# Glasses.net
KiCad netlist of a schematic drawn in EAGLE
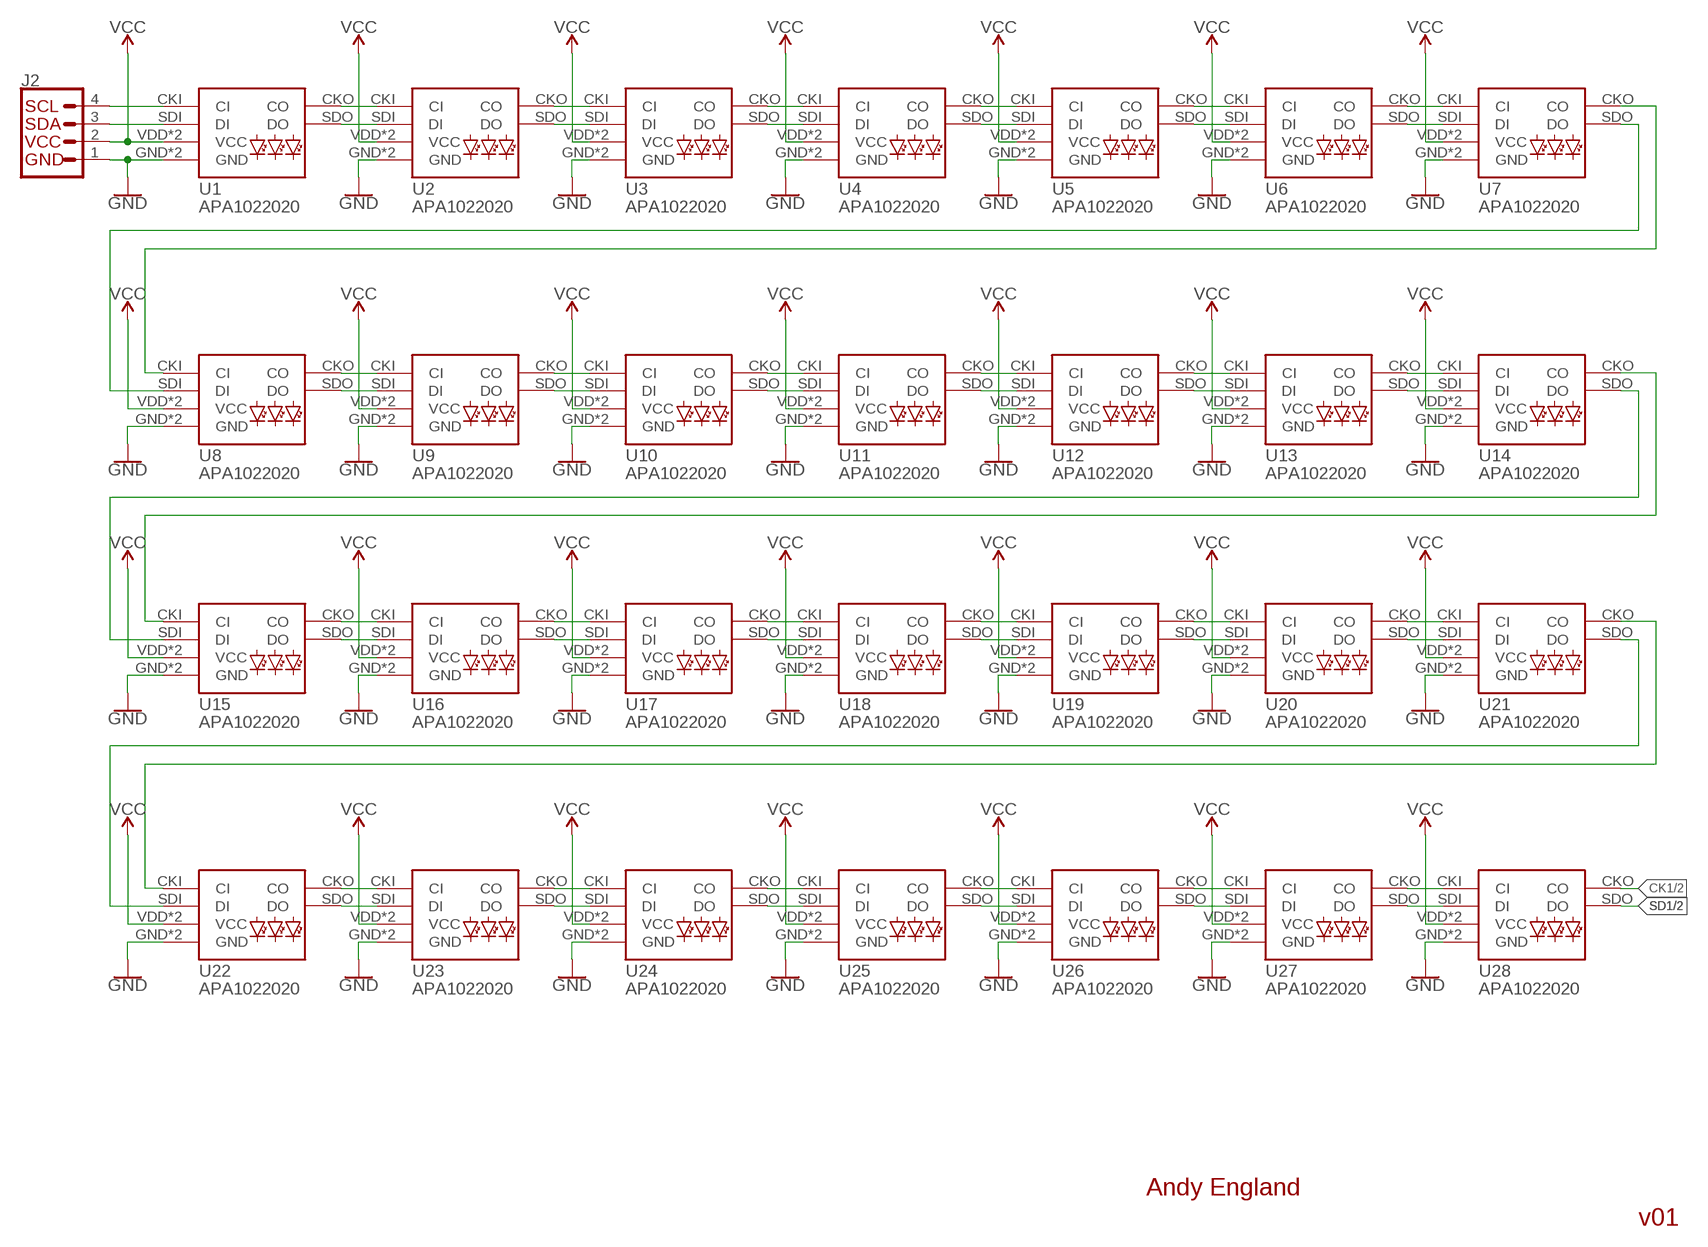
[diagram p0: schematic, sheet 1]
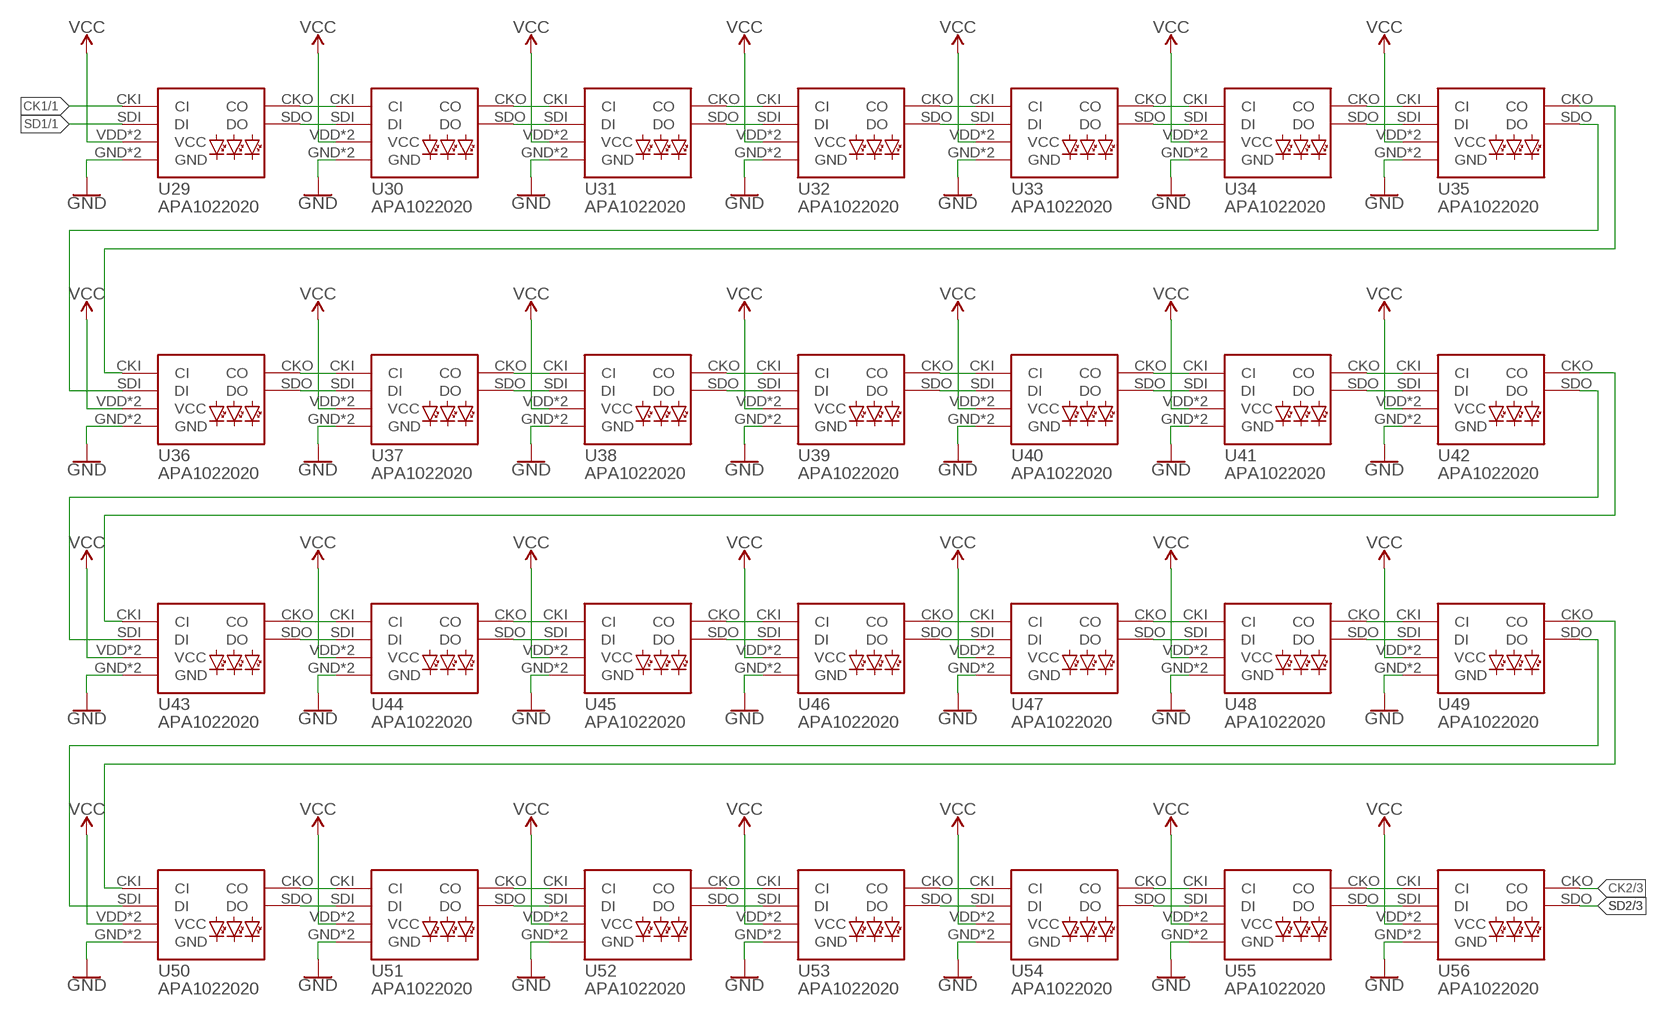
[diagram p1: schematic, sheet 2]
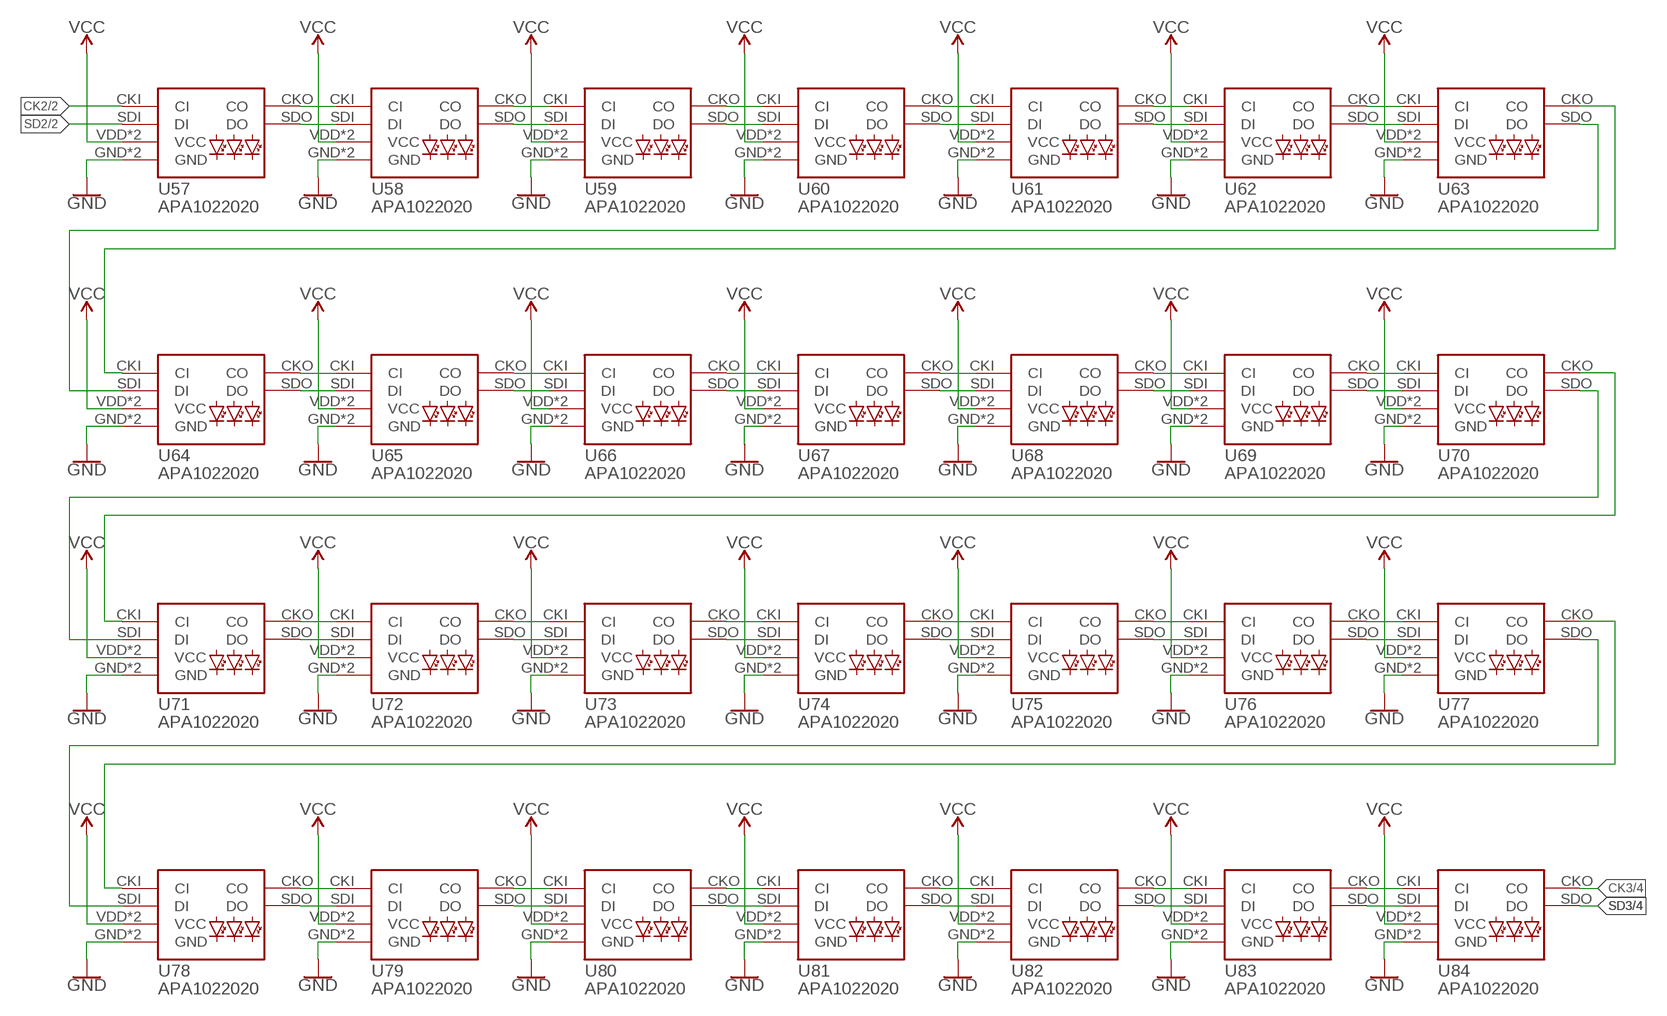
[diagram p2: schematic, sheet 3]
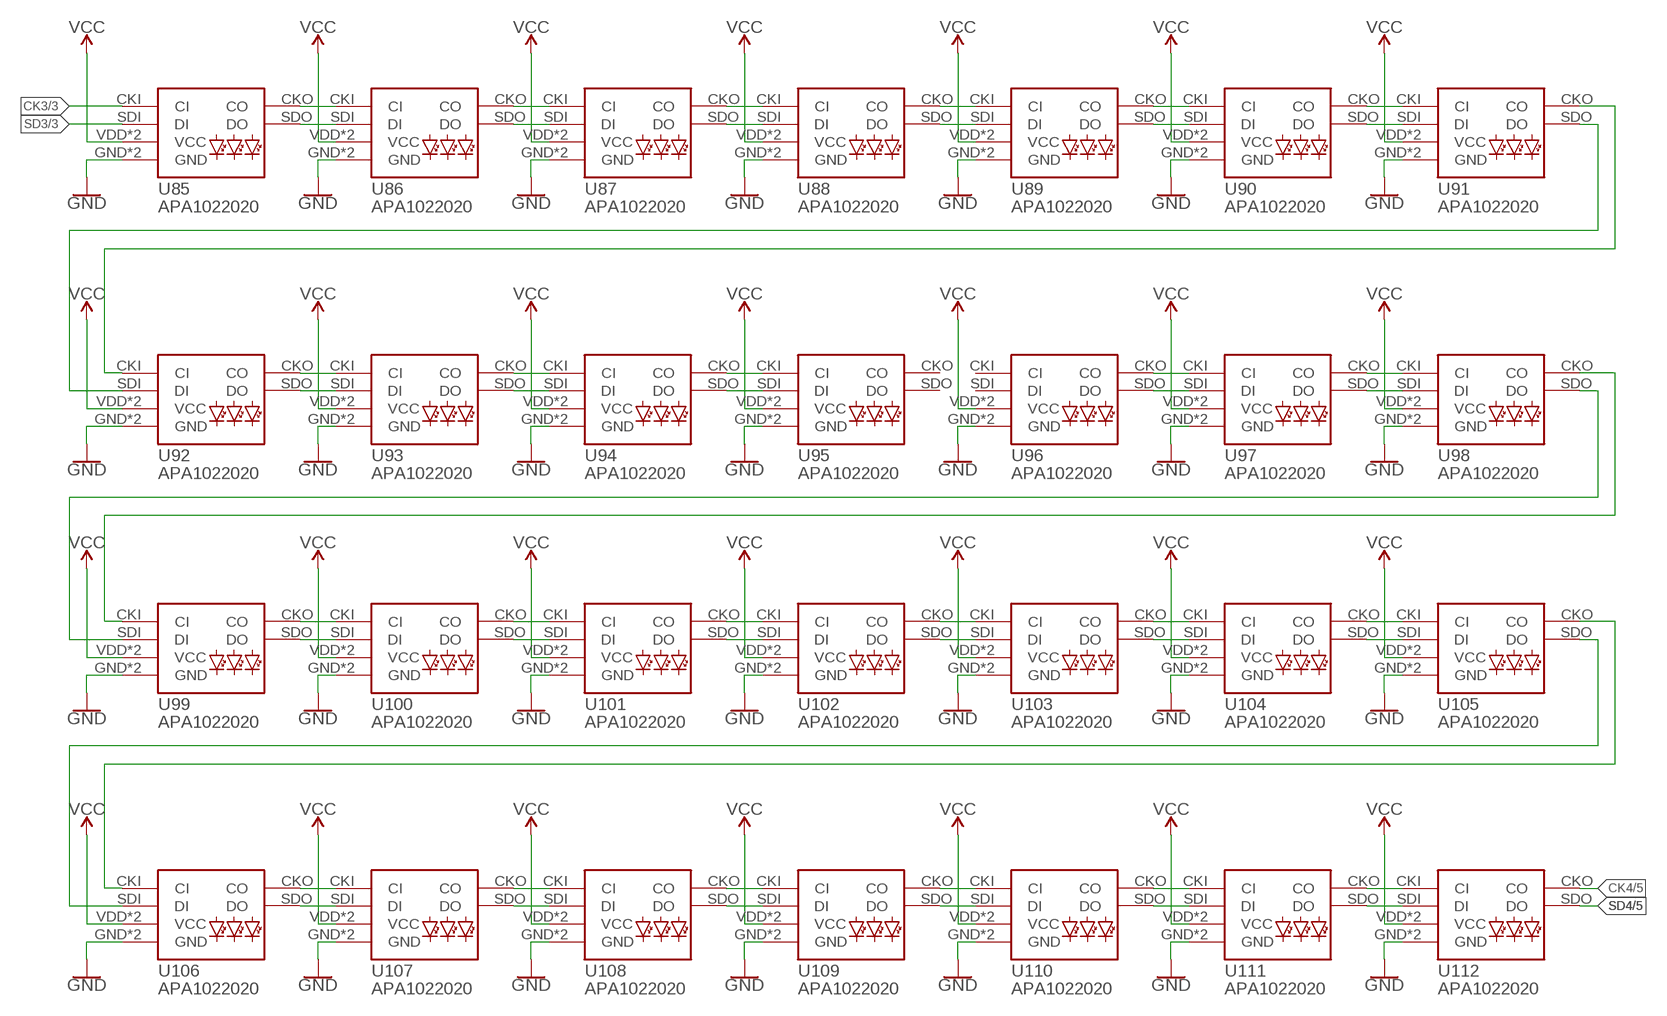
[diagram p3: schematic, sheet 4]
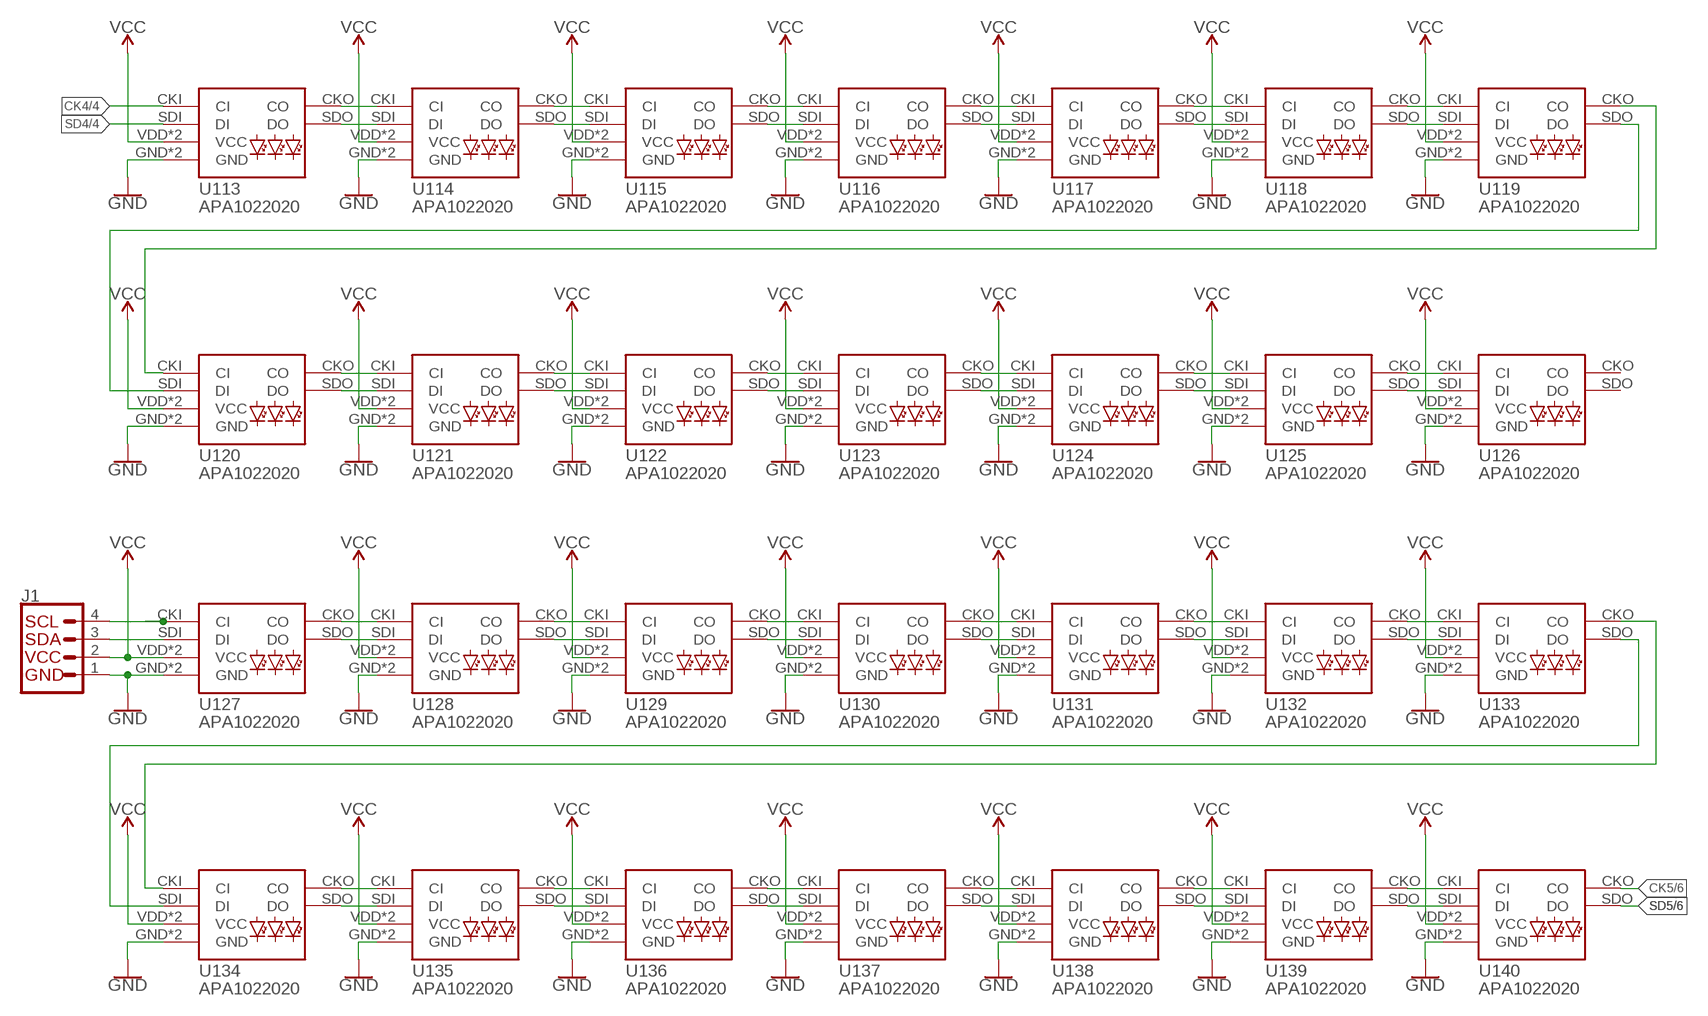
[diagram p4: schematic, sheet 5]
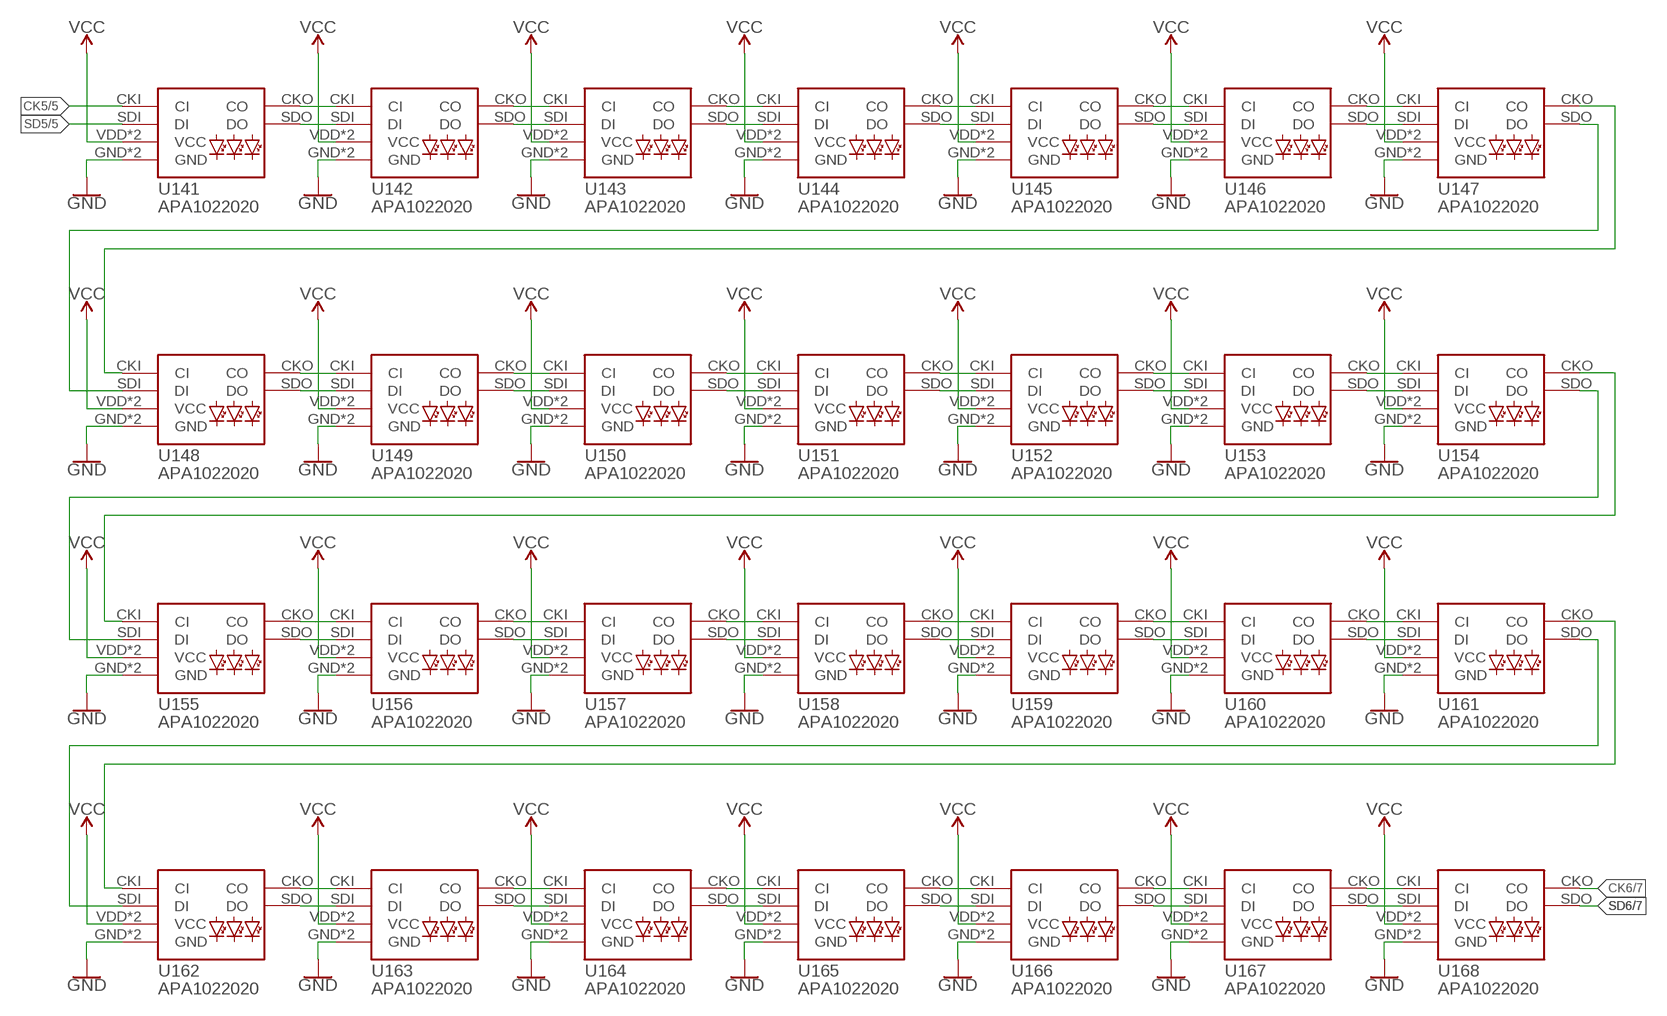
[diagram p5: schematic, sheet 6]
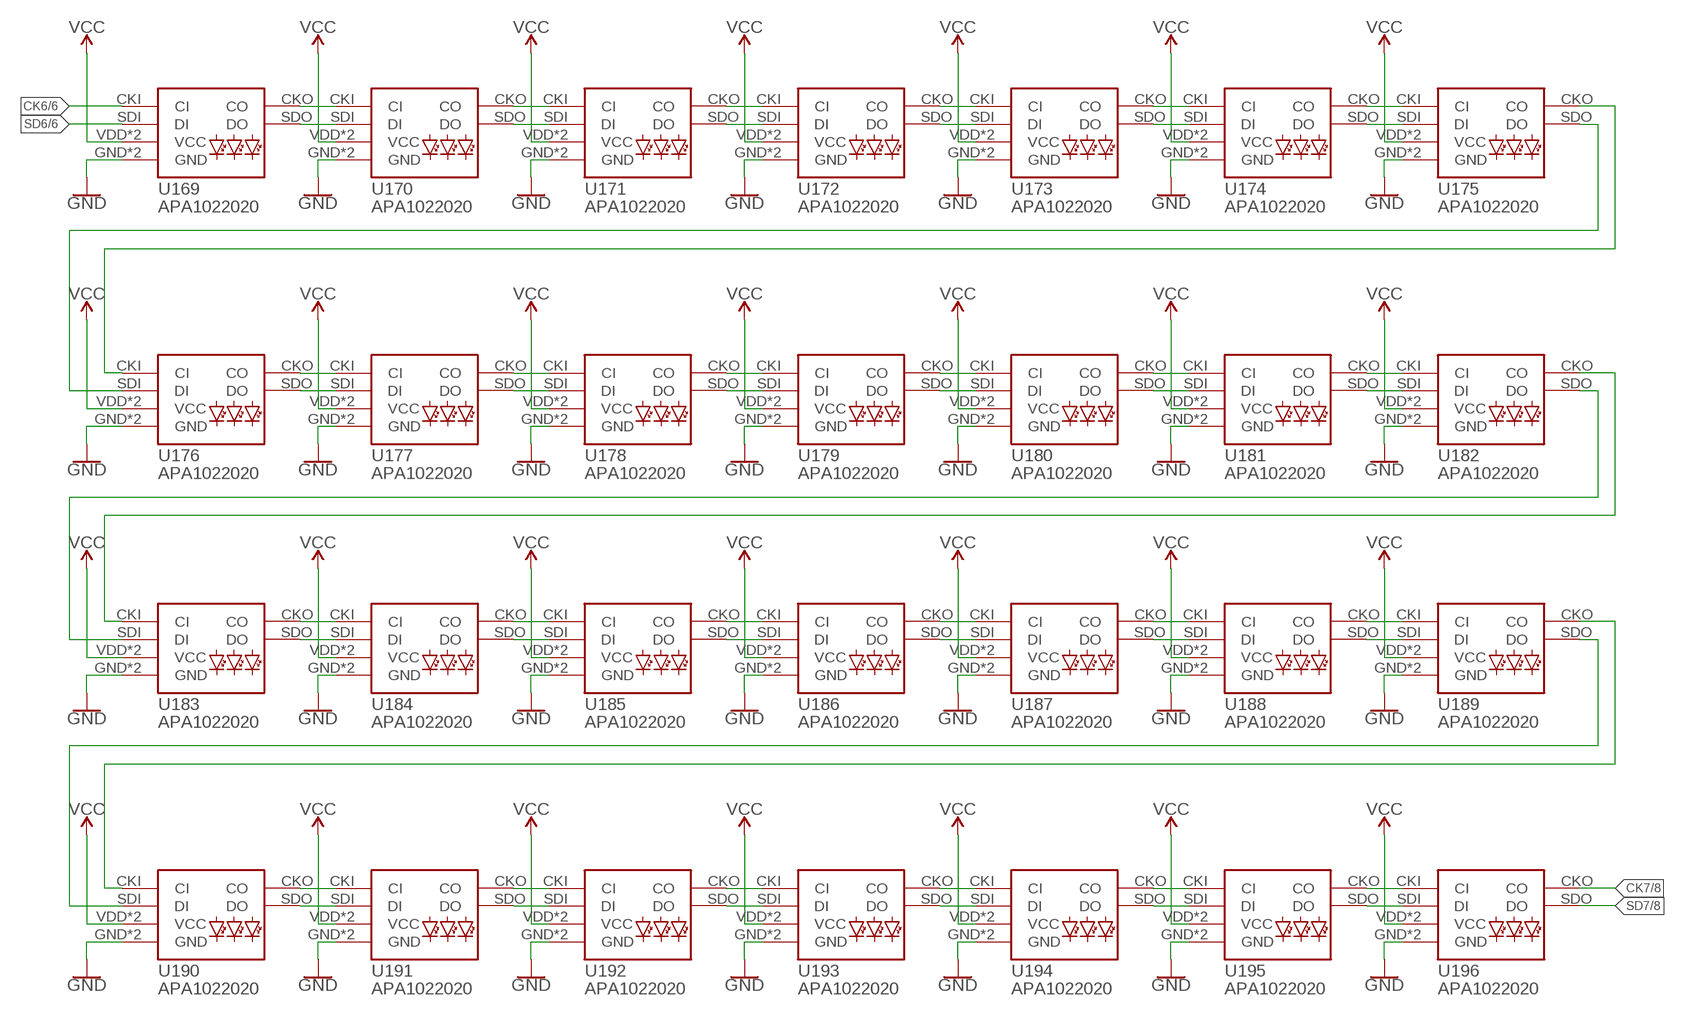
[diagram p6: schematic, sheet 7]
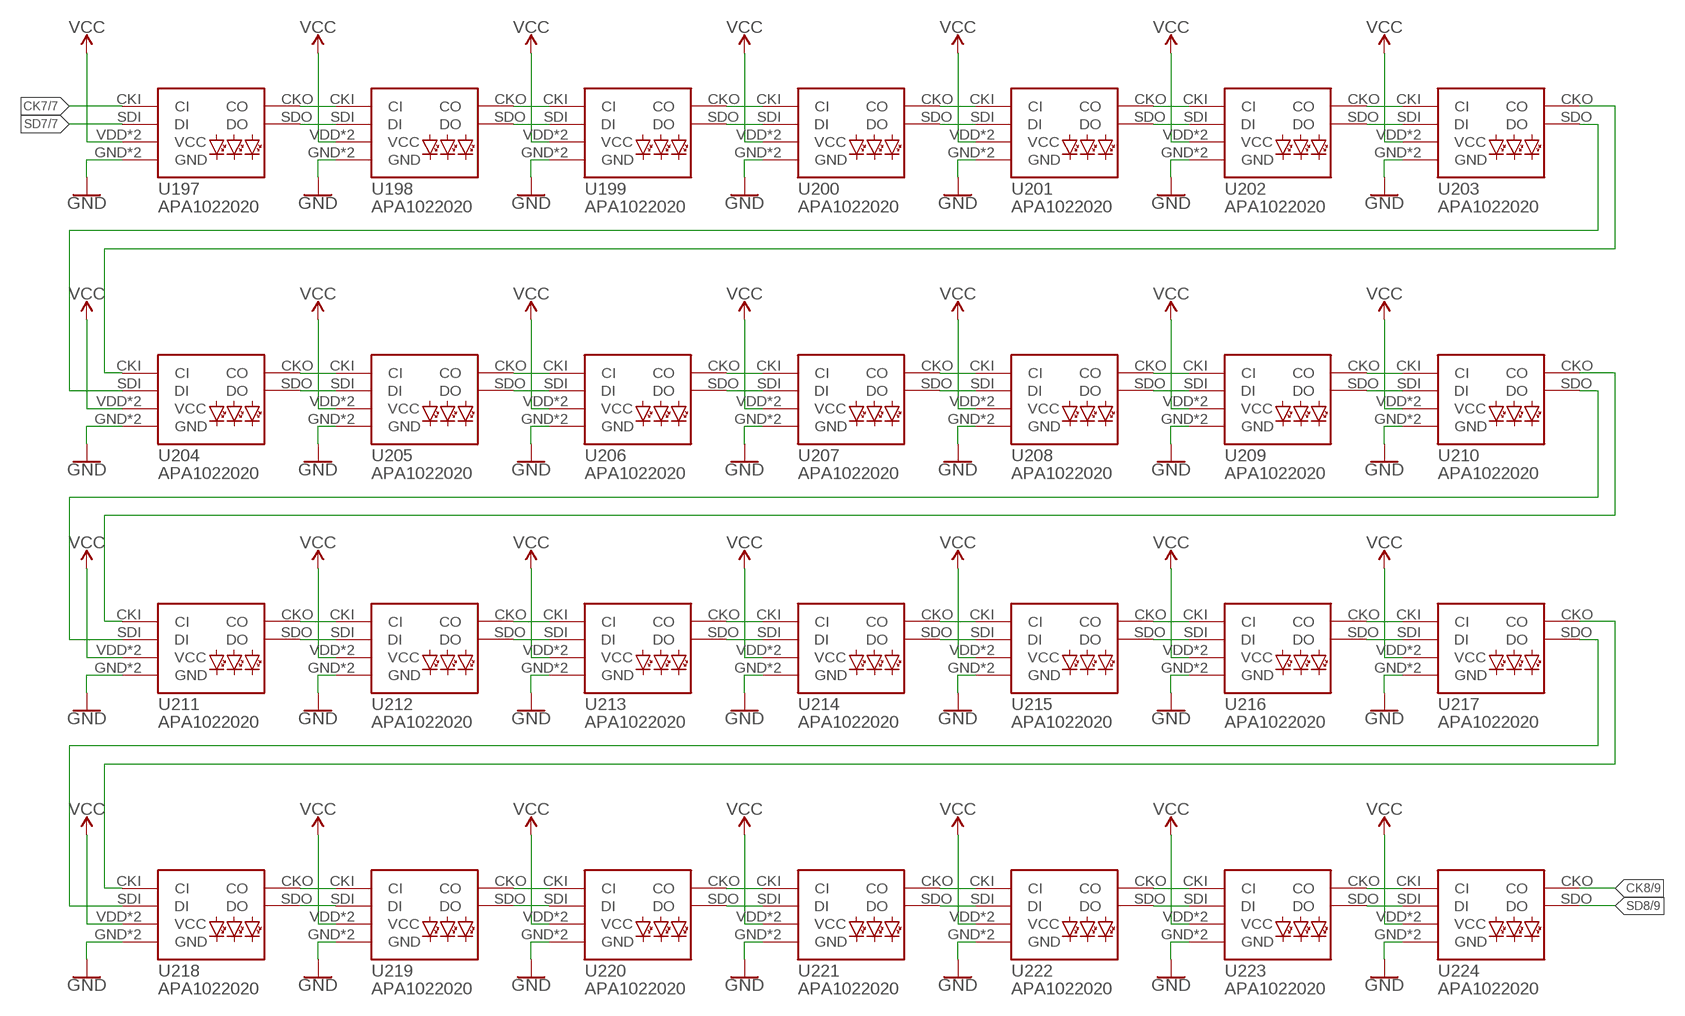
[diagram p7: schematic, sheet 8]
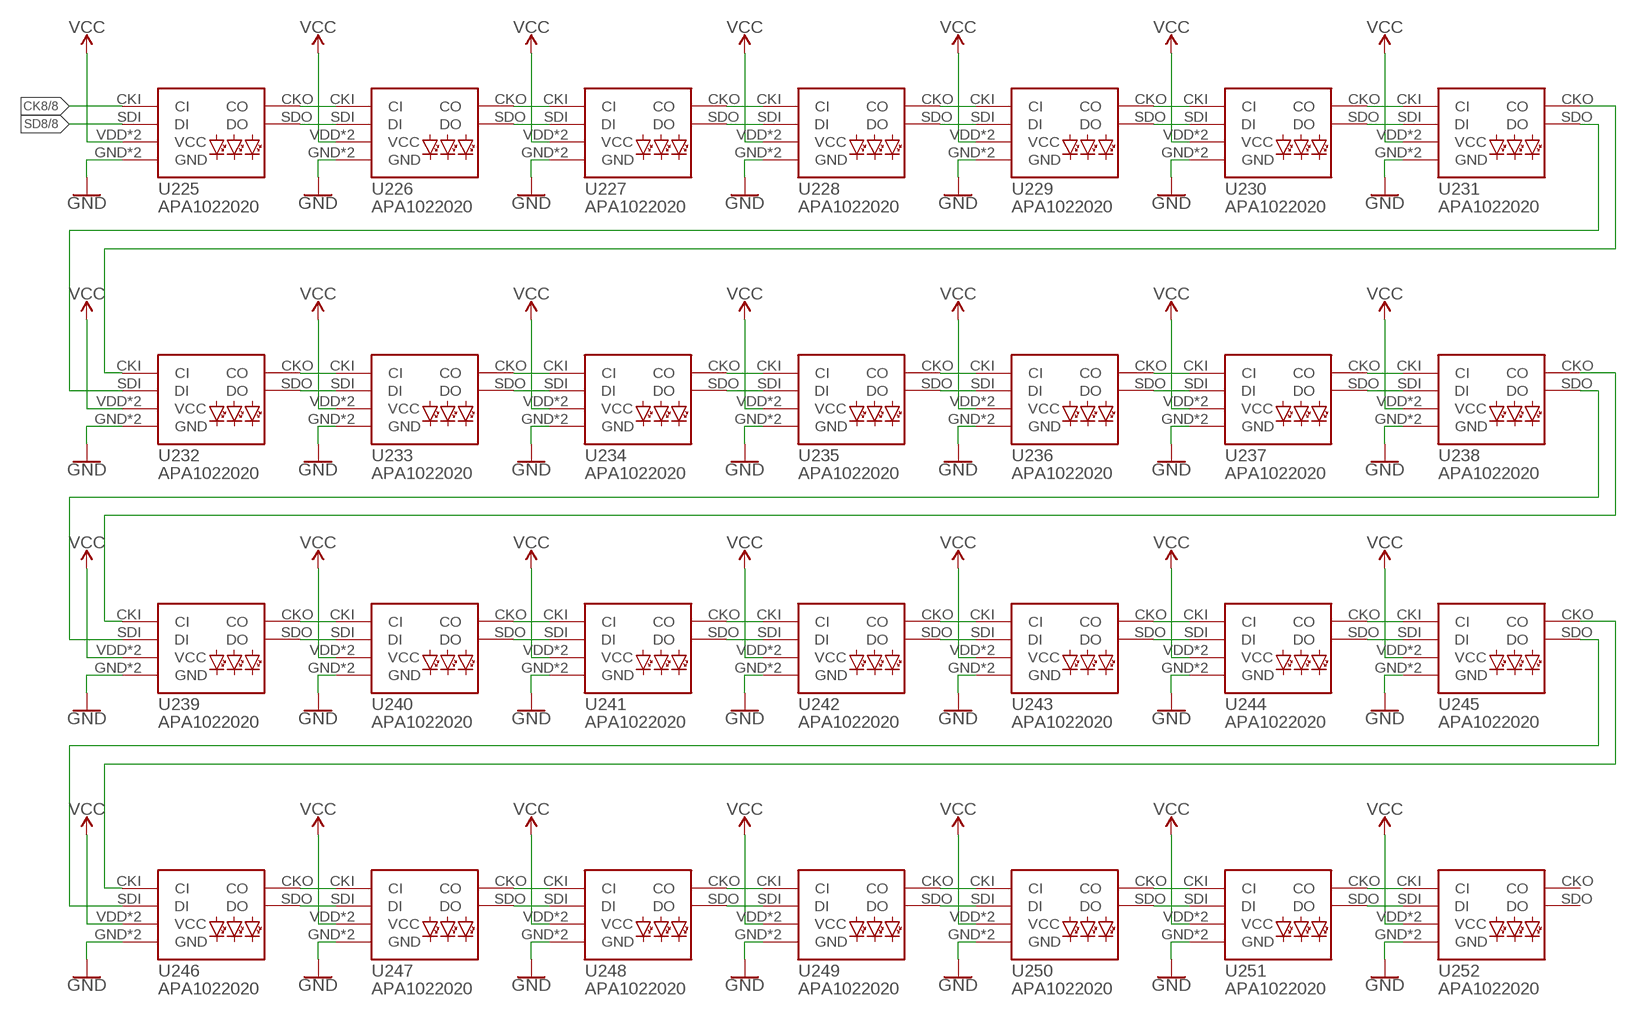
[diagram p8: schematic, sheet 9]

(export (version "E")
  (design (tool "Eeschema 10.0.6"))
  (components
    (comp (ref "U225")
      (value "APA1022020")
      (footprint "eagle-import:APA102-2020")
      (libsource (lib "eagle-import") (part "APA1022020"))
    )
    (comp (ref "U226")
      (value "APA1022020")
      (footprint "eagle-import:APA102-2020")
      (libsource (lib "eagle-import") (part "APA1022020"))
    )
    (comp (ref "U227")
      (value "APA1022020")
      (footprint "eagle-import:APA102-2020")
      (libsource (lib "eagle-import") (part "APA1022020"))
    )
    (comp (ref "U228")
      (value "APA1022020")
      (footprint "eagle-import:APA102-2020")
      (libsource (lib "eagle-import") (part "APA1022020"))
    )
    (comp (ref "U229")
      (value "APA1022020")
      (footprint "eagle-import:APA102-2020")
      (libsource (lib "eagle-import") (part "APA1022020"))
    )
    (comp (ref "U230")
      (value "APA1022020")
      (footprint "eagle-import:APA102-2020")
      (libsource (lib "eagle-import") (part "APA1022020"))
    )
    (comp (ref "U231")
      (value "APA1022020")
      (footprint "eagle-import:APA102-2020")
      (libsource (lib "eagle-import") (part "APA1022020"))
    )
    (comp (ref "U232")
      (value "APA1022020")
      (footprint "eagle-import:APA102-2020")
      (libsource (lib "eagle-import") (part "APA1022020"))
    )
    (comp (ref "U233")
      (value "APA1022020")
      (footprint "eagle-import:APA102-2020")
      (libsource (lib "eagle-import") (part "APA1022020"))
    )
    (comp (ref "U234")
      (value "APA1022020")
      (footprint "eagle-import:APA102-2020")
      (libsource (lib "eagle-import") (part "APA1022020"))
    )
    (comp (ref "U235")
      (value "APA1022020")
      (footprint "eagle-import:APA102-2020")
      (libsource (lib "eagle-import") (part "APA1022020"))
    )
    (comp (ref "U236")
      (value "APA1022020")
      (footprint "eagle-import:APA102-2020")
      (libsource (lib "eagle-import") (part "APA1022020"))
    )
    (comp (ref "U237")
      (value "APA1022020")
      (footprint "eagle-import:APA102-2020")
      (libsource (lib "eagle-import") (part "APA1022020"))
    )
    (comp (ref "U238")
      (value "APA1022020")
      (footprint "eagle-import:APA102-2020")
      (libsource (lib "eagle-import") (part "APA1022020"))
    )
    (comp (ref "U239")
      (value "APA1022020")
      (footprint "eagle-import:APA102-2020")
      (libsource (lib "eagle-import") (part "APA1022020"))
    )
    (comp (ref "U240")
      (value "APA1022020")
      (footprint "eagle-import:APA102-2020")
      (libsource (lib "eagle-import") (part "APA1022020"))
    )
    (comp (ref "U241")
      (value "APA1022020")
      (footprint "eagle-import:APA102-2020")
      (libsource (lib "eagle-import") (part "APA1022020"))
    )
    (comp (ref "U242")
      (value "APA1022020")
      (footprint "eagle-import:APA102-2020")
      (libsource (lib "eagle-import") (part "APA1022020"))
    )
    (comp (ref "U243")
      (value "APA1022020")
      (footprint "eagle-import:APA102-2020")
      (libsource (lib "eagle-import") (part "APA1022020"))
    )
    (comp (ref "U244")
      (value "APA1022020")
      (footprint "eagle-import:APA102-2020")
      (libsource (lib "eagle-import") (part "APA1022020"))
    )
    (comp (ref "U245")
      (value "APA1022020")
      (footprint "eagle-import:APA102-2020")
      (libsource (lib "eagle-import") (part "APA1022020"))
    )
    (comp (ref "U246")
      (value "APA1022020")
      (footprint "eagle-import:APA102-2020")
      (libsource (lib "eagle-import") (part "APA1022020"))
    )
    (comp (ref "U247")
      (value "APA1022020")
      (footprint "eagle-import:APA102-2020")
      (libsource (lib "eagle-import") (part "APA1022020"))
    )
    (comp (ref "U248")
      (value "APA1022020")
      (footprint "eagle-import:APA102-2020")
      (libsource (lib "eagle-import") (part "APA1022020"))
    )
    (comp (ref "U249")
      (value "APA1022020")
      (footprint "eagle-import:APA102-2020")
      (libsource (lib "eagle-import") (part "APA1022020"))
    )
    (comp (ref "U250")
      (value "APA1022020")
      (footprint "eagle-import:APA102-2020")
      (libsource (lib "eagle-import") (part "APA1022020"))
    )
    (comp (ref "U251")
      (value "APA1022020")
      (footprint "eagle-import:APA102-2020")
      (libsource (lib "eagle-import") (part "APA1022020"))
    )
    (comp (ref "U252")
      (value "APA1022020")
      (footprint "eagle-import:APA102-2020")
      (libsource (lib "eagle-import") (part "APA1022020"))
    )
    (comp (ref "U141")
      (value "APA1022020")
      (footprint "eagle-import:APA102-2020")
      (libsource (lib "eagle-import") (part "APA1022020"))
    )
    (comp (ref "U142")
      (value "APA1022020")
      (footprint "eagle-import:APA102-2020")
      (libsource (lib "eagle-import") (part "APA1022020"))
    )
    (comp (ref "U143")
      (value "APA1022020")
      (footprint "eagle-import:APA102-2020")
      (libsource (lib "eagle-import") (part "APA1022020"))
    )
    (comp (ref "U144")
      (value "APA1022020")
      (footprint "eagle-import:APA102-2020")
      (libsource (lib "eagle-import") (part "APA1022020"))
    )
    (comp (ref "U145")
      (value "APA1022020")
      (footprint "eagle-import:APA102-2020")
      (libsource (lib "eagle-import") (part "APA1022020"))
    )
    (comp (ref "U146")
      (value "APA1022020")
      (footprint "eagle-import:APA102-2020")
      (libsource (lib "eagle-import") (part "APA1022020"))
    )
    (comp (ref "U147")
      (value "APA1022020")
      (footprint "eagle-import:APA102-2020")
      (libsource (lib "eagle-import") (part "APA1022020"))
    )
    (comp (ref "U148")
      (value "APA1022020")
      (footprint "eagle-import:APA102-2020")
      (libsource (lib "eagle-import") (part "APA1022020"))
    )
    (comp (ref "U149")
      (value "APA1022020")
      (footprint "eagle-import:APA102-2020")
      (libsource (lib "eagle-import") (part "APA1022020"))
    )
    (comp (ref "U150")
      (value "APA1022020")
      (footprint "eagle-import:APA102-2020")
      (libsource (lib "eagle-import") (part "APA1022020"))
    )
    (comp (ref "U151")
      (value "APA1022020")
      (footprint "eagle-import:APA102-2020")
      (libsource (lib "eagle-import") (part "APA1022020"))
    )
    (comp (ref "U152")
      (value "APA1022020")
      (footprint "eagle-import:APA102-2020")
      (libsource (lib "eagle-import") (part "APA1022020"))
    )
    (comp (ref "U153")
      (value "APA1022020")
      (footprint "eagle-import:APA102-2020")
      (libsource (lib "eagle-import") (part "APA1022020"))
    )
    (comp (ref "U154")
      (value "APA1022020")
      (footprint "eagle-import:APA102-2020")
      (libsource (lib "eagle-import") (part "APA1022020"))
    )
    (comp (ref "U155")
      (value "APA1022020")
      (footprint "eagle-import:APA102-2020")
      (libsource (lib "eagle-import") (part "APA1022020"))
    )
    (comp (ref "U156")
      (value "APA1022020")
      (footprint "eagle-import:APA102-2020")
      (libsource (lib "eagle-import") (part "APA1022020"))
    )
    (comp (ref "U157")
      (value "APA1022020")
      (footprint "eagle-import:APA102-2020")
      (libsource (lib "eagle-import") (part "APA1022020"))
    )
    (comp (ref "U158")
      (value "APA1022020")
      (footprint "eagle-import:APA102-2020")
      (libsource (lib "eagle-import") (part "APA1022020"))
    )
    (comp (ref "U159")
      (value "APA1022020")
      (footprint "eagle-import:APA102-2020")
      (libsource (lib "eagle-import") (part "APA1022020"))
    )
    (comp (ref "U160")
      (value "APA1022020")
      (footprint "eagle-import:APA102-2020")
      (libsource (lib "eagle-import") (part "APA1022020"))
    )
    (comp (ref "U161")
      (value "APA1022020")
      (footprint "eagle-import:APA102-2020")
      (libsource (lib "eagle-import") (part "APA1022020"))
    )
    (comp (ref "U162")
      (value "APA1022020")
      (footprint "eagle-import:APA102-2020")
      (libsource (lib "eagle-import") (part "APA1022020"))
    )
    (comp (ref "U163")
      (value "APA1022020")
      (footprint "eagle-import:APA102-2020")
      (libsource (lib "eagle-import") (part "APA1022020"))
    )
    (comp (ref "U164")
      (value "APA1022020")
      (footprint "eagle-import:APA102-2020")
      (libsource (lib "eagle-import") (part "APA1022020"))
    )
    (comp (ref "U165")
      (value "APA1022020")
      (footprint "eagle-import:APA102-2020")
      (libsource (lib "eagle-import") (part "APA1022020"))
    )
    (comp (ref "U166")
      (value "APA1022020")
      (footprint "eagle-import:APA102-2020")
      (libsource (lib "eagle-import") (part "APA1022020"))
    )
    (comp (ref "U167")
      (value "APA1022020")
      (footprint "eagle-import:APA102-2020")
      (libsource (lib "eagle-import") (part "APA1022020"))
    )
    (comp (ref "U168")
      (value "APA1022020")
      (footprint "eagle-import:APA102-2020")
      (libsource (lib "eagle-import") (part "APA1022020"))
    )
    (comp (ref "U169")
      (value "APA1022020")
      (footprint "eagle-import:APA102-2020")
      (libsource (lib "eagle-import") (part "APA1022020"))
    )
    (comp (ref "U170")
      (value "APA1022020")
      (footprint "eagle-import:APA102-2020")
      (libsource (lib "eagle-import") (part "APA1022020"))
    )
    (comp (ref "U171")
      (value "APA1022020")
      (footprint "eagle-import:APA102-2020")
      (libsource (lib "eagle-import") (part "APA1022020"))
    )
    (comp (ref "U172")
      (value "APA1022020")
      (footprint "eagle-import:APA102-2020")
      (libsource (lib "eagle-import") (part "APA1022020"))
    )
    (comp (ref "U173")
      (value "APA1022020")
      (footprint "eagle-import:APA102-2020")
      (libsource (lib "eagle-import") (part "APA1022020"))
    )
    (comp (ref "U174")
      (value "APA1022020")
      (footprint "eagle-import:APA102-2020")
      (libsource (lib "eagle-import") (part "APA1022020"))
    )
    (comp (ref "U175")
      (value "APA1022020")
      (footprint "eagle-import:APA102-2020")
      (libsource (lib "eagle-import") (part "APA1022020"))
    )
    (comp (ref "U176")
      (value "APA1022020")
      (footprint "eagle-import:APA102-2020")
      (libsource (lib "eagle-import") (part "APA1022020"))
    )
    (comp (ref "U177")
      (value "APA1022020")
      (footprint "eagle-import:APA102-2020")
      (libsource (lib "eagle-import") (part "APA1022020"))
    )
    (comp (ref "U178")
      (value "APA1022020")
      (footprint "eagle-import:APA102-2020")
      (libsource (lib "eagle-import") (part "APA1022020"))
    )
    (comp (ref "U179")
      (value "APA1022020")
      (footprint "eagle-import:APA102-2020")
      (libsource (lib "eagle-import") (part "APA1022020"))
    )
    (comp (ref "U180")
      (value "APA1022020")
      (footprint "eagle-import:APA102-2020")
      (libsource (lib "eagle-import") (part "APA1022020"))
    )
    (comp (ref "U181")
      (value "APA1022020")
      (footprint "eagle-import:APA102-2020")
      (libsource (lib "eagle-import") (part "APA1022020"))
    )
    (comp (ref "U182")
      (value "APA1022020")
      (footprint "eagle-import:APA102-2020")
      (libsource (lib "eagle-import") (part "APA1022020"))
    )
    (comp (ref "U183")
      (value "APA1022020")
      (footprint "eagle-import:APA102-2020")
      (libsource (lib "eagle-import") (part "APA1022020"))
    )
    (comp (ref "U184")
      (value "APA1022020")
      (footprint "eagle-import:APA102-2020")
      (libsource (lib "eagle-import") (part "APA1022020"))
    )
    (comp (ref "U185")
      (value "APA1022020")
      (footprint "eagle-import:APA102-2020")
      (libsource (lib "eagle-import") (part "APA1022020"))
    )
    (comp (ref "U186")
      (value "APA1022020")
      (footprint "eagle-import:APA102-2020")
      (libsource (lib "eagle-import") (part "APA1022020"))
    )
    (comp (ref "U187")
      (value "APA1022020")
      (footprint "eagle-import:APA102-2020")
      (libsource (lib "eagle-import") (part "APA1022020"))
    )
    (comp (ref "U188")
      (value "APA1022020")
      (footprint "eagle-import:APA102-2020")
      (libsource (lib "eagle-import") (part "APA1022020"))
    )
    (comp (ref "U189")
      (value "APA1022020")
      (footprint "eagle-import:APA102-2020")
      (libsource (lib "eagle-import") (part "APA1022020"))
    )
    (comp (ref "U190")
      (value "APA1022020")
      (footprint "eagle-import:APA102-2020")
      (libsource (lib "eagle-import") (part "APA1022020"))
    )
    (comp (ref "U191")
      (value "APA1022020")
      (footprint "eagle-import:APA102-2020")
      (libsource (lib "eagle-import") (part "APA1022020"))
    )
    (comp (ref "U192")
      (value "APA1022020")
      (footprint "eagle-import:APA102-2020")
      (libsource (lib "eagle-import") (part "APA1022020"))
    )
    (comp (ref "U193")
      (value "APA1022020")
      (footprint "eagle-import:APA102-2020")
      (libsource (lib "eagle-import") (part "APA1022020"))
    )
    (comp (ref "U194")
      (value "APA1022020")
      (footprint "eagle-import:APA102-2020")
      (libsource (lib "eagle-import") (part "APA1022020"))
    )
    (comp (ref "U195")
      (value "APA1022020")
      (footprint "eagle-import:APA102-2020")
      (libsource (lib "eagle-import") (part "APA1022020"))
    )
    (comp (ref "U196")
      (value "APA1022020")
      (footprint "eagle-import:APA102-2020")
      (libsource (lib "eagle-import") (part "APA1022020"))
    )
    (comp (ref "U197")
      (value "APA1022020")
      (footprint "eagle-import:APA102-2020")
      (libsource (lib "eagle-import") (part "APA1022020"))
    )
    (comp (ref "U198")
      (value "APA1022020")
      (footprint "eagle-import:APA102-2020")
      (libsource (lib "eagle-import") (part "APA1022020"))
    )
    (comp (ref "U199")
      (value "APA1022020")
      (footprint "eagle-import:APA102-2020")
      (libsource (lib "eagle-import") (part "APA1022020"))
    )
    (comp (ref "U200")
      (value "APA1022020")
      (footprint "eagle-import:APA102-2020")
      (libsource (lib "eagle-import") (part "APA1022020"))
    )
    (comp (ref "U201")
      (value "APA1022020")
      (footprint "eagle-import:APA102-2020")
      (libsource (lib "eagle-import") (part "APA1022020"))
    )
    (comp (ref "U202")
      (value "APA1022020")
      (footprint "eagle-import:APA102-2020")
      (libsource (lib "eagle-import") (part "APA1022020"))
    )
    (comp (ref "U203")
      (value "APA1022020")
      (footprint "eagle-import:APA102-2020")
      (libsource (lib "eagle-import") (part "APA1022020"))
    )
    (comp (ref "U204")
      (value "APA1022020")
      (footprint "eagle-import:APA102-2020")
      (libsource (lib "eagle-import") (part "APA1022020"))
    )
    (comp (ref "U205")
      (value "APA1022020")
      (footprint "eagle-import:APA102-2020")
      (libsource (lib "eagle-import") (part "APA1022020"))
    )
    (comp (ref "U206")
      (value "APA1022020")
      (footprint "eagle-import:APA102-2020")
      (libsource (lib "eagle-import") (part "APA1022020"))
    )
    (comp (ref "U207")
      (value "APA1022020")
      (footprint "eagle-import:APA102-2020")
      (libsource (lib "eagle-import") (part "APA1022020"))
    )
    (comp (ref "U208")
      (value "APA1022020")
      (footprint "eagle-import:APA102-2020")
      (libsource (lib "eagle-import") (part "APA1022020"))
    )
    (comp (ref "U209")
      (value "APA1022020")
      (footprint "eagle-import:APA102-2020")
      (libsource (lib "eagle-import") (part "APA1022020"))
    )
    (comp (ref "U210")
      (value "APA1022020")
      (footprint "eagle-import:APA102-2020")
      (libsource (lib "eagle-import") (part "APA1022020"))
    )
    (comp (ref "U211")
      (value "APA1022020")
      (footprint "eagle-import:APA102-2020")
      (libsource (lib "eagle-import") (part "APA1022020"))
    )
    (comp (ref "U212")
      (value "APA1022020")
      (footprint "eagle-import:APA102-2020")
      (libsource (lib "eagle-import") (part "APA1022020"))
    )
    (comp (ref "U213")
      (value "APA1022020")
      (footprint "eagle-import:APA102-2020")
      (libsource (lib "eagle-import") (part "APA1022020"))
    )
    (comp (ref "U214")
      (value "APA1022020")
      (footprint "eagle-import:APA102-2020")
      (libsource (lib "eagle-import") (part "APA1022020"))
    )
    (comp (ref "U215")
      (value "APA1022020")
      (footprint "eagle-import:APA102-2020")
      (libsource (lib "eagle-import") (part "APA1022020"))
    )
    (comp (ref "U216")
      (value "APA1022020")
      (footprint "eagle-import:APA102-2020")
      (libsource (lib "eagle-import") (part "APA1022020"))
    )
    (comp (ref "U217")
      (value "APA1022020")
      (footprint "eagle-import:APA102-2020")
      (libsource (lib "eagle-import") (part "APA1022020"))
    )
    (comp (ref "U218")
      (value "APA1022020")
      (footprint "eagle-import:APA102-2020")
      (libsource (lib "eagle-import") (part "APA1022020"))
    )
    (comp (ref "U219")
      (value "APA1022020")
      (footprint "eagle-import:APA102-2020")
      (libsource (lib "eagle-import") (part "APA1022020"))
    )
    (comp (ref "U220")
      (value "APA1022020")
      (footprint "eagle-import:APA102-2020")
      (libsource (lib "eagle-import") (part "APA1022020"))
    )
    (comp (ref "U221")
      (value "APA1022020")
      (footprint "eagle-import:APA102-2020")
      (libsource (lib "eagle-import") (part "APA1022020"))
    )
    (comp (ref "U222")
      (value "APA1022020")
      (footprint "eagle-import:APA102-2020")
      (libsource (lib "eagle-import") (part "APA1022020"))
    )
    (comp (ref "U223")
      (value "APA1022020")
      (footprint "eagle-import:APA102-2020")
      (libsource (lib "eagle-import") (part "APA1022020"))
    )
    (comp (ref "U224")
      (value "APA1022020")
      (footprint "eagle-import:APA102-2020")
      (libsource (lib "eagle-import") (part "APA1022020"))
    )
    (comp (ref "J2")
      (value "QWIIC_CONNECTORJS-1MM")
      (footprint "eagle-import:1X04_1MM_RA")
      (libsource (lib "eagle-import") (part "QWIIC_CONNECTORJS-1MM"))
    )
    (comp (ref "U1")
      (value "APA1022020")
      (footprint "eagle-import:APA102-2020")
      (libsource (lib "eagle-import") (part "APA1022020"))
    )
    (comp (ref "U2")
      (value "APA1022020")
      (footprint "eagle-import:APA102-2020")
      (libsource (lib "eagle-import") (part "APA1022020"))
    )
    (comp (ref "U3")
      (value "APA1022020")
      (footprint "eagle-import:APA102-2020")
      (libsource (lib "eagle-import") (part "APA1022020"))
    )
    (comp (ref "U4")
      (value "APA1022020")
      (footprint "eagle-import:APA102-2020")
      (libsource (lib "eagle-import") (part "APA1022020"))
    )
    (comp (ref "U5")
      (value "APA1022020")
      (footprint "eagle-import:APA102-2020")
      (libsource (lib "eagle-import") (part "APA1022020"))
    )
    (comp (ref "U6")
      (value "APA1022020")
      (footprint "eagle-import:APA102-2020")
      (libsource (lib "eagle-import") (part "APA1022020"))
    )
    (comp (ref "U7")
      (value "APA1022020")
      (footprint "eagle-import:APA102-2020")
      (libsource (lib "eagle-import") (part "APA1022020"))
    )
    (comp (ref "U8")
      (value "APA1022020")
      (footprint "eagle-import:APA102-2020")
      (libsource (lib "eagle-import") (part "APA1022020"))
    )
    (comp (ref "U9")
      (value "APA1022020")
      (footprint "eagle-import:APA102-2020")
      (libsource (lib "eagle-import") (part "APA1022020"))
    )
    (comp (ref "U10")
      (value "APA1022020")
      (footprint "eagle-import:APA102-2020")
      (libsource (lib "eagle-import") (part "APA1022020"))
    )
    (comp (ref "U11")
      (value "APA1022020")
      (footprint "eagle-import:APA102-2020")
      (libsource (lib "eagle-import") (part "APA1022020"))
    )
    (comp (ref "U12")
      (value "APA1022020")
      (footprint "eagle-import:APA102-2020")
      (libsource (lib "eagle-import") (part "APA1022020"))
    )
    (comp (ref "U13")
      (value "APA1022020")
      (footprint "eagle-import:APA102-2020")
      (libsource (lib "eagle-import") (part "APA1022020"))
    )
    (comp (ref "U14")
      (value "APA1022020")
      (footprint "eagle-import:APA102-2020")
      (libsource (lib "eagle-import") (part "APA1022020"))
    )
    (comp (ref "U15")
      (value "APA1022020")
      (footprint "eagle-import:APA102-2020")
      (libsource (lib "eagle-import") (part "APA1022020"))
    )
    (comp (ref "U16")
      (value "APA1022020")
      (footprint "eagle-import:APA102-2020")
      (libsource (lib "eagle-import") (part "APA1022020"))
    )
    (comp (ref "U17")
      (value "APA1022020")
      (footprint "eagle-import:APA102-2020")
      (libsource (lib "eagle-import") (part "APA1022020"))
    )
    (comp (ref "U18")
      (value "APA1022020")
      (footprint "eagle-import:APA102-2020")
      (libsource (lib "eagle-import") (part "APA1022020"))
    )
    (comp (ref "U19")
      (value "APA1022020")
      (footprint "eagle-import:APA102-2020")
      (libsource (lib "eagle-import") (part "APA1022020"))
    )
    (comp (ref "U20")
      (value "APA1022020")
      (footprint "eagle-import:APA102-2020")
      (libsource (lib "eagle-import") (part "APA1022020"))
    )
    (comp (ref "U21")
      (value "APA1022020")
      (footprint "eagle-import:APA102-2020")
      (libsource (lib "eagle-import") (part "APA1022020"))
    )
    (comp (ref "U22")
      (value "APA1022020")
      (footprint "eagle-import:APA102-2020")
      (libsource (lib "eagle-import") (part "APA1022020"))
    )
    (comp (ref "U23")
      (value "APA1022020")
      (footprint "eagle-import:APA102-2020")
      (libsource (lib "eagle-import") (part "APA1022020"))
    )
    (comp (ref "U24")
      (value "APA1022020")
      (footprint "eagle-import:APA102-2020")
      (libsource (lib "eagle-import") (part "APA1022020"))
    )
    (comp (ref "U25")
      (value "APA1022020")
      (footprint "eagle-import:APA102-2020")
      (libsource (lib "eagle-import") (part "APA1022020"))
    )
    (comp (ref "U26")
      (value "APA1022020")
      (footprint "eagle-import:APA102-2020")
      (libsource (lib "eagle-import") (part "APA1022020"))
    )
    (comp (ref "U27")
      (value "APA1022020")
      (footprint "eagle-import:APA102-2020")
      (libsource (lib "eagle-import") (part "APA1022020"))
    )
    (comp (ref "U28")
      (value "APA1022020")
      (footprint "eagle-import:APA102-2020")
      (libsource (lib "eagle-import") (part "APA1022020"))
    )
    (comp (ref "J1")
      (value "QWIIC_CONNECTORJS-1MM")
      (footprint "eagle-import:1X04_1MM_RA")
      (libsource (lib "eagle-import") (part "QWIIC_CONNECTORJS-1MM"))
    )
    (comp (ref "U113")
      (value "APA1022020")
      (footprint "eagle-import:APA102-2020")
      (libsource (lib "eagle-import") (part "APA1022020"))
    )
    (comp (ref "U114")
      (value "APA1022020")
      (footprint "eagle-import:APA102-2020")
      (libsource (lib "eagle-import") (part "APA1022020"))
    )
    (comp (ref "U115")
      (value "APA1022020")
      (footprint "eagle-import:APA102-2020")
      (libsource (lib "eagle-import") (part "APA1022020"))
    )
    (comp (ref "U116")
      (value "APA1022020")
      (footprint "eagle-import:APA102-2020")
      (libsource (lib "eagle-import") (part "APA1022020"))
    )
    (comp (ref "U117")
      (value "APA1022020")
      (footprint "eagle-import:APA102-2020")
      (libsource (lib "eagle-import") (part "APA1022020"))
    )
    (comp (ref "U118")
      (value "APA1022020")
      (footprint "eagle-import:APA102-2020")
      (libsource (lib "eagle-import") (part "APA1022020"))
    )
    (comp (ref "U119")
      (value "APA1022020")
      (footprint "eagle-import:APA102-2020")
      (libsource (lib "eagle-import") (part "APA1022020"))
    )
    (comp (ref "U120")
      (value "APA1022020")
      (footprint "eagle-import:APA102-2020")
      (libsource (lib "eagle-import") (part "APA1022020"))
    )
    (comp (ref "U121")
      (value "APA1022020")
      (footprint "eagle-import:APA102-2020")
      (libsource (lib "eagle-import") (part "APA1022020"))
    )
    (comp (ref "U122")
      (value "APA1022020")
      (footprint "eagle-import:APA102-2020")
      (libsource (lib "eagle-import") (part "APA1022020"))
    )
    (comp (ref "U123")
      (value "APA1022020")
      (footprint "eagle-import:APA102-2020")
      (libsource (lib "eagle-import") (part "APA1022020"))
    )
    (comp (ref "U124")
      (value "APA1022020")
      (footprint "eagle-import:APA102-2020")
      (libsource (lib "eagle-import") (part "APA1022020"))
    )
    (comp (ref "U125")
      (value "APA1022020")
      (footprint "eagle-import:APA102-2020")
      (libsource (lib "eagle-import") (part "APA1022020"))
    )
    (comp (ref "U126")
      (value "APA1022020")
      (footprint "eagle-import:APA102-2020")
      (libsource (lib "eagle-import") (part "APA1022020"))
    )
    (comp (ref "U127")
      (value "APA1022020")
      (footprint "eagle-import:APA102-2020")
      (libsource (lib "eagle-import") (part "APA1022020"))
    )
    (comp (ref "U128")
      (value "APA1022020")
      (footprint "eagle-import:APA102-2020")
      (libsource (lib "eagle-import") (part "APA1022020"))
    )
    (comp (ref "U129")
      (value "APA1022020")
      (footprint "eagle-import:APA102-2020")
      (libsource (lib "eagle-import") (part "APA1022020"))
    )
    (comp (ref "U130")
      (value "APA1022020")
      (footprint "eagle-import:APA102-2020")
      (libsource (lib "eagle-import") (part "APA1022020"))
    )
    (comp (ref "U131")
      (value "APA1022020")
      (footprint "eagle-import:APA102-2020")
      (libsource (lib "eagle-import") (part "APA1022020"))
    )
    (comp (ref "U132")
      (value "APA1022020")
      (footprint "eagle-import:APA102-2020")
      (libsource (lib "eagle-import") (part "APA1022020"))
    )
    (comp (ref "U133")
      (value "APA1022020")
      (footprint "eagle-import:APA102-2020")
      (libsource (lib "eagle-import") (part "APA1022020"))
    )
    (comp (ref "U134")
      (value "APA1022020")
      (footprint "eagle-import:APA102-2020")
      (libsource (lib "eagle-import") (part "APA1022020"))
    )
    (comp (ref "U135")
      (value "APA1022020")
      (footprint "eagle-import:APA102-2020")
      (libsource (lib "eagle-import") (part "APA1022020"))
    )
    (comp (ref "U136")
      (value "APA1022020")
      (footprint "eagle-import:APA102-2020")
      (libsource (lib "eagle-import") (part "APA1022020"))
    )
    (comp (ref "U137")
      (value "APA1022020")
      (footprint "eagle-import:APA102-2020")
      (libsource (lib "eagle-import") (part "APA1022020"))
    )
    (comp (ref "U138")
      (value "APA1022020")
      (footprint "eagle-import:APA102-2020")
      (libsource (lib "eagle-import") (part "APA1022020"))
    )
    (comp (ref "U139")
      (value "APA1022020")
      (footprint "eagle-import:APA102-2020")
      (libsource (lib "eagle-import") (part "APA1022020"))
    )
    (comp (ref "U140")
      (value "APA1022020")
      (footprint "eagle-import:APA102-2020")
      (libsource (lib "eagle-import") (part "APA1022020"))
    )
    (comp (ref "U29")
      (value "APA1022020")
      (footprint "eagle-import:APA102-2020")
      (libsource (lib "eagle-import") (part "APA1022020"))
    )
    (comp (ref "U30")
      (value "APA1022020")
      (footprint "eagle-import:APA102-2020")
      (libsource (lib "eagle-import") (part "APA1022020"))
    )
    (comp (ref "U31")
      (value "APA1022020")
      (footprint "eagle-import:APA102-2020")
      (libsource (lib "eagle-import") (part "APA1022020"))
    )
    (comp (ref "U32")
      (value "APA1022020")
      (footprint "eagle-import:APA102-2020")
      (libsource (lib "eagle-import") (part "APA1022020"))
    )
    (comp (ref "U33")
      (value "APA1022020")
      (footprint "eagle-import:APA102-2020")
      (libsource (lib "eagle-import") (part "APA1022020"))
    )
    (comp (ref "U34")
      (value "APA1022020")
      (footprint "eagle-import:APA102-2020")
      (libsource (lib "eagle-import") (part "APA1022020"))
    )
    (comp (ref "U35")
      (value "APA1022020")
      (footprint "eagle-import:APA102-2020")
      (libsource (lib "eagle-import") (part "APA1022020"))
    )
    (comp (ref "U36")
      (value "APA1022020")
      (footprint "eagle-import:APA102-2020")
      (libsource (lib "eagle-import") (part "APA1022020"))
    )
    (comp (ref "U37")
      (value "APA1022020")
      (footprint "eagle-import:APA102-2020")
      (libsource (lib "eagle-import") (part "APA1022020"))
    )
    (comp (ref "U38")
      (value "APA1022020")
      (footprint "eagle-import:APA102-2020")
      (libsource (lib "eagle-import") (part "APA1022020"))
    )
    (comp (ref "U39")
      (value "APA1022020")
      (footprint "eagle-import:APA102-2020")
      (libsource (lib "eagle-import") (part "APA1022020"))
    )
    (comp (ref "U40")
      (value "APA1022020")
      (footprint "eagle-import:APA102-2020")
      (libsource (lib "eagle-import") (part "APA1022020"))
    )
    (comp (ref "U41")
      (value "APA1022020")
      (footprint "eagle-import:APA102-2020")
      (libsource (lib "eagle-import") (part "APA1022020"))
    )
    (comp (ref "U42")
      (value "APA1022020")
      (footprint "eagle-import:APA102-2020")
      (libsource (lib "eagle-import") (part "APA1022020"))
    )
    (comp (ref "U43")
      (value "APA1022020")
      (footprint "eagle-import:APA102-2020")
      (libsource (lib "eagle-import") (part "APA1022020"))
    )
    (comp (ref "U44")
      (value "APA1022020")
      (footprint "eagle-import:APA102-2020")
      (libsource (lib "eagle-import") (part "APA1022020"))
    )
    (comp (ref "U45")
      (value "APA1022020")
      (footprint "eagle-import:APA102-2020")
      (libsource (lib "eagle-import") (part "APA1022020"))
    )
    (comp (ref "U46")
      (value "APA1022020")
      (footprint "eagle-import:APA102-2020")
      (libsource (lib "eagle-import") (part "APA1022020"))
    )
    (comp (ref "U47")
      (value "APA1022020")
      (footprint "eagle-import:APA102-2020")
      (libsource (lib "eagle-import") (part "APA1022020"))
    )
    (comp (ref "U48")
      (value "APA1022020")
      (footprint "eagle-import:APA102-2020")
      (libsource (lib "eagle-import") (part "APA1022020"))
    )
    (comp (ref "U49")
      (value "APA1022020")
      (footprint "eagle-import:APA102-2020")
      (libsource (lib "eagle-import") (part "APA1022020"))
    )
    (comp (ref "U50")
      (value "APA1022020")
      (footprint "eagle-import:APA102-2020")
      (libsource (lib "eagle-import") (part "APA1022020"))
    )
    (comp (ref "U51")
      (value "APA1022020")
      (footprint "eagle-import:APA102-2020")
      (libsource (lib "eagle-import") (part "APA1022020"))
    )
    (comp (ref "U52")
      (value "APA1022020")
      (footprint "eagle-import:APA102-2020")
      (libsource (lib "eagle-import") (part "APA1022020"))
    )
    (comp (ref "U53")
      (value "APA1022020")
      (footprint "eagle-import:APA102-2020")
      (libsource (lib "eagle-import") (part "APA1022020"))
    )
    (comp (ref "U54")
      (value "APA1022020")
      (footprint "eagle-import:APA102-2020")
      (libsource (lib "eagle-import") (part "APA1022020"))
    )
    (comp (ref "U55")
      (value "APA1022020")
      (footprint "eagle-import:APA102-2020")
      (libsource (lib "eagle-import") (part "APA1022020"))
    )
    (comp (ref "U56")
      (value "APA1022020")
      (footprint "eagle-import:APA102-2020")
      (libsource (lib "eagle-import") (part "APA1022020"))
    )
    (comp (ref "U57")
      (value "APA1022020")
      (footprint "eagle-import:APA102-2020")
      (libsource (lib "eagle-import") (part "APA1022020"))
    )
    (comp (ref "U58")
      (value "APA1022020")
      (footprint "eagle-import:APA102-2020")
      (libsource (lib "eagle-import") (part "APA1022020"))
    )
    (comp (ref "U59")
      (value "APA1022020")
      (footprint "eagle-import:APA102-2020")
      (libsource (lib "eagle-import") (part "APA1022020"))
    )
    (comp (ref "U60")
      (value "APA1022020")
      (footprint "eagle-import:APA102-2020")
      (libsource (lib "eagle-import") (part "APA1022020"))
    )
    (comp (ref "U61")
      (value "APA1022020")
      (footprint "eagle-import:APA102-2020")
      (libsource (lib "eagle-import") (part "APA1022020"))
    )
    (comp (ref "U62")
      (value "APA1022020")
      (footprint "eagle-import:APA102-2020")
      (libsource (lib "eagle-import") (part "APA1022020"))
    )
    (comp (ref "U63")
      (value "APA1022020")
      (footprint "eagle-import:APA102-2020")
      (libsource (lib "eagle-import") (part "APA1022020"))
    )
    (comp (ref "U64")
      (value "APA1022020")
      (footprint "eagle-import:APA102-2020")
      (libsource (lib "eagle-import") (part "APA1022020"))
    )
    (comp (ref "U65")
      (value "APA1022020")
      (footprint "eagle-import:APA102-2020")
      (libsource (lib "eagle-import") (part "APA1022020"))
    )
    (comp (ref "U66")
      (value "APA1022020")
      (footprint "eagle-import:APA102-2020")
      (libsource (lib "eagle-import") (part "APA1022020"))
    )
    (comp (ref "U67")
      (value "APA1022020")
      (footprint "eagle-import:APA102-2020")
      (libsource (lib "eagle-import") (part "APA1022020"))
    )
    (comp (ref "U68")
      (value "APA1022020")
      (footprint "eagle-import:APA102-2020")
      (libsource (lib "eagle-import") (part "APA1022020"))
    )
    (comp (ref "U69")
      (value "APA1022020")
      (footprint "eagle-import:APA102-2020")
      (libsource (lib "eagle-import") (part "APA1022020"))
    )
    (comp (ref "U70")
      (value "APA1022020")
      (footprint "eagle-import:APA102-2020")
      (libsource (lib "eagle-import") (part "APA1022020"))
    )
    (comp (ref "U71")
      (value "APA1022020")
      (footprint "eagle-import:APA102-2020")
      (libsource (lib "eagle-import") (part "APA1022020"))
    )
    (comp (ref "U72")
      (value "APA1022020")
      (footprint "eagle-import:APA102-2020")
      (libsource (lib "eagle-import") (part "APA1022020"))
    )
    (comp (ref "U73")
      (value "APA1022020")
      (footprint "eagle-import:APA102-2020")
      (libsource (lib "eagle-import") (part "APA1022020"))
    )
    (comp (ref "U74")
      (value "APA1022020")
      (footprint "eagle-import:APA102-2020")
      (libsource (lib "eagle-import") (part "APA1022020"))
    )
    (comp (ref "U75")
      (value "APA1022020")
      (footprint "eagle-import:APA102-2020")
      (libsource (lib "eagle-import") (part "APA1022020"))
    )
    (comp (ref "U76")
      (value "APA1022020")
      (footprint "eagle-import:APA102-2020")
      (libsource (lib "eagle-import") (part "APA1022020"))
    )
    (comp (ref "U77")
      (value "APA1022020")
      (footprint "eagle-import:APA102-2020")
      (libsource (lib "eagle-import") (part "APA1022020"))
    )
    (comp (ref "U78")
      (value "APA1022020")
      (footprint "eagle-import:APA102-2020")
      (libsource (lib "eagle-import") (part "APA1022020"))
    )
    (comp (ref "U79")
      (value "APA1022020")
      (footprint "eagle-import:APA102-2020")
      (libsource (lib "eagle-import") (part "APA1022020"))
    )
    (comp (ref "U80")
      (value "APA1022020")
      (footprint "eagle-import:APA102-2020")
      (libsource (lib "eagle-import") (part "APA1022020"))
    )
    (comp (ref "U81")
      (value "APA1022020")
      (footprint "eagle-import:APA102-2020")
      (libsource (lib "eagle-import") (part "APA1022020"))
    )
    (comp (ref "U82")
      (value "APA1022020")
      (footprint "eagle-import:APA102-2020")
      (libsource (lib "eagle-import") (part "APA1022020"))
    )
    (comp (ref "U83")
      (value "APA1022020")
      (footprint "eagle-import:APA102-2020")
      (libsource (lib "eagle-import") (part "APA1022020"))
    )
    (comp (ref "U84")
      (value "APA1022020")
      (footprint "eagle-import:APA102-2020")
      (libsource (lib "eagle-import") (part "APA1022020"))
    )
    (comp (ref "U85")
      (value "APA1022020")
      (footprint "eagle-import:APA102-2020")
      (libsource (lib "eagle-import") (part "APA1022020"))
    )
    (comp (ref "U86")
      (value "APA1022020")
      (footprint "eagle-import:APA102-2020")
      (libsource (lib "eagle-import") (part "APA1022020"))
    )
    (comp (ref "U87")
      (value "APA1022020")
      (footprint "eagle-import:APA102-2020")
      (libsource (lib "eagle-import") (part "APA1022020"))
    )
    (comp (ref "U88")
      (value "APA1022020")
      (footprint "eagle-import:APA102-2020")
      (libsource (lib "eagle-import") (part "APA1022020"))
    )
    (comp (ref "U89")
      (value "APA1022020")
      (footprint "eagle-import:APA102-2020")
      (libsource (lib "eagle-import") (part "APA1022020"))
    )
    (comp (ref "U90")
      (value "APA1022020")
      (footprint "eagle-import:APA102-2020")
      (libsource (lib "eagle-import") (part "APA1022020"))
    )
    (comp (ref "U91")
      (value "APA1022020")
      (footprint "eagle-import:APA102-2020")
      (libsource (lib "eagle-import") (part "APA1022020"))
    )
    (comp (ref "U92")
      (value "APA1022020")
      (footprint "eagle-import:APA102-2020")
      (libsource (lib "eagle-import") (part "APA1022020"))
    )
    (comp (ref "U93")
      (value "APA1022020")
      (footprint "eagle-import:APA102-2020")
      (libsource (lib "eagle-import") (part "APA1022020"))
    )
    (comp (ref "U94")
      (value "APA1022020")
      (footprint "eagle-import:APA102-2020")
      (libsource (lib "eagle-import") (part "APA1022020"))
    )
    (comp (ref "U95")
      (value "APA1022020")
      (footprint "eagle-import:APA102-2020")
      (libsource (lib "eagle-import") (part "APA1022020"))
    )
    (comp (ref "U96")
      (value "APA1022020")
      (footprint "eagle-import:APA102-2020")
      (libsource (lib "eagle-import") (part "APA1022020"))
    )
    (comp (ref "U97")
      (value "APA1022020")
      (footprint "eagle-import:APA102-2020")
      (libsource (lib "eagle-import") (part "APA1022020"))
    )
    (comp (ref "U98")
      (value "APA1022020")
      (footprint "eagle-import:APA102-2020")
      (libsource (lib "eagle-import") (part "APA1022020"))
    )
    (comp (ref "U99")
      (value "APA1022020")
      (footprint "eagle-import:APA102-2020")
      (libsource (lib "eagle-import") (part "APA1022020"))
    )
    (comp (ref "U100")
      (value "APA1022020")
      (footprint "eagle-import:APA102-2020")
      (libsource (lib "eagle-import") (part "APA1022020"))
    )
    (comp (ref "U101")
      (value "APA1022020")
      (footprint "eagle-import:APA102-2020")
      (libsource (lib "eagle-import") (part "APA1022020"))
    )
    (comp (ref "U102")
      (value "APA1022020")
      (footprint "eagle-import:APA102-2020")
      (libsource (lib "eagle-import") (part "APA1022020"))
    )
    (comp (ref "U103")
      (value "APA1022020")
      (footprint "eagle-import:APA102-2020")
      (libsource (lib "eagle-import") (part "APA1022020"))
    )
    (comp (ref "U104")
      (value "APA1022020")
      (footprint "eagle-import:APA102-2020")
      (libsource (lib "eagle-import") (part "APA1022020"))
    )
    (comp (ref "U105")
      (value "APA1022020")
      (footprint "eagle-import:APA102-2020")
      (libsource (lib "eagle-import") (part "APA1022020"))
    )
    (comp (ref "U106")
      (value "APA1022020")
      (footprint "eagle-import:APA102-2020")
      (libsource (lib "eagle-import") (part "APA1022020"))
    )
    (comp (ref "U107")
      (value "APA1022020")
      (footprint "eagle-import:APA102-2020")
      (libsource (lib "eagle-import") (part "APA1022020"))
    )
    (comp (ref "U108")
      (value "APA1022020")
      (footprint "eagle-import:APA102-2020")
      (libsource (lib "eagle-import") (part "APA1022020"))
    )
    (comp (ref "U109")
      (value "APA1022020")
      (footprint "eagle-import:APA102-2020")
      (libsource (lib "eagle-import") (part "APA1022020"))
    )
    (comp (ref "U110")
      (value "APA1022020")
      (footprint "eagle-import:APA102-2020")
      (libsource (lib "eagle-import") (part "APA1022020"))
    )
    (comp (ref "U111")
      (value "APA1022020")
      (footprint "eagle-import:APA102-2020")
      (libsource (lib "eagle-import") (part "APA1022020"))
    )
    (comp (ref "U112")
      (value "APA1022020")
      (footprint "eagle-import:APA102-2020")
      (libsource (lib "eagle-import") (part "APA1022020"))
    )
  )
  (nets
    (net (code "1") (name "CK1") (class "Default")
      (node (ref "U28") (pin "CKO") (pinfunction "CO_CKO") (pintype "bidirectional"))
      (node (ref "U29") (pin "CKI") (pinfunction "CI_CKI") (pintype "bidirectional"))
    )
    (net (code "2") (name "CK2") (class "Default")
      (node (ref "U56") (pin "CKO") (pinfunction "CO_CKO") (pintype "bidirectional"))
      (node (ref "U57") (pin "CKI") (pinfunction "CI_CKI") (pintype "bidirectional"))
    )
    (net (code "3") (name "CK3") (class "Default")
      (node (ref "U84") (pin "CKO") (pinfunction "CO_CKO") (pintype "bidirectional"))
      (node (ref "U85") (pin "CKI") (pinfunction "CI_CKI") (pintype "bidirectional"))
    )
    (net (code "4") (name "CK4") (class "Default")
      (node (ref "U112") (pin "CKO") (pinfunction "CO_CKO") (pintype "bidirectional"))
      (node (ref "U113") (pin "CKI") (pinfunction "CI_CKI") (pintype "bidirectional"))
    )
    (net (code "5") (name "CK5") (class "Default")
      (node (ref "U140") (pin "CKO") (pinfunction "CO_CKO") (pintype "bidirectional"))
      (node (ref "U141") (pin "CKI") (pinfunction "CI_CKI") (pintype "bidirectional"))
    )
    (net (code "6") (name "CK6") (class "Default")
      (node (ref "U168") (pin "CKO") (pinfunction "CO_CKO") (pintype "bidirectional"))
      (node (ref "U169") (pin "CKI") (pinfunction "CI_CKI") (pintype "bidirectional"))
    )
    (net (code "7") (name "CK7") (class "Default")
      (node (ref "U196") (pin "CKO") (pinfunction "CO_CKO") (pintype "bidirectional"))
      (node (ref "U197") (pin "CKI") (pinfunction "CI_CKI") (pintype "bidirectional"))
    )
    (net (code "8") (name "CK8") (class "Default")
      (node (ref "U224") (pin "CKO") (pinfunction "CO_CKO") (pintype "bidirectional"))
      (node (ref "U225") (pin "CKI") (pinfunction "CI_CKI") (pintype "bidirectional"))
    )
    (net (code "9") (name "GND") (class "Default")
      (node (ref "J1") (pin "1") (pinfunction "1_1") (pintype "power_in"))
      (node (ref "J2") (pin "1") (pinfunction "1_1") (pintype "power_in"))
      (node (ref "U1") (pin "GND") (pinfunction "GND_GND") (pintype "bidirectional"))
      (node (ref "U1") (pin "GNDPAD") (pinfunction "GND_GNDPAD") (pintype "bidirectional"))
      (node (ref "U10") (pin "GND") (pinfunction "GND_GND") (pintype "bidirectional"))
      (node (ref "U10") (pin "GNDPAD") (pinfunction "GND_GNDPAD") (pintype "bidirectional"))
      (node (ref "U100") (pin "GND") (pinfunction "GND_GND") (pintype "bidirectional"))
      (node (ref "U100") (pin "GNDPAD") (pinfunction "GND_GNDPAD") (pintype "bidirectional"))
      (node (ref "U101") (pin "GND") (pinfunction "GND_GND") (pintype "bidirectional"))
      (node (ref "U101") (pin "GNDPAD") (pinfunction "GND_GNDPAD") (pintype "bidirectional"))
      (node (ref "U102") (pin "GND") (pinfunction "GND_GND") (pintype "bidirectional"))
      (node (ref "U102") (pin "GNDPAD") (pinfunction "GND_GNDPAD") (pintype "bidirectional"))
      (node (ref "U103") (pin "GND") (pinfunction "GND_GND") (pintype "bidirectional"))
      (node (ref "U103") (pin "GNDPAD") (pinfunction "GND_GNDPAD") (pintype "bidirectional"))
      (node (ref "U104") (pin "GND") (pinfunction "GND_GND") (pintype "bidirectional"))
      (node (ref "U104") (pin "GNDPAD") (pinfunction "GND_GNDPAD") (pintype "bidirectional"))
      (node (ref "U105") (pin "GND") (pinfunction "GND_GND") (pintype "bidirectional"))
      (node (ref "U105") (pin "GNDPAD") (pinfunction "GND_GNDPAD") (pintype "bidirectional"))
      (node (ref "U106") (pin "GND") (pinfunction "GND_GND") (pintype "bidirectional"))
      (node (ref "U106") (pin "GNDPAD") (pinfunction "GND_GNDPAD") (pintype "bidirectional"))
      (node (ref "U107") (pin "GND") (pinfunction "GND_GND") (pintype "bidirectional"))
      (node (ref "U107") (pin "GNDPAD") (pinfunction "GND_GNDPAD") (pintype "bidirectional"))
      (node (ref "U108") (pin "GND") (pinfunction "GND_GND") (pintype "bidirectional"))
      (node (ref "U108") (pin "GNDPAD") (pinfunction "GND_GNDPAD") (pintype "bidirectional"))
      (node (ref "U109") (pin "GND") (pinfunction "GND_GND") (pintype "bidirectional"))
      (node (ref "U109") (pin "GNDPAD") (pinfunction "GND_GNDPAD") (pintype "bidirectional"))
      (node (ref "U11") (pin "GND") (pinfunction "GND_GND") (pintype "bidirectional"))
      (node (ref "U11") (pin "GNDPAD") (pinfunction "GND_GNDPAD") (pintype "bidirectional"))
      (node (ref "U110") (pin "GND") (pinfunction "GND_GND") (pintype "bidirectional"))
      (node (ref "U110") (pin "GNDPAD") (pinfunction "GND_GNDPAD") (pintype "bidirectional"))
      (node (ref "U111") (pin "GND") (pinfunction "GND_GND") (pintype "bidirectional"))
      (node (ref "U111") (pin "GNDPAD") (pinfunction "GND_GNDPAD") (pintype "bidirectional"))
      (node (ref "U112") (pin "GND") (pinfunction "GND_GND") (pintype "bidirectional"))
      (node (ref "U112") (pin "GNDPAD") (pinfunction "GND_GNDPAD") (pintype "bidirectional"))
      (node (ref "U113") (pin "GND") (pinfunction "GND_GND") (pintype "bidirectional"))
      (node (ref "U113") (pin "GNDPAD") (pinfunction "GND_GNDPAD") (pintype "bidirectional"))
      (node (ref "U114") (pin "GND") (pinfunction "GND_GND") (pintype "bidirectional"))
      (node (ref "U114") (pin "GNDPAD") (pinfunction "GND_GNDPAD") (pintype "bidirectional"))
      (node (ref "U115") (pin "GND") (pinfunction "GND_GND") (pintype "bidirectional"))
      (node (ref "U115") (pin "GNDPAD") (pinfunction "GND_GNDPAD") (pintype "bidirectional"))
      (node (ref "U116") (pin "GND") (pinfunction "GND_GND") (pintype "bidirectional"))
      (node (ref "U116") (pin "GNDPAD") (pinfunction "GND_GNDPAD") (pintype "bidirectional"))
      (node (ref "U117") (pin "GND") (pinfunction "GND_GND") (pintype "bidirectional"))
      (node (ref "U117") (pin "GNDPAD") (pinfunction "GND_GNDPAD") (pintype "bidirectional"))
      (node (ref "U118") (pin "GND") (pinfunction "GND_GND") (pintype "bidirectional"))
      (node (ref "U118") (pin "GNDPAD") (pinfunction "GND_GNDPAD") (pintype "bidirectional"))
      (node (ref "U119") (pin "GND") (pinfunction "GND_GND") (pintype "bidirectional"))
      (node (ref "U119") (pin "GNDPAD") (pinfunction "GND_GNDPAD") (pintype "bidirectional"))
      (node (ref "U12") (pin "GND") (pinfunction "GND_GND") (pintype "bidirectional"))
      (node (ref "U12") (pin "GNDPAD") (pinfunction "GND_GNDPAD") (pintype "bidirectional"))
      (node (ref "U120") (pin "GND") (pinfunction "GND_GND") (pintype "bidirectional"))
      (node (ref "U120") (pin "GNDPAD") (pinfunction "GND_GNDPAD") (pintype "bidirectional"))
      (node (ref "U121") (pin "GND") (pinfunction "GND_GND") (pintype "bidirectional"))
      (node (ref "U121") (pin "GNDPAD") (pinfunction "GND_GNDPAD") (pintype "bidirectional"))
      (node (ref "U122") (pin "GND") (pinfunction "GND_GND") (pintype "bidirectional"))
      (node (ref "U122") (pin "GNDPAD") (pinfunction "GND_GNDPAD") (pintype "bidirectional"))
      (node (ref "U123") (pin "GND") (pinfunction "GND_GND") (pintype "bidirectional"))
      (node (ref "U123") (pin "GNDPAD") (pinfunction "GND_GNDPAD") (pintype "bidirectional"))
      (node (ref "U124") (pin "GND") (pinfunction "GND_GND") (pintype "bidirectional"))
      (node (ref "U124") (pin "GNDPAD") (pinfunction "GND_GNDPAD") (pintype "bidirectional"))
      (node (ref "U125") (pin "GND") (pinfunction "GND_GND") (pintype "bidirectional"))
      (node (ref "U125") (pin "GNDPAD") (pinfunction "GND_GNDPAD") (pintype "bidirectional"))
      (node (ref "U126") (pin "GND") (pinfunction "GND_GND") (pintype "bidirectional"))
      (node (ref "U126") (pin "GNDPAD") (pinfunction "GND_GNDPAD") (pintype "bidirectional"))
      (node (ref "U127") (pin "GND") (pinfunction "GND_GND") (pintype "bidirectional"))
      (node (ref "U127") (pin "GNDPAD") (pinfunction "GND_GNDPAD") (pintype "bidirectional"))
      (node (ref "U128") (pin "GND") (pinfunction "GND_GND") (pintype "bidirectional"))
      (node (ref "U128") (pin "GNDPAD") (pinfunction "GND_GNDPAD") (pintype "bidirectional"))
      (node (ref "U129") (pin "GND") (pinfunction "GND_GND") (pintype "bidirectional"))
      (node (ref "U129") (pin "GNDPAD") (pinfunction "GND_GNDPAD") (pintype "bidirectional"))
      (node (ref "U13") (pin "GND") (pinfunction "GND_GND") (pintype "bidirectional"))
      (node (ref "U13") (pin "GNDPAD") (pinfunction "GND_GNDPAD") (pintype "bidirectional"))
      (node (ref "U130") (pin "GND") (pinfunction "GND_GND") (pintype "bidirectional"))
      (node (ref "U130") (pin "GNDPAD") (pinfunction "GND_GNDPAD") (pintype "bidirectional"))
      (node (ref "U131") (pin "GND") (pinfunction "GND_GND") (pintype "bidirectional"))
      (node (ref "U131") (pin "GNDPAD") (pinfunction "GND_GNDPAD") (pintype "bidirectional"))
      (node (ref "U132") (pin "GND") (pinfunction "GND_GND") (pintype "bidirectional"))
      (node (ref "U132") (pin "GNDPAD") (pinfunction "GND_GNDPAD") (pintype "bidirectional"))
      (node (ref "U133") (pin "GND") (pinfunction "GND_GND") (pintype "bidirectional"))
      (node (ref "U133") (pin "GNDPAD") (pinfunction "GND_GNDPAD") (pintype "bidirectional"))
      (node (ref "U134") (pin "GND") (pinfunction "GND_GND") (pintype "bidirectional"))
      (node (ref "U134") (pin "GNDPAD") (pinfunction "GND_GNDPAD") (pintype "bidirectional"))
      (node (ref "U135") (pin "GND") (pinfunction "GND_GND") (pintype "bidirectional"))
      (node (ref "U135") (pin "GNDPAD") (pinfunction "GND_GNDPAD") (pintype "bidirectional"))
      (node (ref "U136") (pin "GND") (pinfunction "GND_GND") (pintype "bidirectional"))
      (node (ref "U136") (pin "GNDPAD") (pinfunction "GND_GNDPAD") (pintype "bidirectional"))
      (node (ref "U137") (pin "GND") (pinfunction "GND_GND") (pintype "bidirectional"))
      (node (ref "U137") (pin "GNDPAD") (pinfunction "GND_GNDPAD") (pintype "bidirectional"))
      (node (ref "U138") (pin "GND") (pinfunction "GND_GND") (pintype "bidirectional"))
      (node (ref "U138") (pin "GNDPAD") (pinfunction "GND_GNDPAD") (pintype "bidirectional"))
      (node (ref "U139") (pin "GND") (pinfunction "GND_GND") (pintype "bidirectional"))
      (node (ref "U139") (pin "GNDPAD") (pinfunction "GND_GNDPAD") (pintype "bidirectional"))
      (node (ref "U14") (pin "GND") (pinfunction "GND_GND") (pintype "bidirectional"))
      (node (ref "U14") (pin "GNDPAD") (pinfunction "GND_GNDPAD") (pintype "bidirectional"))
      (node (ref "U140") (pin "GND") (pinfunction "GND_GND") (pintype "bidirectional"))
      (node (ref "U140") (pin "GNDPAD") (pinfunction "GND_GNDPAD") (pintype "bidirectional"))
      (node (ref "U141") (pin "GND") (pinfunction "GND_GND") (pintype "bidirectional"))
      (node (ref "U141") (pin "GNDPAD") (pinfunction "GND_GNDPAD") (pintype "bidirectional"))
      (node (ref "U142") (pin "GND") (pinfunction "GND_GND") (pintype "bidirectional"))
      (node (ref "U142") (pin "GNDPAD") (pinfunction "GND_GNDPAD") (pintype "bidirectional"))
      (node (ref "U143") (pin "GND") (pinfunction "GND_GND") (pintype "bidirectional"))
      (node (ref "U143") (pin "GNDPAD") (pinfunction "GND_GNDPAD") (pintype "bidirectional"))
      (node (ref "U144") (pin "GND") (pinfunction "GND_GND") (pintype "bidirectional"))
      (node (ref "U144") (pin "GNDPAD") (pinfunction "GND_GNDPAD") (pintype "bidirectional"))
      (node (ref "U145") (pin "GND") (pinfunction "GND_GND") (pintype "bidirectional"))
      (node (ref "U145") (pin "GNDPAD") (pinfunction "GND_GNDPAD") (pintype "bidirectional"))
      (node (ref "U146") (pin "GND") (pinfunction "GND_GND") (pintype "bidirectional"))
      (node (ref "U146") (pin "GNDPAD") (pinfunction "GND_GNDPAD") (pintype "bidirectional"))
      (node (ref "U147") (pin "GND") (pinfunction "GND_GND") (pintype "bidirectional"))
      (node (ref "U147") (pin "GNDPAD") (pinfunction "GND_GNDPAD") (pintype "bidirectional"))
      (node (ref "U148") (pin "GND") (pinfunction "GND_GND") (pintype "bidirectional"))
      (node (ref "U148") (pin "GNDPAD") (pinfunction "GND_GNDPAD") (pintype "bidirectional"))
      (node (ref "U149") (pin "GND") (pinfunction "GND_GND") (pintype "bidirectional"))
      (node (ref "U149") (pin "GNDPAD") (pinfunction "GND_GNDPAD") (pintype "bidirectional"))
      (node (ref "U15") (pin "GND") (pinfunction "GND_GND") (pintype "bidirectional"))
      (node (ref "U15") (pin "GNDPAD") (pinfunction "GND_GNDPAD") (pintype "bidirectional"))
      (node (ref "U150") (pin "GND") (pinfunction "GND_GND") (pintype "bidirectional"))
      (node (ref "U150") (pin "GNDPAD") (pinfunction "GND_GNDPAD") (pintype "bidirectional"))
      (node (ref "U151") (pin "GND") (pinfunction "GND_GND") (pintype "bidirectional"))
      (node (ref "U151") (pin "GNDPAD") (pinfunction "GND_GNDPAD") (pintype "bidirectional"))
      (node (ref "U152") (pin "GND") (pinfunction "GND_GND") (pintype "bidirectional"))
      (node (ref "U152") (pin "GNDPAD") (pinfunction "GND_GNDPAD") (pintype "bidirectional"))
      (node (ref "U153") (pin "GND") (pinfunction "GND_GND") (pintype "bidirectional"))
      (node (ref "U153") (pin "GNDPAD") (pinfunction "GND_GNDPAD") (pintype "bidirectional"))
      (node (ref "U154") (pin "GND") (pinfunction "GND_GND") (pintype "bidirectional"))
      (node (ref "U154") (pin "GNDPAD") (pinfunction "GND_GNDPAD") (pintype "bidirectional"))
      (node (ref "U155") (pin "GND") (pinfunction "GND_GND") (pintype "bidirectional"))
      (node (ref "U155") (pin "GNDPAD") (pinfunction "GND_GNDPAD") (pintype "bidirectional"))
      (node (ref "U156") (pin "GND") (pinfunction "GND_GND") (pintype "bidirectional"))
      (node (ref "U156") (pin "GNDPAD") (pinfunction "GND_GNDPAD") (pintype "bidirectional"))
      (node (ref "U157") (pin "GND") (pinfunction "GND_GND") (pintype "bidirectional"))
      (node (ref "U157") (pin "GNDPAD") (pinfunction "GND_GNDPAD") (pintype "bidirectional"))
      (node (ref "U158") (pin "GND") (pinfunction "GND_GND") (pintype "bidirectional"))
      (node (ref "U158") (pin "GNDPAD") (pinfunction "GND_GNDPAD") (pintype "bidirectional"))
      (node (ref "U159") (pin "GND") (pinfunction "GND_GND") (pintype "bidirectional"))
      (node (ref "U159") (pin "GNDPAD") (pinfunction "GND_GNDPAD") (pintype "bidirectional"))
      (node (ref "U16") (pin "GND") (pinfunction "GND_GND") (pintype "bidirectional"))
      (node (ref "U16") (pin "GNDPAD") (pinfunction "GND_GNDPAD") (pintype "bidirectional"))
      (node (ref "U160") (pin "GND") (pinfunction "GND_GND") (pintype "bidirectional"))
      (node (ref "U160") (pin "GNDPAD") (pinfunction "GND_GNDPAD") (pintype "bidirectional"))
      (node (ref "U161") (pin "GND") (pinfunction "GND_GND") (pintype "bidirectional"))
      (node (ref "U161") (pin "GNDPAD") (pinfunction "GND_GNDPAD") (pintype "bidirectional"))
      (node (ref "U162") (pin "GND") (pinfunction "GND_GND") (pintype "bidirectional"))
      (node (ref "U162") (pin "GNDPAD") (pinfunction "GND_GNDPAD") (pintype "bidirectional"))
      (node (ref "U163") (pin "GND") (pinfunction "GND_GND") (pintype "bidirectional"))
      (node (ref "U163") (pin "GNDPAD") (pinfunction "GND_GNDPAD") (pintype "bidirectional"))
      (node (ref "U164") (pin "GND") (pinfunction "GND_GND") (pintype "bidirectional"))
      (node (ref "U164") (pin "GNDPAD") (pinfunction "GND_GNDPAD") (pintype "bidirectional"))
      (node (ref "U165") (pin "GND") (pinfunction "GND_GND") (pintype "bidirectional"))
      (node (ref "U165") (pin "GNDPAD") (pinfunction "GND_GNDPAD") (pintype "bidirectional"))
      (node (ref "U166") (pin "GND") (pinfunction "GND_GND") (pintype "bidirectional"))
      (node (ref "U166") (pin "GNDPAD") (pinfunction "GND_GNDPAD") (pintype "bidirectional"))
      (node (ref "U167") (pin "GND") (pinfunction "GND_GND") (pintype "bidirectional"))
      (node (ref "U167") (pin "GNDPAD") (pinfunction "GND_GNDPAD") (pintype "bidirectional"))
      (node (ref "U168") (pin "GND") (pinfunction "GND_GND") (pintype "bidirectional"))
      (node (ref "U168") (pin "GNDPAD") (pinfunction "GND_GNDPAD") (pintype "bidirectional"))
      (node (ref "U169") (pin "GND") (pinfunction "GND_GND") (pintype "bidirectional"))
      (node (ref "U169") (pin "GNDPAD") (pinfunction "GND_GNDPAD") (pintype "bidirectional"))
      (node (ref "U17") (pin "GND") (pinfunction "GND_GND") (pintype "bidirectional"))
      (node (ref "U17") (pin "GNDPAD") (pinfunction "GND_GNDPAD") (pintype "bidirectional"))
      (node (ref "U170") (pin "GND") (pinfunction "GND_GND") (pintype "bidirectional"))
      (node (ref "U170") (pin "GNDPAD") (pinfunction "GND_GNDPAD") (pintype "bidirectional"))
      (node (ref "U171") (pin "GND") (pinfunction "GND_GND") (pintype "bidirectional"))
      (node (ref "U171") (pin "GNDPAD") (pinfunction "GND_GNDPAD") (pintype "bidirectional"))
      (node (ref "U172") (pin "GND") (pinfunction "GND_GND") (pintype "bidirectional"))
      (node (ref "U172") (pin "GNDPAD") (pinfunction "GND_GNDPAD") (pintype "bidirectional"))
      (node (ref "U173") (pin "GND") (pinfunction "GND_GND") (pintype "bidirectional"))
      (node (ref "U173") (pin "GNDPAD") (pinfunction "GND_GNDPAD") (pintype "bidirectional"))
      (node (ref "U174") (pin "GND") (pinfunction "GND_GND") (pintype "bidirectional"))
      (node (ref "U174") (pin "GNDPAD") (pinfunction "GND_GNDPAD") (pintype "bidirectional"))
      (node (ref "U175") (pin "GND") (pinfunction "GND_GND") (pintype "bidirectional"))
      (node (ref "U175") (pin "GNDPAD") (pinfunction "GND_GNDPAD") (pintype "bidirectional"))
      (node (ref "U176") (pin "GND") (pinfunction "GND_GND") (pintype "bidirectional"))
      (node (ref "U176") (pin "GNDPAD") (pinfunction "GND_GNDPAD") (pintype "bidirectional"))
      (node (ref "U177") (pin "GND") (pinfunction "GND_GND") (pintype "bidirectional"))
      (node (ref "U177") (pin "GNDPAD") (pinfunction "GND_GNDPAD") (pintype "bidirectional"))
      (node (ref "U178") (pin "GND") (pinfunction "GND_GND") (pintype "bidirectional"))
      (node (ref "U178") (pin "GNDPAD") (pinfunction "GND_GNDPAD") (pintype "bidirectional"))
      (node (ref "U179") (pin "GND") (pinfunction "GND_GND") (pintype "bidirectional"))
      (node (ref "U179") (pin "GNDPAD") (pinfunction "GND_GNDPAD") (pintype "bidirectional"))
      (node (ref "U18") (pin "GND") (pinfunction "GND_GND") (pintype "bidirectional"))
      (node (ref "U18") (pin "GNDPAD") (pinfunction "GND_GNDPAD") (pintype "bidirectional"))
      (node (ref "U180") (pin "GND") (pinfunction "GND_GND") (pintype "bidirectional"))
      (node (ref "U180") (pin "GNDPAD") (pinfunction "GND_GNDPAD") (pintype "bidirectional"))
      (node (ref "U181") (pin "GND") (pinfunction "GND_GND") (pintype "bidirectional"))
      (node (ref "U181") (pin "GNDPAD") (pinfunction "GND_GNDPAD") (pintype "bidirectional"))
      (node (ref "U182") (pin "GND") (pinfunction "GND_GND") (pintype "bidirectional"))
      (node (ref "U182") (pin "GNDPAD") (pinfunction "GND_GNDPAD") (pintype "bidirectional"))
      (node (ref "U183") (pin "GND") (pinfunction "GND_GND") (pintype "bidirectional"))
      (node (ref "U183") (pin "GNDPAD") (pinfunction "GND_GNDPAD") (pintype "bidirectional"))
      (node (ref "U184") (pin "GND") (pinfunction "GND_GND") (pintype "bidirectional"))
      (node (ref "U184") (pin "GNDPAD") (pinfunction "GND_GNDPAD") (pintype "bidirectional"))
      (node (ref "U185") (pin "GND") (pinfunction "GND_GND") (pintype "bidirectional"))
      (node (ref "U185") (pin "GNDPAD") (pinfunction "GND_GNDPAD") (pintype "bidirectional"))
      (node (ref "U186") (pin "GND") (pinfunction "GND_GND") (pintype "bidirectional"))
      (node (ref "U186") (pin "GNDPAD") (pinfunction "GND_GNDPAD") (pintype "bidirectional"))
      (node (ref "U187") (pin "GND") (pinfunction "GND_GND") (pintype "bidirectional"))
      (node (ref "U187") (pin "GNDPAD") (pinfunction "GND_GNDPAD") (pintype "bidirectional"))
      (node (ref "U188") (pin "GND") (pinfunction "GND_GND") (pintype "bidirectional"))
      (node (ref "U188") (pin "GNDPAD") (pinfunction "GND_GNDPAD") (pintype "bidirectional"))
      (node (ref "U189") (pin "GND") (pinfunction "GND_GND") (pintype "bidirectional"))
      (node (ref "U189") (pin "GNDPAD") (pinfunction "GND_GNDPAD") (pintype "bidirectional"))
      (node (ref "U19") (pin "GND") (pinfunction "GND_GND") (pintype "bidirectional"))
      (node (ref "U19") (pin "GNDPAD") (pinfunction "GND_GNDPAD") (pintype "bidirectional"))
      (node (ref "U190") (pin "GND") (pinfunction "GND_GND") (pintype "bidirectional"))
      (node (ref "U190") (pin "GNDPAD") (pinfunction "GND_GNDPAD") (pintype "bidirectional"))
      (node (ref "U191") (pin "GND") (pinfunction "GND_GND") (pintype "bidirectional"))
      (node (ref "U191") (pin "GNDPAD") (pinfunction "GND_GNDPAD") (pintype "bidirectional"))
      (node (ref "U192") (pin "GND") (pinfunction "GND_GND") (pintype "bidirectional"))
      (node (ref "U192") (pin "GNDPAD") (pinfunction "GND_GNDPAD") (pintype "bidirectional"))
      (node (ref "U193") (pin "GND") (pinfunction "GND_GND") (pintype "bidirectional"))
      (node (ref "U193") (pin "GNDPAD") (pinfunction "GND_GNDPAD") (pintype "bidirectional"))
      (node (ref "U194") (pin "GND") (pinfunction "GND_GND") (pintype "bidirectional"))
      (node (ref "U194") (pin "GNDPAD") (pinfunction "GND_GNDPAD") (pintype "bidirectional"))
      (node (ref "U195") (pin "GND") (pinfunction "GND_GND") (pintype "bidirectional"))
      (node (ref "U195") (pin "GNDPAD") (pinfunction "GND_GNDPAD") (pintype "bidirectional"))
      (node (ref "U196") (pin "GND") (pinfunction "GND_GND") (pintype "bidirectional"))
      (node (ref "U196") (pin "GNDPAD") (pinfunction "GND_GNDPAD") (pintype "bidirectional"))
      (node (ref "U197") (pin "GND") (pinfunction "GND_GND") (pintype "bidirectional"))
      (node (ref "U197") (pin "GNDPAD") (pinfunction "GND_GNDPAD") (pintype "bidirectional"))
      (node (ref "U198") (pin "GND") (pinfunction "GND_GND") (pintype "bidirectional"))
      (node (ref "U198") (pin "GNDPAD") (pinfunction "GND_GNDPAD") (pintype "bidirectional"))
      (node (ref "U199") (pin "GND") (pinfunction "GND_GND") (pintype "bidirectional"))
      (node (ref "U199") (pin "GNDPAD") (pinfunction "GND_GNDPAD") (pintype "bidirectional"))
      (node (ref "U2") (pin "GND") (pinfunction "GND_GND") (pintype "bidirectional"))
      (node (ref "U2") (pin "GNDPAD") (pinfunction "GND_GNDPAD") (pintype "bidirectional"))
      (node (ref "U20") (pin "GND") (pinfunction "GND_GND") (pintype "bidirectional"))
      (node (ref "U20") (pin "GNDPAD") (pinfunction "GND_GNDPAD") (pintype "bidirectional"))
      (node (ref "U200") (pin "GND") (pinfunction "GND_GND") (pintype "bidirectional"))
      (node (ref "U200") (pin "GNDPAD") (pinfunction "GND_GNDPAD") (pintype "bidirectional"))
      (node (ref "U201") (pin "GND") (pinfunction "GND_GND") (pintype "bidirectional"))
      (node (ref "U201") (pin "GNDPAD") (pinfunction "GND_GNDPAD") (pintype "bidirectional"))
      (node (ref "U202") (pin "GND") (pinfunction "GND_GND") (pintype "bidirectional"))
      (node (ref "U202") (pin "GNDPAD") (pinfunction "GND_GNDPAD") (pintype "bidirectional"))
      (node (ref "U203") (pin "GND") (pinfunction "GND_GND") (pintype "bidirectional"))
      (node (ref "U203") (pin "GNDPAD") (pinfunction "GND_GNDPAD") (pintype "bidirectional"))
      (node (ref "U204") (pin "GND") (pinfunction "GND_GND") (pintype "bidirectional"))
      (node (ref "U204") (pin "GNDPAD") (pinfunction "GND_GNDPAD") (pintype "bidirectional"))
      (node (ref "U205") (pin "GND") (pinfunction "GND_GND") (pintype "bidirectional"))
      (node (ref "U205") (pin "GNDPAD") (pinfunction "GND_GNDPAD") (pintype "bidirectional"))
      (node (ref "U206") (pin "GND") (pinfunction "GND_GND") (pintype "bidirectional"))
      (node (ref "U206") (pin "GNDPAD") (pinfunction "GND_GNDPAD") (pintype "bidirectional"))
      (node (ref "U207") (pin "GND") (pinfunction "GND_GND") (pintype "bidirectional"))
      (node (ref "U207") (pin "GNDPAD") (pinfunction "GND_GNDPAD") (pintype "bidirectional"))
      (node (ref "U208") (pin "GND") (pinfunction "GND_GND") (pintype "bidirectional"))
      (node (ref "U208") (pin "GNDPAD") (pinfunction "GND_GNDPAD") (pintype "bidirectional"))
      (node (ref "U209") (pin "GND") (pinfunction "GND_GND") (pintype "bidirectional"))
      (node (ref "U209") (pin "GNDPAD") (pinfunction "GND_GNDPAD") (pintype "bidirectional"))
      (node (ref "U21") (pin "GND") (pinfunction "GND_GND") (pintype "bidirectional"))
      (node (ref "U21") (pin "GNDPAD") (pinfunction "GND_GNDPAD") (pintype "bidirectional"))
      (node (ref "U210") (pin "GND") (pinfunction "GND_GND") (pintype "bidirectional"))
      (node (ref "U210") (pin "GNDPAD") (pinfunction "GND_GNDPAD") (pintype "bidirectional"))
      (node (ref "U211") (pin "GND") (pinfunction "GND_GND") (pintype "bidirectional"))
      (node (ref "U211") (pin "GNDPAD") (pinfunction "GND_GNDPAD") (pintype "bidirectional"))
      (node (ref "U212") (pin "GND") (pinfunction "GND_GND") (pintype "bidirectional"))
      (node (ref "U212") (pin "GNDPAD") (pinfunction "GND_GNDPAD") (pintype "bidirectional"))
      (node (ref "U213") (pin "GND") (pinfunction "GND_GND") (pintype "bidirectional"))
      (node (ref "U213") (pin "GNDPAD") (pinfunction "GND_GNDPAD") (pintype "bidirectional"))
      (node (ref "U214") (pin "GND") (pinfunction "GND_GND") (pintype "bidirectional"))
      (node (ref "U214") (pin "GNDPAD") (pinfunction "GND_GNDPAD") (pintype "bidirectional"))
      (node (ref "U215") (pin "GND") (pinfunction "GND_GND") (pintype "bidirectional"))
      (node (ref "U215") (pin "GNDPAD") (pinfunction "GND_GNDPAD") (pintype "bidirectional"))
      (node (ref "U216") (pin "GND") (pinfunction "GND_GND") (pintype "bidirectional"))
      (node (ref "U216") (pin "GNDPAD") (pinfunction "GND_GNDPAD") (pintype "bidirectional"))
      (node (ref "U217") (pin "GND") (pinfunction "GND_GND") (pintype "bidirectional"))
      (node (ref "U217") (pin "GNDPAD") (pinfunction "GND_GNDPAD") (pintype "bidirectional"))
      (node (ref "U218") (pin "GND") (pinfunction "GND_GND") (pintype "bidirectional"))
      (node (ref "U218") (pin "GNDPAD") (pinfunction "GND_GNDPAD") (pintype "bidirectional"))
      (node (ref "U219") (pin "GND") (pinfunction "GND_GND") (pintype "bidirectional"))
      (node (ref "U219") (pin "GNDPAD") (pinfunction "GND_GNDPAD") (pintype "bidirectional"))
      (node (ref "U22") (pin "GND") (pinfunction "GND_GND") (pintype "bidirectional"))
      (node (ref "U22") (pin "GNDPAD") (pinfunction "GND_GNDPAD") (pintype "bidirectional"))
      (node (ref "U220") (pin "GND") (pinfunction "GND_GND") (pintype "bidirectional"))
      (node (ref "U220") (pin "GNDPAD") (pinfunction "GND_GNDPAD") (pintype "bidirectional"))
      (node (ref "U221") (pin "GND") (pinfunction "GND_GND") (pintype "bidirectional"))
      (node (ref "U221") (pin "GNDPAD") (pinfunction "GND_GNDPAD") (pintype "bidirectional"))
      (node (ref "U222") (pin "GND") (pinfunction "GND_GND") (pintype "bidirectional"))
      (node (ref "U222") (pin "GNDPAD") (pinfunction "GND_GNDPAD") (pintype "bidirectional"))
      (node (ref "U223") (pin "GND") (pinfunction "GND_GND") (pintype "bidirectional"))
      (node (ref "U223") (pin "GNDPAD") (pinfunction "GND_GNDPAD") (pintype "bidirectional"))
      (node (ref "U224") (pin "GND") (pinfunction "GND_GND") (pintype "bidirectional"))
      (node (ref "U224") (pin "GNDPAD") (pinfunction "GND_GNDPAD") (pintype "bidirectional"))
      (node (ref "U225") (pin "GND") (pinfunction "GND_GND") (pintype "bidirectional"))
      (node (ref "U225") (pin "GNDPAD") (pinfunction "GND_GNDPAD") (pintype "bidirectional"))
      (node (ref "U226") (pin "GND") (pinfunction "GND_GND") (pintype "bidirectional"))
      (node (ref "U226") (pin "GNDPAD") (pinfunction "GND_GNDPAD") (pintype "bidirectional"))
      (node (ref "U227") (pin "GND") (pinfunction "GND_GND") (pintype "bidirectional"))
      (node (ref "U227") (pin "GNDPAD") (pinfunction "GND_GNDPAD") (pintype "bidirectional"))
      (node (ref "U228") (pin "GND") (pinfunction "GND_GND") (pintype "bidirectional"))
      (node (ref "U228") (pin "GNDPAD") (pinfunction "GND_GNDPAD") (pintype "bidirectional"))
      (node (ref "U229") (pin "GND") (pinfunction "GND_GND") (pintype "bidirectional"))
      (node (ref "U229") (pin "GNDPAD") (pinfunction "GND_GNDPAD") (pintype "bidirectional"))
      (node (ref "U23") (pin "GND") (pinfunction "GND_GND") (pintype "bidirectional"))
      (node (ref "U23") (pin "GNDPAD") (pinfunction "GND_GNDPAD") (pintype "bidirectional"))
      (node (ref "U230") (pin "GND") (pinfunction "GND_GND") (pintype "bidirectional"))
      (node (ref "U230") (pin "GNDPAD") (pinfunction "GND_GNDPAD") (pintype "bidirectional"))
      (node (ref "U231") (pin "GND") (pinfunction "GND_GND") (pintype "bidirectional"))
      (node (ref "U231") (pin "GNDPAD") (pinfunction "GND_GNDPAD") (pintype "bidirectional"))
      (node (ref "U232") (pin "GND") (pinfunction "GND_GND") (pintype "bidirectional"))
      (node (ref "U232") (pin "GNDPAD") (pinfunction "GND_GNDPAD") (pintype "bidirectional"))
      (node (ref "U233") (pin "GND") (pinfunction "GND_GND") (pintype "bidirectional"))
      (node (ref "U233") (pin "GNDPAD") (pinfunction "GND_GNDPAD") (pintype "bidirectional"))
      (node (ref "U234") (pin "GND") (pinfunction "GND_GND") (pintype "bidirectional"))
      (node (ref "U234") (pin "GNDPAD") (pinfunction "GND_GNDPAD") (pintype "bidirectional"))
      (node (ref "U235") (pin "GND") (pinfunction "GND_GND") (pintype "bidirectional"))
      (node (ref "U235") (pin "GNDPAD") (pinfunction "GND_GNDPAD") (pintype "bidirectional"))
      (node (ref "U236") (pin "GND") (pinfunction "GND_GND") (pintype "bidirectional"))
      (node (ref "U236") (pin "GNDPAD") (pinfunction "GND_GNDPAD") (pintype "bidirectional"))
      (node (ref "U237") (pin "GND") (pinfunction "GND_GND") (pintype "bidirectional"))
      (node (ref "U237") (pin "GNDPAD") (pinfunction "GND_GNDPAD") (pintype "bidirectional"))
      (node (ref "U238") (pin "GND") (pinfunction "GND_GND") (pintype "bidirectional"))
      (node (ref "U238") (pin "GNDPAD") (pinfunction "GND_GNDPAD") (pintype "bidirectional"))
      (node (ref "U239") (pin "GND") (pinfunction "GND_GND") (pintype "bidirectional"))
      (node (ref "U239") (pin "GNDPAD") (pinfunction "GND_GNDPAD") (pintype "bidirectional"))
      (node (ref "U24") (pin "GND") (pinfunction "GND_GND") (pintype "bidirectional"))
      (node (ref "U24") (pin "GNDPAD") (pinfunction "GND_GNDPAD") (pintype "bidirectional"))
      (node (ref "U240") (pin "GND") (pinfunction "GND_GND") (pintype "bidirectional"))
      (node (ref "U240") (pin "GNDPAD") (pinfunction "GND_GNDPAD") (pintype "bidirectional"))
      (node (ref "U241") (pin "GND") (pinfunction "GND_GND") (pintype "bidirectional"))
      (node (ref "U241") (pin "GNDPAD") (pinfunction "GND_GNDPAD") (pintype "bidirectional"))
      (node (ref "U242") (pin "GND") (pinfunction "GND_GND") (pintype "bidirectional"))
      (node (ref "U242") (pin "GNDPAD") (pinfunction "GND_GNDPAD") (pintype "bidirectional"))
      (node (ref "U243") (pin "GND") (pinfunction "GND_GND") (pintype "bidirectional"))
      (node (ref "U243") (pin "GNDPAD") (pinfunction "GND_GNDPAD") (pintype "bidirectional"))
      (node (ref "U244") (pin "GND") (pinfunction "GND_GND") (pintype "bidirectional"))
      (node (ref "U244") (pin "GNDPAD") (pinfunction "GND_GNDPAD") (pintype "bidirectional"))
      (node (ref "U245") (pin "GND") (pinfunction "GND_GND") (pintype "bidirectional"))
      (node (ref "U245") (pin "GNDPAD") (pinfunction "GND_GNDPAD") (pintype "bidirectional"))
      (node (ref "U246") (pin "GND") (pinfunction "GND_GND") (pintype "bidirectional"))
      (node (ref "U246") (pin "GNDPAD") (pinfunction "GND_GNDPAD") (pintype "bidirectional"))
      (node (ref "U247") (pin "GND") (pinfunction "GND_GND") (pintype "bidirectional"))
      (node (ref "U247") (pin "GNDPAD") (pinfunction "GND_GNDPAD") (pintype "bidirectional"))
      (node (ref "U248") (pin "GND") (pinfunction "GND_GND") (pintype "bidirectional"))
      (node (ref "U248") (pin "GNDPAD") (pinfunction "GND_GNDPAD") (pintype "bidirectional"))
      (node (ref "U249") (pin "GND") (pinfunction "GND_GND") (pintype "bidirectional"))
      (node (ref "U249") (pin "GNDPAD") (pinfunction "GND_GNDPAD") (pintype "bidirectional"))
      (node (ref "U25") (pin "GND") (pinfunction "GND_GND") (pintype "bidirectional"))
      (node (ref "U25") (pin "GNDPAD") (pinfunction "GND_GNDPAD") (pintype "bidirectional"))
      (node (ref "U250") (pin "GND") (pinfunction "GND_GND") (pintype "bidirectional"))
      (node (ref "U250") (pin "GNDPAD") (pinfunction "GND_GNDPAD") (pintype "bidirectional"))
      (node (ref "U251") (pin "GND") (pinfunction "GND_GND") (pintype "bidirectional"))
      (node (ref "U251") (pin "GNDPAD") (pinfunction "GND_GNDPAD") (pintype "bidirectional"))
      (node (ref "U252") (pin "GND") (pinfunction "GND_GND") (pintype "bidirectional"))
      (node (ref "U252") (pin "GNDPAD") (pinfunction "GND_GNDPAD") (pintype "bidirectional"))
      (node (ref "U26") (pin "GND") (pinfunction "GND_GND") (pintype "bidirectional"))
      (node (ref "U26") (pin "GNDPAD") (pinfunction "GND_GNDPAD") (pintype "bidirectional"))
      (node (ref "U27") (pin "GND") (pinfunction "GND_GND") (pintype "bidirectional"))
      (node (ref "U27") (pin "GNDPAD") (pinfunction "GND_GNDPAD") (pintype "bidirectional"))
      (node (ref "U28") (pin "GND") (pinfunction "GND_GND") (pintype "bidirectional"))
      (node (ref "U28") (pin "GNDPAD") (pinfunction "GND_GNDPAD") (pintype "bidirectional"))
      (node (ref "U29") (pin "GND") (pinfunction "GND_GND") (pintype "bidirectional"))
      (node (ref "U29") (pin "GNDPAD") (pinfunction "GND_GNDPAD") (pintype "bidirectional"))
      (node (ref "U3") (pin "GND") (pinfunction "GND_GND") (pintype "bidirectional"))
      (node (ref "U3") (pin "GNDPAD") (pinfunction "GND_GNDPAD") (pintype "bidirectional"))
      (node (ref "U30") (pin "GND") (pinfunction "GND_GND") (pintype "bidirectional"))
      (node (ref "U30") (pin "GNDPAD") (pinfunction "GND_GNDPAD") (pintype "bidirectional"))
      (node (ref "U31") (pin "GND") (pinfunction "GND_GND") (pintype "bidirectional"))
      (node (ref "U31") (pin "GNDPAD") (pinfunction "GND_GNDPAD") (pintype "bidirectional"))
      (node (ref "U32") (pin "GND") (pinfunction "GND_GND") (pintype "bidirectional"))
      (node (ref "U32") (pin "GNDPAD") (pinfunction "GND_GNDPAD") (pintype "bidirectional"))
      (node (ref "U33") (pin "GND") (pinfunction "GND_GND") (pintype "bidirectional"))
      (node (ref "U33") (pin "GNDPAD") (pinfunction "GND_GNDPAD") (pintype "bidirectional"))
      (node (ref "U34") (pin "GND") (pinfunction "GND_GND") (pintype "bidirectional"))
      (node (ref "U34") (pin "GNDPAD") (pinfunction "GND_GNDPAD") (pintype "bidirectional"))
      (node (ref "U35") (pin "GND") (pinfunction "GND_GND") (pintype "bidirectional"))
      (node (ref "U35") (pin "GNDPAD") (pinfunction "GND_GNDPAD") (pintype "bidirectional"))
      (node (ref "U36") (pin "GND") (pinfunction "GND_GND") (pintype "bidirectional"))
      (node (ref "U36") (pin "GNDPAD") (pinfunction "GND_GNDPAD") (pintype "bidirectional"))
      (node (ref "U37") (pin "GND") (pinfunction "GND_GND") (pintype "bidirectional"))
      (node (ref "U37") (pin "GNDPAD") (pinfunction "GND_GNDPAD") (pintype "bidirectional"))
      (node (ref "U38") (pin "GND") (pinfunction "GND_GND") (pintype "bidirectional"))
      (node (ref "U38") (pin "GNDPAD") (pinfunction "GND_GNDPAD") (pintype "bidirectional"))
      (node (ref "U39") (pin "GND") (pinfunction "GND_GND") (pintype "bidirectional"))
      (node (ref "U39") (pin "GNDPAD") (pinfunction "GND_GNDPAD") (pintype "bidirectional"))
      (node (ref "U4") (pin "GND") (pinfunction "GND_GND") (pintype "bidirectional"))
      (node (ref "U4") (pin "GNDPAD") (pinfunction "GND_GNDPAD") (pintype "bidirectional"))
      (node (ref "U40") (pin "GND") (pinfunction "GND_GND") (pintype "bidirectional"))
      (node (ref "U40") (pin "GNDPAD") (pinfunction "GND_GNDPAD") (pintype "bidirectional"))
      (node (ref "U41") (pin "GND") (pinfunction "GND_GND") (pintype "bidirectional"))
      (node (ref "U41") (pin "GNDPAD") (pinfunction "GND_GNDPAD") (pintype "bidirectional"))
      (node (ref "U42") (pin "GND") (pinfunction "GND_GND") (pintype "bidirectional"))
      (node (ref "U42") (pin "GNDPAD") (pinfunction "GND_GNDPAD") (pintype "bidirectional"))
      (node (ref "U43") (pin "GND") (pinfunction "GND_GND") (pintype "bidirectional"))
      (node (ref "U43") (pin "GNDPAD") (pinfunction "GND_GNDPAD") (pintype "bidirectional"))
      (node (ref "U44") (pin "GND") (pinfunction "GND_GND") (pintype "bidirectional"))
      (node (ref "U44") (pin "GNDPAD") (pinfunction "GND_GNDPAD") (pintype "bidirectional"))
      (node (ref "U45") (pin "GND") (pinfunction "GND_GND") (pintype "bidirectional"))
      (node (ref "U45") (pin "GNDPAD") (pinfunction "GND_GNDPAD") (pintype "bidirectional"))
      (node (ref "U46") (pin "GND") (pinfunction "GND_GND") (pintype "bidirectional"))
      (node (ref "U46") (pin "GNDPAD") (pinfunction "GND_GNDPAD") (pintype "bidirectional"))
      (node (ref "U47") (pin "GND") (pinfunction "GND_GND") (pintype "bidirectional"))
      (node (ref "U47") (pin "GNDPAD") (pinfunction "GND_GNDPAD") (pintype "bidirectional"))
      (node (ref "U48") (pin "GND") (pinfunction "GND_GND") (pintype "bidirectional"))
      (node (ref "U48") (pin "GNDPAD") (pinfunction "GND_GNDPAD") (pintype "bidirectional"))
      (node (ref "U49") (pin "GND") (pinfunction "GND_GND") (pintype "bidirectional"))
      (node (ref "U49") (pin "GNDPAD") (pinfunction "GND_GNDPAD") (pintype "bidirectional"))
      (node (ref "U5") (pin "GND") (pinfunction "GND_GND") (pintype "bidirectional"))
      (node (ref "U5") (pin "GNDPAD") (pinfunction "GND_GNDPAD") (pintype "bidirectional"))
      (node (ref "U50") (pin "GND") (pinfunction "GND_GND") (pintype "bidirectional"))
      (node (ref "U50") (pin "GNDPAD") (pinfunction "GND_GNDPAD") (pintype "bidirectional"))
      (node (ref "U51") (pin "GND") (pinfunction "GND_GND") (pintype "bidirectional"))
      (node (ref "U51") (pin "GNDPAD") (pinfunction "GND_GNDPAD") (pintype "bidirectional"))
      (node (ref "U52") (pin "GND") (pinfunction "GND_GND") (pintype "bidirectional"))
      (node (ref "U52") (pin "GNDPAD") (pinfunction "GND_GNDPAD") (pintype "bidirectional"))
      (node (ref "U53") (pin "GND") (pinfunction "GND_GND") (pintype "bidirectional"))
      (node (ref "U53") (pin "GNDPAD") (pinfunction "GND_GNDPAD") (pintype "bidirectional"))
      (node (ref "U54") (pin "GND") (pinfunction "GND_GND") (pintype "bidirectional"))
      (node (ref "U54") (pin "GNDPAD") (pinfunction "GND_GNDPAD") (pintype "bidirectional"))
      (node (ref "U55") (pin "GND") (pinfunction "GND_GND") (pintype "bidirectional"))
      (node (ref "U55") (pin "GNDPAD") (pinfunction "GND_GNDPAD") (pintype "bidirectional"))
      (node (ref "U56") (pin "GND") (pinfunction "GND_GND") (pintype "bidirectional"))
      (node (ref "U56") (pin "GNDPAD") (pinfunction "GND_GNDPAD") (pintype "bidirectional"))
      (node (ref "U57") (pin "GND") (pinfunction "GND_GND") (pintype "bidirectional"))
      (node (ref "U57") (pin "GNDPAD") (pinfunction "GND_GNDPAD") (pintype "bidirectional"))
      (node (ref "U58") (pin "GND") (pinfunction "GND_GND") (pintype "bidirectional"))
      (node (ref "U58") (pin "GNDPAD") (pinfunction "GND_GNDPAD") (pintype "bidirectional"))
      (node (ref "U59") (pin "GND") (pinfunction "GND_GND") (pintype "bidirectional"))
      (node (ref "U59") (pin "GNDPAD") (pinfunction "GND_GNDPAD") (pintype "bidirectional"))
      (node (ref "U6") (pin "GND") (pinfunction "GND_GND") (pintype "bidirectional"))
      (node (ref "U6") (pin "GNDPAD") (pinfunction "GND_GNDPAD") (pintype "bidirectional"))
      (node (ref "U60") (pin "GND") (pinfunction "GND_GND") (pintype "bidirectional"))
      (node (ref "U60") (pin "GNDPAD") (pinfunction "GND_GNDPAD") (pintype "bidirectional"))
      (node (ref "U61") (pin "GND") (pinfunction "GND_GND") (pintype "bidirectional"))
      (node (ref "U61") (pin "GNDPAD") (pinfunction "GND_GNDPAD") (pintype "bidirectional"))
      (node (ref "U62") (pin "GND") (pinfunction "GND_GND") (pintype "bidirectional"))
      (node (ref "U62") (pin "GNDPAD") (pinfunction "GND_GNDPAD") (pintype "bidirectional"))
      (node (ref "U63") (pin "GND") (pinfunction "GND_GND") (pintype "bidirectional"))
      (node (ref "U63") (pin "GNDPAD") (pinfunction "GND_GNDPAD") (pintype "bidirectional"))
      (node (ref "U64") (pin "GND") (pinfunction "GND_GND") (pintype "bidirectional"))
      (node (ref "U64") (pin "GNDPAD") (pinfunction "GND_GNDPAD") (pintype "bidirectional"))
      (node (ref "U65") (pin "GND") (pinfunction "GND_GND") (pintype "bidirectional"))
      (node (ref "U65") (pin "GNDPAD") (pinfunction "GND_GNDPAD") (pintype "bidirectional"))
      (node (ref "U66") (pin "GND") (pinfunction "GND_GND") (pintype "bidirectional"))
      (node (ref "U66") (pin "GNDPAD") (pinfunction "GND_GNDPAD") (pintype "bidirectional"))
      (node (ref "U67") (pin "GND") (pinfunction "GND_GND") (pintype "bidirectional"))
      (node (ref "U67") (pin "GNDPAD") (pinfunction "GND_GNDPAD") (pintype "bidirectional"))
      (node (ref "U68") (pin "GND") (pinfunction "GND_GND") (pintype "bidirectional"))
      (node (ref "U68") (pin "GNDPAD") (pinfunction "GND_GNDPAD") (pintype "bidirectional"))
      (node (ref "U69") (pin "GND") (pinfunction "GND_GND") (pintype "bidirectional"))
      (node (ref "U69") (pin "GNDPAD") (pinfunction "GND_GNDPAD") (pintype "bidirectional"))
      (node (ref "U7") (pin "GND") (pinfunction "GND_GND") (pintype "bidirectional"))
      (node (ref "U7") (pin "GNDPAD") (pinfunction "GND_GNDPAD") (pintype "bidirectional"))
      (node (ref "U70") (pin "GND") (pinfunction "GND_GND") (pintype "bidirectional"))
      (node (ref "U70") (pin "GNDPAD") (pinfunction "GND_GNDPAD") (pintype "bidirectional"))
      (node (ref "U71") (pin "GND") (pinfunction "GND_GND") (pintype "bidirectional"))
      (node (ref "U71") (pin "GNDPAD") (pinfunction "GND_GNDPAD") (pintype "bidirectional"))
      (node (ref "U72") (pin "GND") (pinfunction "GND_GND") (pintype "bidirectional"))
      (node (ref "U72") (pin "GNDPAD") (pinfunction "GND_GNDPAD") (pintype "bidirectional"))
      (node (ref "U73") (pin "GND") (pinfunction "GND_GND") (pintype "bidirectional"))
      (node (ref "U73") (pin "GNDPAD") (pinfunction "GND_GNDPAD") (pintype "bidirectional"))
      (node (ref "U74") (pin "GND") (pinfunction "GND_GND") (pintype "bidirectional"))
      (node (ref "U74") (pin "GNDPAD") (pinfunction "GND_GNDPAD") (pintype "bidirectional"))
      (node (ref "U75") (pin "GND") (pinfunction "GND_GND") (pintype "bidirectional"))
      (node (ref "U75") (pin "GNDPAD") (pinfunction "GND_GNDPAD") (pintype "bidirectional"))
      (node (ref "U76") (pin "GND") (pinfunction "GND_GND") (pintype "bidirectional"))
      (node (ref "U76") (pin "GNDPAD") (pinfunction "GND_GNDPAD") (pintype "bidirectional"))
      (node (ref "U77") (pin "GND") (pinfunction "GND_GND") (pintype "bidirectional"))
      (node (ref "U77") (pin "GNDPAD") (pinfunction "GND_GNDPAD") (pintype "bidirectional"))
      (node (ref "U78") (pin "GND") (pinfunction "GND_GND") (pintype "bidirectional"))
      (node (ref "U78") (pin "GNDPAD") (pinfunction "GND_GNDPAD") (pintype "bidirectional"))
      (node (ref "U79") (pin "GND") (pinfunction "GND_GND") (pintype "bidirectional"))
      (node (ref "U79") (pin "GNDPAD") (pinfunction "GND_GNDPAD") (pintype "bidirectional"))
      (node (ref "U8") (pin "GND") (pinfunction "GND_GND") (pintype "bidirectional"))
      (node (ref "U8") (pin "GNDPAD") (pinfunction "GND_GNDPAD") (pintype "bidirectional"))
      (node (ref "U80") (pin "GND") (pinfunction "GND_GND") (pintype "bidirectional"))
      (node (ref "U80") (pin "GNDPAD") (pinfunction "GND_GNDPAD") (pintype "bidirectional"))
      (node (ref "U81") (pin "GND") (pinfunction "GND_GND") (pintype "bidirectional"))
      (node (ref "U81") (pin "GNDPAD") (pinfunction "GND_GNDPAD") (pintype "bidirectional"))
      (node (ref "U82") (pin "GND") (pinfunction "GND_GND") (pintype "bidirectional"))
      (node (ref "U82") (pin "GNDPAD") (pinfunction "GND_GNDPAD") (pintype "bidirectional"))
      (node (ref "U83") (pin "GND") (pinfunction "GND_GND") (pintype "bidirectional"))
      (node (ref "U83") (pin "GNDPAD") (pinfunction "GND_GNDPAD") (pintype "bidirectional"))
      (node (ref "U84") (pin "GND") (pinfunction "GND_GND") (pintype "bidirectional"))
      (node (ref "U84") (pin "GNDPAD") (pinfunction "GND_GNDPAD") (pintype "bidirectional"))
      (node (ref "U85") (pin "GND") (pinfunction "GND_GND") (pintype "bidirectional"))
      (node (ref "U85") (pin "GNDPAD") (pinfunction "GND_GNDPAD") (pintype "bidirectional"))
      (node (ref "U86") (pin "GND") (pinfunction "GND_GND") (pintype "bidirectional"))
      (node (ref "U86") (pin "GNDPAD") (pinfunction "GND_GNDPAD") (pintype "bidirectional"))
      (node (ref "U87") (pin "GND") (pinfunction "GND_GND") (pintype "bidirectional"))
      (node (ref "U87") (pin "GNDPAD") (pinfunction "GND_GNDPAD") (pintype "bidirectional"))
      (node (ref "U88") (pin "GND") (pinfunction "GND_GND") (pintype "bidirectional"))
      (node (ref "U88") (pin "GNDPAD") (pinfunction "GND_GNDPAD") (pintype "bidirectional"))
      (node (ref "U89") (pin "GND") (pinfunction "GND_GND") (pintype "bidirectional"))
      (node (ref "U89") (pin "GNDPAD") (pinfunction "GND_GNDPAD") (pintype "bidirectional"))
      (node (ref "U9") (pin "GND") (pinfunction "GND_GND") (pintype "bidirectional"))
      (node (ref "U9") (pin "GNDPAD") (pinfunction "GND_GNDPAD") (pintype "bidirectional"))
      (node (ref "U90") (pin "GND") (pinfunction "GND_GND") (pintype "bidirectional"))
      (node (ref "U90") (pin "GNDPAD") (pinfunction "GND_GNDPAD") (pintype "bidirectional"))
      (node (ref "U91") (pin "GND") (pinfunction "GND_GND") (pintype "bidirectional"))
      (node (ref "U91") (pin "GNDPAD") (pinfunction "GND_GNDPAD") (pintype "bidirectional"))
      (node (ref "U92") (pin "GND") (pinfunction "GND_GND") (pintype "bidirectional"))
      (node (ref "U92") (pin "GNDPAD") (pinfunction "GND_GNDPAD") (pintype "bidirectional"))
      (node (ref "U93") (pin "GND") (pinfunction "GND_GND") (pintype "bidirectional"))
      (node (ref "U93") (pin "GNDPAD") (pinfunction "GND_GNDPAD") (pintype "bidirectional"))
      (node (ref "U94") (pin "GND") (pinfunction "GND_GND") (pintype "bidirectional"))
      (node (ref "U94") (pin "GNDPAD") (pinfunction "GND_GNDPAD") (pintype "bidirectional"))
      (node (ref "U95") (pin "GND") (pinfunction "GND_GND") (pintype "bidirectional"))
      (node (ref "U95") (pin "GNDPAD") (pinfunction "GND_GNDPAD") (pintype "bidirectional"))
      (node (ref "U96") (pin "GND") (pinfunction "GND_GND") (pintype "bidirectional"))
      (node (ref "U96") (pin "GNDPAD") (pinfunction "GND_GNDPAD") (pintype "bidirectional"))
      (node (ref "U97") (pin "GND") (pinfunction "GND_GND") (pintype "bidirectional"))
      (node (ref "U97") (pin "GNDPAD") (pinfunction "GND_GNDPAD") (pintype "bidirectional"))
      (node (ref "U98") (pin "GND") (pinfunction "GND_GND") (pintype "bidirectional"))
      (node (ref "U98") (pin "GNDPAD") (pinfunction "GND_GNDPAD") (pintype "bidirectional"))
      (node (ref "U99") (pin "GND") (pinfunction "GND_GND") (pintype "bidirectional"))
      (node (ref "U99") (pin "GNDPAD") (pinfunction "GND_GNDPAD") (pintype "bidirectional"))
    )
    (net (code "10") (name "Net-(U1-CI)") (class "Default")
      (node (ref "J2") (pin "4") (pinfunction "4_4") (pintype "passive"))
      (node (ref "U1") (pin "CKI") (pinfunction "CI_CKI") (pintype "bidirectional"))
    )
    (net (code "11") (name "Net-(U1-CO)") (class "Default")
      (node (ref "U1") (pin "CKO") (pinfunction "CO_CKO") (pintype "bidirectional"))
      (node (ref "U2") (pin "CKI") (pinfunction "CI_CKI") (pintype "bidirectional"))
    )
    (net (code "12") (name "Net-(U1-DI)") (class "Default")
      (node (ref "J2") (pin "3") (pinfunction "3_3") (pintype "passive"))
      (node (ref "U1") (pin "SDI") (pinfunction "DI_SDI") (pintype "bidirectional"))
    )
    (net (code "13") (name "Net-(U1-DO)") (class "Default")
      (node (ref "U1") (pin "SDO") (pinfunction "DO_SDO") (pintype "bidirectional"))
      (node (ref "U2") (pin "SDI") (pinfunction "DI_SDI") (pintype "bidirectional"))
    )
    (net (code "14") (name "Net-(U2-CO)") (class "Default")
      (node (ref "U2") (pin "CKO") (pinfunction "CO_CKO") (pintype "bidirectional"))
      (node (ref "U3") (pin "CKI") (pinfunction "CI_CKI") (pintype "bidirectional"))
    )
    (net (code "15") (name "Net-(U2-DO)") (class "Default")
      (node (ref "U2") (pin "SDO") (pinfunction "DO_SDO") (pintype "bidirectional"))
      (node (ref "U3") (pin "SDI") (pinfunction "DI_SDI") (pintype "bidirectional"))
    )
    (net (code "16") (name "Net-(U3-CO)") (class "Default")
      (node (ref "U3") (pin "CKO") (pinfunction "CO_CKO") (pintype "bidirectional"))
      (node (ref "U4") (pin "CKI") (pinfunction "CI_CKI") (pintype "bidirectional"))
    )
    (net (code "17") (name "Net-(U3-DO)") (class "Default")
      (node (ref "U3") (pin "SDO") (pinfunction "DO_SDO") (pintype "bidirectional"))
      (node (ref "U4") (pin "SDI") (pinfunction "DI_SDI") (pintype "bidirectional"))
    )
    (net (code "18") (name "Net-(U4-CO)") (class "Default")
      (node (ref "U4") (pin "CKO") (pinfunction "CO_CKO") (pintype "bidirectional"))
      (node (ref "U5") (pin "CKI") (pinfunction "CI_CKI") (pintype "bidirectional"))
    )
    (net (code "19") (name "Net-(U4-DO)") (class "Default")
      (node (ref "U4") (pin "SDO") (pinfunction "DO_SDO") (pintype "bidirectional"))
      (node (ref "U5") (pin "SDI") (pinfunction "DI_SDI") (pintype "bidirectional"))
    )
    (net (code "20") (name "Net-(U5-CO)") (class "Default")
      (node (ref "U5") (pin "CKO") (pinfunction "CO_CKO") (pintype "bidirectional"))
      (node (ref "U6") (pin "CKI") (pinfunction "CI_CKI") (pintype "bidirectional"))
    )
    (net (code "21") (name "Net-(U5-DO)") (class "Default")
      (node (ref "U5") (pin "SDO") (pinfunction "DO_SDO") (pintype "bidirectional"))
      (node (ref "U6") (pin "SDI") (pinfunction "DI_SDI") (pintype "bidirectional"))
    )
    (net (code "22") (name "Net-(U6-CO)") (class "Default")
      (node (ref "U6") (pin "CKO") (pinfunction "CO_CKO") (pintype "bidirectional"))
      (node (ref "U7") (pin "CKI") (pinfunction "CI_CKI") (pintype "bidirectional"))
    )
    (net (code "23") (name "Net-(U6-DO)") (class "Default")
      (node (ref "U6") (pin "SDO") (pinfunction "DO_SDO") (pintype "bidirectional"))
      (node (ref "U7") (pin "SDI") (pinfunction "DI_SDI") (pintype "bidirectional"))
    )
    (net (code "24") (name "Net-(U7-CO)") (class "Default")
      (node (ref "U7") (pin "CKO") (pinfunction "CO_CKO") (pintype "bidirectional"))
      (node (ref "U8") (pin "CKI") (pinfunction "CI_CKI") (pintype "bidirectional"))
    )
    (net (code "25") (name "Net-(U7-DO)") (class "Default")
      (node (ref "U7") (pin "SDO") (pinfunction "DO_SDO") (pintype "bidirectional"))
      (node (ref "U8") (pin "SDI") (pinfunction "DI_SDI") (pintype "bidirectional"))
    )
    (net (code "26") (name "Net-(U8-CO)") (class "Default")
      (node (ref "U8") (pin "CKO") (pinfunction "CO_CKO") (pintype "bidirectional"))
      (node (ref "U9") (pin "CKI") (pinfunction "CI_CKI") (pintype "bidirectional"))
    )
    (net (code "27") (name "Net-(U8-DO)") (class "Default")
      (node (ref "U8") (pin "SDO") (pinfunction "DO_SDO") (pintype "bidirectional"))
      (node (ref "U9") (pin "SDI") (pinfunction "DI_SDI") (pintype "bidirectional"))
    )
    (net (code "28") (name "Net-(U10-CI)") (class "Default")
      (node (ref "U10") (pin "CKI") (pinfunction "CI_CKI") (pintype "bidirectional"))
      (node (ref "U9") (pin "CKO") (pinfunction "CO_CKO") (pintype "bidirectional"))
    )
    (net (code "29") (name "Net-(U10-CO)") (class "Default")
      (node (ref "U10") (pin "CKO") (pinfunction "CO_CKO") (pintype "bidirectional"))
      (node (ref "U11") (pin "CKI") (pinfunction "CI_CKI") (pintype "bidirectional"))
    )
    (net (code "30") (name "Net-(U10-DI)") (class "Default")
      (node (ref "U10") (pin "SDI") (pinfunction "DI_SDI") (pintype "bidirectional"))
      (node (ref "U9") (pin "SDO") (pinfunction "DO_SDO") (pintype "bidirectional"))
    )
    (net (code "31") (name "Net-(U10-DO)") (class "Default")
      (node (ref "U10") (pin "SDO") (pinfunction "DO_SDO") (pintype "bidirectional"))
      (node (ref "U11") (pin "SDI") (pinfunction "DI_SDI") (pintype "bidirectional"))
    )
    (net (code "32") (name "Net-(U11-CO)") (class "Default")
      (node (ref "U11") (pin "CKO") (pinfunction "CO_CKO") (pintype "bidirectional"))
      (node (ref "U12") (pin "CKI") (pinfunction "CI_CKI") (pintype "bidirectional"))
    )
    (net (code "33") (name "Net-(U11-DO)") (class "Default")
      (node (ref "U11") (pin "SDO") (pinfunction "DO_SDO") (pintype "bidirectional"))
      (node (ref "U12") (pin "SDI") (pinfunction "DI_SDI") (pintype "bidirectional"))
    )
    (net (code "34") (name "Net-(U12-CO)") (class "Default")
      (node (ref "U12") (pin "CKO") (pinfunction "CO_CKO") (pintype "bidirectional"))
      (node (ref "U13") (pin "CKI") (pinfunction "CI_CKI") (pintype "bidirectional"))
    )
    (net (code "35") (name "Net-(U12-DO)") (class "Default")
      (node (ref "U12") (pin "SDO") (pinfunction "DO_SDO") (pintype "bidirectional"))
      (node (ref "U13") (pin "SDI") (pinfunction "DI_SDI") (pintype "bidirectional"))
    )
    (net (code "36") (name "Net-(U13-CO)") (class "Default")
      (node (ref "U13") (pin "CKO") (pinfunction "CO_CKO") (pintype "bidirectional"))
      (node (ref "U14") (pin "CKI") (pinfunction "CI_CKI") (pintype "bidirectional"))
    )
    (net (code "37") (name "Net-(U13-DO)") (class "Default")
      (node (ref "U13") (pin "SDO") (pinfunction "DO_SDO") (pintype "bidirectional"))
      (node (ref "U14") (pin "SDI") (pinfunction "DI_SDI") (pintype "bidirectional"))
    )
    (net (code "38") (name "Net-(U14-CO)") (class "Default")
      (node (ref "U14") (pin "CKO") (pinfunction "CO_CKO") (pintype "bidirectional"))
      (node (ref "U15") (pin "CKI") (pinfunction "CI_CKI") (pintype "bidirectional"))
    )
    (net (code "39") (name "Net-(U14-DO)") (class "Default")
      (node (ref "U14") (pin "SDO") (pinfunction "DO_SDO") (pintype "bidirectional"))
      (node (ref "U15") (pin "SDI") (pinfunction "DI_SDI") (pintype "bidirectional"))
    )
    (net (code "40") (name "Net-(U15-CO)") (class "Default")
      (node (ref "U15") (pin "CKO") (pinfunction "CO_CKO") (pintype "bidirectional"))
      (node (ref "U16") (pin "CKI") (pinfunction "CI_CKI") (pintype "bidirectional"))
    )
    (net (code "41") (name "Net-(U15-DO)") (class "Default")
      (node (ref "U15") (pin "SDO") (pinfunction "DO_SDO") (pintype "bidirectional"))
      (node (ref "U16") (pin "SDI") (pinfunction "DI_SDI") (pintype "bidirectional"))
    )
    (net (code "42") (name "Net-(U16-CO)") (class "Default")
      (node (ref "U16") (pin "CKO") (pinfunction "CO_CKO") (pintype "bidirectional"))
      (node (ref "U17") (pin "CKI") (pinfunction "CI_CKI") (pintype "bidirectional"))
    )
    (net (code "43") (name "Net-(U16-DO)") (class "Default")
      (node (ref "U16") (pin "SDO") (pinfunction "DO_SDO") (pintype "bidirectional"))
      (node (ref "U17") (pin "SDI") (pinfunction "DI_SDI") (pintype "bidirectional"))
    )
    (net (code "44") (name "Net-(U17-CO)") (class "Default")
      (node (ref "U17") (pin "CKO") (pinfunction "CO_CKO") (pintype "bidirectional"))
      (node (ref "U18") (pin "CKI") (pinfunction "CI_CKI") (pintype "bidirectional"))
    )
    (net (code "45") (name "Net-(U17-DO)") (class "Default")
      (node (ref "U17") (pin "SDO") (pinfunction "DO_SDO") (pintype "bidirectional"))
      (node (ref "U18") (pin "SDI") (pinfunction "DI_SDI") (pintype "bidirectional"))
    )
    (net (code "46") (name "Net-(U18-CO)") (class "Default")
      (node (ref "U18") (pin "CKO") (pinfunction "CO_CKO") (pintype "bidirectional"))
      (node (ref "U19") (pin "CKI") (pinfunction "CI_CKI") (pintype "bidirectional"))
    )
    (net (code "47") (name "Net-(U18-DO)") (class "Default")
      (node (ref "U18") (pin "SDO") (pinfunction "DO_SDO") (pintype "bidirectional"))
      (node (ref "U19") (pin "SDI") (pinfunction "DI_SDI") (pintype "bidirectional"))
    )
    (net (code "48") (name "Net-(U19-CO)") (class "Default")
      (node (ref "U19") (pin "CKO") (pinfunction "CO_CKO") (pintype "bidirectional"))
      (node (ref "U20") (pin "CKI") (pinfunction "CI_CKI") (pintype "bidirectional"))
    )
    (net (code "49") (name "Net-(U19-DO)") (class "Default")
      (node (ref "U19") (pin "SDO") (pinfunction "DO_SDO") (pintype "bidirectional"))
      (node (ref "U20") (pin "SDI") (pinfunction "DI_SDI") (pintype "bidirectional"))
    )
    (net (code "50") (name "Net-(U20-CO)") (class "Default")
      (node (ref "U20") (pin "CKO") (pinfunction "CO_CKO") (pintype "bidirectional"))
      (node (ref "U21") (pin "CKI") (pinfunction "CI_CKI") (pintype "bidirectional"))
    )
    (net (code "51") (name "Net-(U20-DO)") (class "Default")
      (node (ref "U20") (pin "SDO") (pinfunction "DO_SDO") (pintype "bidirectional"))
      (node (ref "U21") (pin "SDI") (pinfunction "DI_SDI") (pintype "bidirectional"))
    )
    (net (code "52") (name "Net-(U21-CO)") (class "Default")
      (node (ref "U21") (pin "CKO") (pinfunction "CO_CKO") (pintype "bidirectional"))
      (node (ref "U22") (pin "CKI") (pinfunction "CI_CKI") (pintype "bidirectional"))
    )
    (net (code "53") (name "Net-(U21-DO)") (class "Default")
      (node (ref "U21") (pin "SDO") (pinfunction "DO_SDO") (pintype "bidirectional"))
      (node (ref "U22") (pin "SDI") (pinfunction "DI_SDI") (pintype "bidirectional"))
    )
    (net (code "54") (name "Net-(U22-CO)") (class "Default")
      (node (ref "U22") (pin "CKO") (pinfunction "CO_CKO") (pintype "bidirectional"))
      (node (ref "U23") (pin "CKI") (pinfunction "CI_CKI") (pintype "bidirectional"))
    )
    (net (code "55") (name "Net-(U22-DO)") (class "Default")
      (node (ref "U22") (pin "SDO") (pinfunction "DO_SDO") (pintype "bidirectional"))
      (node (ref "U23") (pin "SDI") (pinfunction "DI_SDI") (pintype "bidirectional"))
    )
    (net (code "56") (name "Net-(U23-CO)") (class "Default")
      (node (ref "U23") (pin "CKO") (pinfunction "CO_CKO") (pintype "bidirectional"))
      (node (ref "U24") (pin "CKI") (pinfunction "CI_CKI") (pintype "bidirectional"))
    )
    (net (code "57") (name "Net-(U23-DO)") (class "Default")
      (node (ref "U23") (pin "SDO") (pinfunction "DO_SDO") (pintype "bidirectional"))
      (node (ref "U24") (pin "SDI") (pinfunction "DI_SDI") (pintype "bidirectional"))
    )
    (net (code "58") (name "Net-(U24-CO)") (class "Default")
      (node (ref "U24") (pin "CKO") (pinfunction "CO_CKO") (pintype "bidirectional"))
      (node (ref "U25") (pin "CKI") (pinfunction "CI_CKI") (pintype "bidirectional"))
    )
    (net (code "59") (name "Net-(U24-DO)") (class "Default")
      (node (ref "U24") (pin "SDO") (pinfunction "DO_SDO") (pintype "bidirectional"))
      (node (ref "U25") (pin "SDI") (pinfunction "DI_SDI") (pintype "bidirectional"))
    )
    (net (code "60") (name "Net-(U25-CO)") (class "Default")
      (node (ref "U25") (pin "CKO") (pinfunction "CO_CKO") (pintype "bidirectional"))
      (node (ref "U26") (pin "CKI") (pinfunction "CI_CKI") (pintype "bidirectional"))
    )
    (net (code "61") (name "Net-(U25-DO)") (class "Default")
      (node (ref "U25") (pin "SDO") (pinfunction "DO_SDO") (pintype "bidirectional"))
      (node (ref "U26") (pin "SDI") (pinfunction "DI_SDI") (pintype "bidirectional"))
    )
    (net (code "62") (name "Net-(U26-CO)") (class "Default")
      (node (ref "U26") (pin "CKO") (pinfunction "CO_CKO") (pintype "bidirectional"))
      (node (ref "U27") (pin "CKI") (pinfunction "CI_CKI") (pintype "bidirectional"))
    )
    (net (code "63") (name "Net-(U26-DO)") (class "Default")
      (node (ref "U26") (pin "SDO") (pinfunction "DO_SDO") (pintype "bidirectional"))
      (node (ref "U27") (pin "SDI") (pinfunction "DI_SDI") (pintype "bidirectional"))
    )
    (net (code "64") (name "Net-(U27-CO)") (class "Default")
      (node (ref "U27") (pin "CKO") (pinfunction "CO_CKO") (pintype "bidirectional"))
      (node (ref "U28") (pin "CKI") (pinfunction "CI_CKI") (pintype "bidirectional"))
    )
    (net (code "65") (name "Net-(U27-DO)") (class "Default")
      (node (ref "U27") (pin "SDO") (pinfunction "DO_SDO") (pintype "bidirectional"))
      (node (ref "U28") (pin "SDI") (pinfunction "DI_SDI") (pintype "bidirectional"))
    )
    (net (code "66") (name "Net-(U29-CO)") (class "Default")
      (node (ref "U29") (pin "CKO") (pinfunction "CO_CKO") (pintype "bidirectional"))
      (node (ref "U30") (pin "CKI") (pinfunction "CI_CKI") (pintype "bidirectional"))
    )
    (net (code "67") (name "Net-(U29-DO)") (class "Default")
      (node (ref "U29") (pin "SDO") (pinfunction "DO_SDO") (pintype "bidirectional"))
      (node (ref "U30") (pin "SDI") (pinfunction "DI_SDI") (pintype "bidirectional"))
    )
    (net (code "68") (name "Net-(U30-CO)") (class "Default")
      (node (ref "U30") (pin "CKO") (pinfunction "CO_CKO") (pintype "bidirectional"))
      (node (ref "U31") (pin "CKI") (pinfunction "CI_CKI") (pintype "bidirectional"))
    )
    (net (code "69") (name "Net-(U30-DO)") (class "Default")
      (node (ref "U30") (pin "SDO") (pinfunction "DO_SDO") (pintype "bidirectional"))
      (node (ref "U31") (pin "SDI") (pinfunction "DI_SDI") (pintype "bidirectional"))
    )
    (net (code "70") (name "Net-(U31-CO)") (class "Default")
      (node (ref "U31") (pin "CKO") (pinfunction "CO_CKO") (pintype "bidirectional"))
      (node (ref "U32") (pin "CKI") (pinfunction "CI_CKI") (pintype "bidirectional"))
    )
    (net (code "71") (name "Net-(U31-DO)") (class "Default")
      (node (ref "U31") (pin "SDO") (pinfunction "DO_SDO") (pintype "bidirectional"))
      (node (ref "U32") (pin "SDI") (pinfunction "DI_SDI") (pintype "bidirectional"))
    )
    (net (code "72") (name "Net-(U32-CO)") (class "Default")
      (node (ref "U32") (pin "CKO") (pinfunction "CO_CKO") (pintype "bidirectional"))
      (node (ref "U33") (pin "CKI") (pinfunction "CI_CKI") (pintype "bidirectional"))
    )
    (net (code "73") (name "Net-(U32-DO)") (class "Default")
      (node (ref "U32") (pin "SDO") (pinfunction "DO_SDO") (pintype "bidirectional"))
      (node (ref "U33") (pin "SDI") (pinfunction "DI_SDI") (pintype "bidirectional"))
    )
    (net (code "74") (name "Net-(U33-CO)") (class "Default")
      (node (ref "U33") (pin "CKO") (pinfunction "CO_CKO") (pintype "bidirectional"))
      (node (ref "U34") (pin "CKI") (pinfunction "CI_CKI") (pintype "bidirectional"))
    )
    (net (code "75") (name "Net-(U33-DO)") (class "Default")
      (node (ref "U33") (pin "SDO") (pinfunction "DO_SDO") (pintype "bidirectional"))
      (node (ref "U34") (pin "SDI") (pinfunction "DI_SDI") (pintype "bidirectional"))
    )
    (net (code "76") (name "Net-(U34-CO)") (class "Default")
      (node (ref "U34") (pin "CKO") (pinfunction "CO_CKO") (pintype "bidirectional"))
      (node (ref "U35") (pin "CKI") (pinfunction "CI_CKI") (pintype "bidirectional"))
    )
    (net (code "77") (name "Net-(U34-DO)") (class "Default")
      (node (ref "U34") (pin "SDO") (pinfunction "DO_SDO") (pintype "bidirectional"))
      (node (ref "U35") (pin "SDI") (pinfunction "DI_SDI") (pintype "bidirectional"))
    )
    (net (code "78") (name "Net-(U35-CO)") (class "Default")
      (node (ref "U35") (pin "CKO") (pinfunction "CO_CKO") (pintype "bidirectional"))
      (node (ref "U36") (pin "CKI") (pinfunction "CI_CKI") (pintype "bidirectional"))
    )
    (net (code "79") (name "Net-(U35-DO)") (class "Default")
      (node (ref "U35") (pin "SDO") (pinfunction "DO_SDO") (pintype "bidirectional"))
      (node (ref "U36") (pin "SDI") (pinfunction "DI_SDI") (pintype "bidirectional"))
    )
    (net (code "80") (name "Net-(U36-CO)") (class "Default")
      (node (ref "U36") (pin "CKO") (pinfunction "CO_CKO") (pintype "bidirectional"))
      (node (ref "U37") (pin "CKI") (pinfunction "CI_CKI") (pintype "bidirectional"))
    )
    (net (code "81") (name "Net-(U36-DO)") (class "Default")
      (node (ref "U36") (pin "SDO") (pinfunction "DO_SDO") (pintype "bidirectional"))
      (node (ref "U37") (pin "SDI") (pinfunction "DI_SDI") (pintype "bidirectional"))
    )
    (net (code "82") (name "Net-(U37-CO)") (class "Default")
      (node (ref "U37") (pin "CKO") (pinfunction "CO_CKO") (pintype "bidirectional"))
      (node (ref "U38") (pin "CKI") (pinfunction "CI_CKI") (pintype "bidirectional"))
    )
    (net (code "83") (name "Net-(U37-DO)") (class "Default")
      (node (ref "U37") (pin "SDO") (pinfunction "DO_SDO") (pintype "bidirectional"))
      (node (ref "U38") (pin "SDI") (pinfunction "DI_SDI") (pintype "bidirectional"))
    )
    (net (code "84") (name "Net-(U38-CO)") (class "Default")
      (node (ref "U38") (pin "CKO") (pinfunction "CO_CKO") (pintype "bidirectional"))
      (node (ref "U39") (pin "CKI") (pinfunction "CI_CKI") (pintype "bidirectional"))
    )
    (net (code "85") (name "Net-(U38-DO)") (class "Default")
      (node (ref "U38") (pin "SDO") (pinfunction "DO_SDO") (pintype "bidirectional"))
      (node (ref "U39") (pin "SDI") (pinfunction "DI_SDI") (pintype "bidirectional"))
    )
    (net (code "86") (name "Net-(U39-CO)") (class "Default")
      (node (ref "U39") (pin "CKO") (pinfunction "CO_CKO") (pintype "bidirectional"))
      (node (ref "U40") (pin "CKI") (pinfunction "CI_CKI") (pintype "bidirectional"))
    )
    (net (code "87") (name "Net-(U39-DO)") (class "Default")
      (node (ref "U39") (pin "SDO") (pinfunction "DO_SDO") (pintype "bidirectional"))
      (node (ref "U40") (pin "SDI") (pinfunction "DI_SDI") (pintype "bidirectional"))
    )
    (net (code "88") (name "Net-(U40-CO)") (class "Default")
      (node (ref "U40") (pin "CKO") (pinfunction "CO_CKO") (pintype "bidirectional"))
      (node (ref "U41") (pin "CKI") (pinfunction "CI_CKI") (pintype "bidirectional"))
    )
    (net (code "89") (name "Net-(U40-DO)") (class "Default")
      (node (ref "U40") (pin "SDO") (pinfunction "DO_SDO") (pintype "bidirectional"))
      (node (ref "U41") (pin "SDI") (pinfunction "DI_SDI") (pintype "bidirectional"))
    )
    (net (code "90") (name "Net-(U41-CO)") (class "Default")
      (node (ref "U41") (pin "CKO") (pinfunction "CO_CKO") (pintype "bidirectional"))
      (node (ref "U42") (pin "CKI") (pinfunction "CI_CKI") (pintype "bidirectional"))
    )
    (net (code "91") (name "Net-(U41-DO)") (class "Default")
      (node (ref "U41") (pin "SDO") (pinfunction "DO_SDO") (pintype "bidirectional"))
      (node (ref "U42") (pin "SDI") (pinfunction "DI_SDI") (pintype "bidirectional"))
    )
    (net (code "92") (name "Net-(U42-CO)") (class "Default")
      (node (ref "U42") (pin "CKO") (pinfunction "CO_CKO") (pintype "bidirectional"))
      (node (ref "U43") (pin "CKI") (pinfunction "CI_CKI") (pintype "bidirectional"))
    )
    (net (code "93") (name "Net-(U42-DO)") (class "Default")
      (node (ref "U42") (pin "SDO") (pinfunction "DO_SDO") (pintype "bidirectional"))
      (node (ref "U43") (pin "SDI") (pinfunction "DI_SDI") (pintype "bidirectional"))
    )
    (net (code "94") (name "Net-(U43-CO)") (class "Default")
      (node (ref "U43") (pin "CKO") (pinfunction "CO_CKO") (pintype "bidirectional"))
      (node (ref "U44") (pin "CKI") (pinfunction "CI_CKI") (pintype "bidirectional"))
    )
    (net (code "95") (name "Net-(U43-DO)") (class "Default")
      (node (ref "U43") (pin "SDO") (pinfunction "DO_SDO") (pintype "bidirectional"))
      (node (ref "U44") (pin "SDI") (pinfunction "DI_SDI") (pintype "bidirectional"))
    )
    (net (code "96") (name "Net-(U44-CO)") (class "Default")
      (node (ref "U44") (pin "CKO") (pinfunction "CO_CKO") (pintype "bidirectional"))
      (node (ref "U45") (pin "CKI") (pinfunction "CI_CKI") (pintype "bidirectional"))
    )
    (net (code "97") (name "Net-(U44-DO)") (class "Default")
      (node (ref "U44") (pin "SDO") (pinfunction "DO_SDO") (pintype "bidirectional"))
      (node (ref "U45") (pin "SDI") (pinfunction "DI_SDI") (pintype "bidirectional"))
    )
    (net (code "98") (name "Net-(U45-CO)") (class "Default")
      (node (ref "U45") (pin "CKO") (pinfunction "CO_CKO") (pintype "bidirectional"))
      (node (ref "U46") (pin "CKI") (pinfunction "CI_CKI") (pintype "bidirectional"))
    )
    (net (code "99") (name "Net-(U45-DO)") (class "Default")
      (node (ref "U45") (pin "SDO") (pinfunction "DO_SDO") (pintype "bidirectional"))
      (node (ref "U46") (pin "SDI") (pinfunction "DI_SDI") (pintype "bidirectional"))
    )
    (net (code "100") (name "Net-(U46-CO)") (class "Default")
      (node (ref "U46") (pin "CKO") (pinfunction "CO_CKO") (pintype "bidirectional"))
      (node (ref "U47") (pin "CKI") (pinfunction "CI_CKI") (pintype "bidirectional"))
    )
    (net (code "101") (name "Net-(U46-DO)") (class "Default")
      (node (ref "U46") (pin "SDO") (pinfunction "DO_SDO") (pintype "bidirectional"))
      (node (ref "U47") (pin "SDI") (pinfunction "DI_SDI") (pintype "bidirectional"))
    )
    (net (code "102") (name "Net-(U47-CO)") (class "Default")
      (node (ref "U47") (pin "CKO") (pinfunction "CO_CKO") (pintype "bidirectional"))
      (node (ref "U48") (pin "CKI") (pinfunction "CI_CKI") (pintype "bidirectional"))
    )
    (net (code "103") (name "Net-(U47-DO)") (class "Default")
      (node (ref "U47") (pin "SDO") (pinfunction "DO_SDO") (pintype "bidirectional"))
      (node (ref "U48") (pin "SDI") (pinfunction "DI_SDI") (pintype "bidirectional"))
    )
    (net (code "104") (name "Net-(U48-CO)") (class "Default")
      (node (ref "U48") (pin "CKO") (pinfunction "CO_CKO") (pintype "bidirectional"))
      (node (ref "U49") (pin "CKI") (pinfunction "CI_CKI") (pintype "bidirectional"))
    )
    (net (code "105") (name "Net-(U48-DO)") (class "Default")
      (node (ref "U48") (pin "SDO") (pinfunction "DO_SDO") (pintype "bidirectional"))
      (node (ref "U49") (pin "SDI") (pinfunction "DI_SDI") (pintype "bidirectional"))
    )
    (net (code "106") (name "Net-(U49-CO)") (class "Default")
      (node (ref "U49") (pin "CKO") (pinfunction "CO_CKO") (pintype "bidirectional"))
      (node (ref "U50") (pin "CKI") (pinfunction "CI_CKI") (pintype "bidirectional"))
    )
    (net (code "107") (name "Net-(U49-DO)") (class "Default")
      (node (ref "U49") (pin "SDO") (pinfunction "DO_SDO") (pintype "bidirectional"))
      (node (ref "U50") (pin "SDI") (pinfunction "DI_SDI") (pintype "bidirectional"))
    )
    (net (code "108") (name "Net-(U50-CO)") (class "Default")
      (node (ref "U50") (pin "CKO") (pinfunction "CO_CKO") (pintype "bidirectional"))
      (node (ref "U51") (pin "CKI") (pinfunction "CI_CKI") (pintype "bidirectional"))
    )
    (net (code "109") (name "Net-(U50-DO)") (class "Default")
      (node (ref "U50") (pin "SDO") (pinfunction "DO_SDO") (pintype "bidirectional"))
      (node (ref "U51") (pin "SDI") (pinfunction "DI_SDI") (pintype "bidirectional"))
    )
    (net (code "110") (name "Net-(U51-CO)") (class "Default")
      (node (ref "U51") (pin "CKO") (pinfunction "CO_CKO") (pintype "bidirectional"))
      (node (ref "U52") (pin "CKI") (pinfunction "CI_CKI") (pintype "bidirectional"))
    )
    (net (code "111") (name "Net-(U51-DO)") (class "Default")
      (node (ref "U51") (pin "SDO") (pinfunction "DO_SDO") (pintype "bidirectional"))
      (node (ref "U52") (pin "SDI") (pinfunction "DI_SDI") (pintype "bidirectional"))
    )
    (net (code "112") (name "Net-(U52-CO)") (class "Default")
      (node (ref "U52") (pin "CKO") (pinfunction "CO_CKO") (pintype "bidirectional"))
      (node (ref "U53") (pin "CKI") (pinfunction "CI_CKI") (pintype "bidirectional"))
    )
    (net (code "113") (name "Net-(U52-DO)") (class "Default")
      (node (ref "U52") (pin "SDO") (pinfunction "DO_SDO") (pintype "bidirectional"))
      (node (ref "U53") (pin "SDI") (pinfunction "DI_SDI") (pintype "bidirectional"))
    )
    (net (code "114") (name "Net-(U53-CO)") (class "Default")
      (node (ref "U53") (pin "CKO") (pinfunction "CO_CKO") (pintype "bidirectional"))
      (node (ref "U54") (pin "CKI") (pinfunction "CI_CKI") (pintype "bidirectional"))
    )
    (net (code "115") (name "Net-(U53-DO)") (class "Default")
      (node (ref "U53") (pin "SDO") (pinfunction "DO_SDO") (pintype "bidirectional"))
      (node (ref "U54") (pin "SDI") (pinfunction "DI_SDI") (pintype "bidirectional"))
    )
    (net (code "116") (name "Net-(U54-CO)") (class "Default")
      (node (ref "U54") (pin "CKO") (pinfunction "CO_CKO") (pintype "bidirectional"))
      (node (ref "U55") (pin "CKI") (pinfunction "CI_CKI") (pintype "bidirectional"))
    )
    (net (code "117") (name "Net-(U54-DO)") (class "Default")
      (node (ref "U54") (pin "SDO") (pinfunction "DO_SDO") (pintype "bidirectional"))
      (node (ref "U55") (pin "SDI") (pinfunction "DI_SDI") (pintype "bidirectional"))
    )
    (net (code "118") (name "Net-(U55-CO)") (class "Default")
      (node (ref "U55") (pin "CKO") (pinfunction "CO_CKO") (pintype "bidirectional"))
      (node (ref "U56") (pin "CKI") (pinfunction "CI_CKI") (pintype "bidirectional"))
    )
    (net (code "119") (name "Net-(U55-DO)") (class "Default")
      (node (ref "U55") (pin "SDO") (pinfunction "DO_SDO") (pintype "bidirectional"))
      (node (ref "U56") (pin "SDI") (pinfunction "DI_SDI") (pintype "bidirectional"))
    )
    (net (code "120") (name "Net-(U57-CO)") (class "Default")
      (node (ref "U57") (pin "CKO") (pinfunction "CO_CKO") (pintype "bidirectional"))
      (node (ref "U58") (pin "CKI") (pinfunction "CI_CKI") (pintype "bidirectional"))
    )
    (net (code "121") (name "Net-(U57-DO)") (class "Default")
      (node (ref "U57") (pin "SDO") (pinfunction "DO_SDO") (pintype "bidirectional"))
      (node (ref "U58") (pin "SDI") (pinfunction "DI_SDI") (pintype "bidirectional"))
    )
    (net (code "122") (name "Net-(U58-CO)") (class "Default")
      (node (ref "U58") (pin "CKO") (pinfunction "CO_CKO") (pintype "bidirectional"))
      (node (ref "U59") (pin "CKI") (pinfunction "CI_CKI") (pintype "bidirectional"))
    )
    (net (code "123") (name "Net-(U58-DO)") (class "Default")
      (node (ref "U58") (pin "SDO") (pinfunction "DO_SDO") (pintype "bidirectional"))
      (node (ref "U59") (pin "SDI") (pinfunction "DI_SDI") (pintype "bidirectional"))
    )
    (net (code "124") (name "Net-(U59-CO)") (class "Default")
      (node (ref "U59") (pin "CKO") (pinfunction "CO_CKO") (pintype "bidirectional"))
      (node (ref "U60") (pin "CKI") (pinfunction "CI_CKI") (pintype "bidirectional"))
    )
    (net (code "125") (name "Net-(U59-DO)") (class "Default")
      (node (ref "U59") (pin "SDO") (pinfunction "DO_SDO") (pintype "bidirectional"))
      (node (ref "U60") (pin "SDI") (pinfunction "DI_SDI") (pintype "bidirectional"))
    )
    (net (code "126") (name "Net-(U60-CO)") (class "Default")
      (node (ref "U60") (pin "CKO") (pinfunction "CO_CKO") (pintype "bidirectional"))
      (node (ref "U61") (pin "CKI") (pinfunction "CI_CKI") (pintype "bidirectional"))
    )
    (net (code "127") (name "Net-(U60-DO)") (class "Default")
      (node (ref "U60") (pin "SDO") (pinfunction "DO_SDO") (pintype "bidirectional"))
      (node (ref "U61") (pin "SDI") (pinfunction "DI_SDI") (pintype "bidirectional"))
    )
    (net (code "128") (name "Net-(U61-CO)") (class "Default")
      (node (ref "U61") (pin "CKO") (pinfunction "CO_CKO") (pintype "bidirectional"))
      (node (ref "U62") (pin "CKI") (pinfunction "CI_CKI") (pintype "bidirectional"))
    )
    (net (code "129") (name "Net-(U61-DO)") (class "Default")
      (node (ref "U61") (pin "SDO") (pinfunction "DO_SDO") (pintype "bidirectional"))
      (node (ref "U62") (pin "SDI") (pinfunction "DI_SDI") (pintype "bidirectional"))
    )
    (net (code "130") (name "Net-(U62-CO)") (class "Default")
      (node (ref "U62") (pin "CKO") (pinfunction "CO_CKO") (pintype "bidirectional"))
      (node (ref "U63") (pin "CKI") (pinfunction "CI_CKI") (pintype "bidirectional"))
    )
    (net (code "131") (name "Net-(U62-DO)") (class "Default")
      (node (ref "U62") (pin "SDO") (pinfunction "DO_SDO") (pintype "bidirectional"))
      (node (ref "U63") (pin "SDI") (pinfunction "DI_SDI") (pintype "bidirectional"))
    )
    (net (code "132") (name "Net-(U63-CO)") (class "Default")
      (node (ref "U63") (pin "CKO") (pinfunction "CO_CKO") (pintype "bidirectional"))
      (node (ref "U64") (pin "CKI") (pinfunction "CI_CKI") (pintype "bidirectional"))
    )
    (net (code "133") (name "Net-(U63-DO)") (class "Default")
      (node (ref "U63") (pin "SDO") (pinfunction "DO_SDO") (pintype "bidirectional"))
      (node (ref "U64") (pin "SDI") (pinfunction "DI_SDI") (pintype "bidirectional"))
    )
    (net (code "134") (name "Net-(U64-CO)") (class "Default")
      (node (ref "U64") (pin "CKO") (pinfunction "CO_CKO") (pintype "bidirectional"))
      (node (ref "U65") (pin "CKI") (pinfunction "CI_CKI") (pintype "bidirectional"))
    )
    (net (code "135") (name "Net-(U64-DO)") (class "Default")
      (node (ref "U64") (pin "SDO") (pinfunction "DO_SDO") (pintype "bidirectional"))
      (node (ref "U65") (pin "SDI") (pinfunction "DI_SDI") (pintype "bidirectional"))
    )
    (net (code "136") (name "Net-(U65-CO)") (class "Default")
      (node (ref "U65") (pin "CKO") (pinfunction "CO_CKO") (pintype "bidirectional"))
      (node (ref "U66") (pin "CKI") (pinfunction "CI_CKI") (pintype "bidirectional"))
    )
    (net (code "137") (name "Net-(U65-DO)") (class "Default")
      (node (ref "U65") (pin "SDO") (pinfunction "DO_SDO") (pintype "bidirectional"))
      (node (ref "U66") (pin "SDI") (pinfunction "DI_SDI") (pintype "bidirectional"))
    )
    (net (code "138") (name "Net-(U66-CO)") (class "Default")
      (node (ref "U66") (pin "CKO") (pinfunction "CO_CKO") (pintype "bidirectional"))
      (node (ref "U67") (pin "CKI") (pinfunction "CI_CKI") (pintype "bidirectional"))
    )
    (net (code "139") (name "Net-(U66-DO)") (class "Default")
      (node (ref "U66") (pin "SDO") (pinfunction "DO_SDO") (pintype "bidirectional"))
      (node (ref "U67") (pin "SDI") (pinfunction "DI_SDI") (pintype "bidirectional"))
    )
    (net (code "140") (name "Net-(U67-CO)") (class "Default")
      (node (ref "U67") (pin "CKO") (pinfunction "CO_CKO") (pintype "bidirectional"))
      (node (ref "U68") (pin "CKI") (pinfunction "CI_CKI") (pintype "bidirectional"))
    )
    (net (code "141") (name "Net-(U67-DO)") (class "Default")
      (node (ref "U67") (pin "SDO") (pinfunction "DO_SDO") (pintype "bidirectional"))
      (node (ref "U68") (pin "SDI") (pinfunction "DI_SDI") (pintype "bidirectional"))
    )
    (net (code "142") (name "Net-(U68-CO)") (class "Default")
      (node (ref "U68") (pin "CKO") (pinfunction "CO_CKO") (pintype "bidirectional"))
      (node (ref "U69") (pin "CKI") (pinfunction "CI_CKI") (pintype "bidirectional"))
    )
    (net (code "143") (name "Net-(U68-DO)") (class "Default")
      (node (ref "U68") (pin "SDO") (pinfunction "DO_SDO") (pintype "bidirectional"))
      (node (ref "U69") (pin "SDI") (pinfunction "DI_SDI") (pintype "bidirectional"))
    )
    (net (code "144") (name "Net-(U69-CO)") (class "Default")
      (node (ref "U69") (pin "CKO") (pinfunction "CO_CKO") (pintype "bidirectional"))
      (node (ref "U70") (pin "CKI") (pinfunction "CI_CKI") (pintype "bidirectional"))
    )
    (net (code "145") (name "Net-(U69-DO)") (class "Default")
      (node (ref "U69") (pin "SDO") (pinfunction "DO_SDO") (pintype "bidirectional"))
      (node (ref "U70") (pin "SDI") (pinfunction "DI_SDI") (pintype "bidirectional"))
    )
    (net (code "146") (name "Net-(U70-CO)") (class "Default")
      (node (ref "U70") (pin "CKO") (pinfunction "CO_CKO") (pintype "bidirectional"))
      (node (ref "U71") (pin "CKI") (pinfunction "CI_CKI") (pintype "bidirectional"))
    )
    (net (code "147") (name "Net-(U70-DO)") (class "Default")
      (node (ref "U70") (pin "SDO") (pinfunction "DO_SDO") (pintype "bidirectional"))
      (node (ref "U71") (pin "SDI") (pinfunction "DI_SDI") (pintype "bidirectional"))
    )
    (net (code "148") (name "Net-(U71-CO)") (class "Default")
      (node (ref "U71") (pin "CKO") (pinfunction "CO_CKO") (pintype "bidirectional"))
      (node (ref "U72") (pin "CKI") (pinfunction "CI_CKI") (pintype "bidirectional"))
    )
    (net (code "149") (name "Net-(U71-DO)") (class "Default")
      (node (ref "U71") (pin "SDO") (pinfunction "DO_SDO") (pintype "bidirectional"))
      (node (ref "U72") (pin "SDI") (pinfunction "DI_SDI") (pintype "bidirectional"))
    )
    (net (code "150") (name "Net-(U72-CO)") (class "Default")
      (node (ref "U72") (pin "CKO") (pinfunction "CO_CKO") (pintype "bidirectional"))
      (node (ref "U73") (pin "CKI") (pinfunction "CI_CKI") (pintype "bidirectional"))
    )
    (net (code "151") (name "Net-(U72-DO)") (class "Default")
      (node (ref "U72") (pin "SDO") (pinfunction "DO_SDO") (pintype "bidirectional"))
      (node (ref "U73") (pin "SDI") (pinfunction "DI_SDI") (pintype "bidirectional"))
    )
    (net (code "152") (name "Net-(U73-CO)") (class "Default")
      (node (ref "U73") (pin "CKO") (pinfunction "CO_CKO") (pintype "bidirectional"))
      (node (ref "U74") (pin "CKI") (pinfunction "CI_CKI") (pintype "bidirectional"))
    )
    (net (code "153") (name "Net-(U73-DO)") (class "Default")
      (node (ref "U73") (pin "SDO") (pinfunction "DO_SDO") (pintype "bidirectional"))
      (node (ref "U74") (pin "SDI") (pinfunction "DI_SDI") (pintype "bidirectional"))
    )
    (net (code "154") (name "Net-(U74-CO)") (class "Default")
      (node (ref "U74") (pin "CKO") (pinfunction "CO_CKO") (pintype "bidirectional"))
      (node (ref "U75") (pin "CKI") (pinfunction "CI_CKI") (pintype "bidirectional"))
    )
    (net (code "155") (name "Net-(U74-DO)") (class "Default")
      (node (ref "U74") (pin "SDO") (pinfunction "DO_SDO") (pintype "bidirectional"))
      (node (ref "U75") (pin "SDI") (pinfunction "DI_SDI") (pintype "bidirectional"))
    )
    (net (code "156") (name "Net-(U75-CO)") (class "Default")
      (node (ref "U75") (pin "CKO") (pinfunction "CO_CKO") (pintype "bidirectional"))
      (node (ref "U76") (pin "CKI") (pinfunction "CI_CKI") (pintype "bidirectional"))
    )
    (net (code "157") (name "Net-(U75-DO)") (class "Default")
      (node (ref "U75") (pin "SDO") (pinfunction "DO_SDO") (pintype "bidirectional"))
      (node (ref "U76") (pin "SDI") (pinfunction "DI_SDI") (pintype "bidirectional"))
    )
    (net (code "158") (name "Net-(U76-CO)") (class "Default")
      (node (ref "U76") (pin "CKO") (pinfunction "CO_CKO") (pintype "bidirectional"))
      (node (ref "U77") (pin "CKI") (pinfunction "CI_CKI") (pintype "bidirectional"))
    )
    (net (code "159") (name "Net-(U76-DO)") (class "Default")
      (node (ref "U76") (pin "SDO") (pinfunction "DO_SDO") (pintype "bidirectional"))
      (node (ref "U77") (pin "SDI") (pinfunction "DI_SDI") (pintype "bidirectional"))
    )
    (net (code "160") (name "Net-(U77-CO)") (class "Default")
      (node (ref "U77") (pin "CKO") (pinfunction "CO_CKO") (pintype "bidirectional"))
      (node (ref "U78") (pin "CKI") (pinfunction "CI_CKI") (pintype "bidirectional"))
    )
    (net (code "161") (name "Net-(U77-DO)") (class "Default")
      (node (ref "U77") (pin "SDO") (pinfunction "DO_SDO") (pintype "bidirectional"))
      (node (ref "U78") (pin "SDI") (pinfunction "DI_SDI") (pintype "bidirectional"))
    )
    (net (code "162") (name "Net-(U78-CO)") (class "Default")
      (node (ref "U78") (pin "CKO") (pinfunction "CO_CKO") (pintype "bidirectional"))
      (node (ref "U79") (pin "CKI") (pinfunction "CI_CKI") (pintype "bidirectional"))
    )
    (net (code "163") (name "Net-(U78-DO)") (class "Default")
      (node (ref "U78") (pin "SDO") (pinfunction "DO_SDO") (pintype "bidirectional"))
      (node (ref "U79") (pin "SDI") (pinfunction "DI_SDI") (pintype "bidirectional"))
    )
    (net (code "164") (name "Net-(U79-CO)") (class "Default")
      (node (ref "U79") (pin "CKO") (pinfunction "CO_CKO") (pintype "bidirectional"))
      (node (ref "U80") (pin "CKI") (pinfunction "CI_CKI") (pintype "bidirectional"))
    )
    (net (code "165") (name "Net-(U79-DO)") (class "Default")
      (node (ref "U79") (pin "SDO") (pinfunction "DO_SDO") (pintype "bidirectional"))
      (node (ref "U80") (pin "SDI") (pinfunction "DI_SDI") (pintype "bidirectional"))
    )
    (net (code "166") (name "Net-(U80-CO)") (class "Default")
      (node (ref "U80") (pin "CKO") (pinfunction "CO_CKO") (pintype "bidirectional"))
      (node (ref "U81") (pin "CKI") (pinfunction "CI_CKI") (pintype "bidirectional"))
    )
    (net (code "167") (name "Net-(U80-DO)") (class "Default")
      (node (ref "U80") (pin "SDO") (pinfunction "DO_SDO") (pintype "bidirectional"))
      (node (ref "U81") (pin "SDI") (pinfunction "DI_SDI") (pintype "bidirectional"))
    )
    (net (code "168") (name "Net-(U81-CO)") (class "Default")
      (node (ref "U81") (pin "CKO") (pinfunction "CO_CKO") (pintype "bidirectional"))
      (node (ref "U82") (pin "CKI") (pinfunction "CI_CKI") (pintype "bidirectional"))
    )
    (net (code "169") (name "Net-(U81-DO)") (class "Default")
      (node (ref "U81") (pin "SDO") (pinfunction "DO_SDO") (pintype "bidirectional"))
      (node (ref "U82") (pin "SDI") (pinfunction "DI_SDI") (pintype "bidirectional"))
    )
    (net (code "170") (name "Net-(U82-CO)") (class "Default")
      (node (ref "U82") (pin "CKO") (pinfunction "CO_CKO") (pintype "bidirectional"))
      (node (ref "U83") (pin "CKI") (pinfunction "CI_CKI") (pintype "bidirectional"))
    )
    (net (code "171") (name "Net-(U82-DO)") (class "Default")
      (node (ref "U82") (pin "SDO") (pinfunction "DO_SDO") (pintype "bidirectional"))
      (node (ref "U83") (pin "SDI") (pinfunction "DI_SDI") (pintype "bidirectional"))
    )
    (net (code "172") (name "Net-(U83-CO)") (class "Default")
      (node (ref "U83") (pin "CKO") (pinfunction "CO_CKO") (pintype "bidirectional"))
      (node (ref "U84") (pin "CKI") (pinfunction "CI_CKI") (pintype "bidirectional"))
    )
    (net (code "173") (name "Net-(U83-DO)") (class "Default")
      (node (ref "U83") (pin "SDO") (pinfunction "DO_SDO") (pintype "bidirectional"))
      (node (ref "U84") (pin "SDI") (pinfunction "DI_SDI") (pintype "bidirectional"))
    )
    (net (code "174") (name "Net-(U85-CO)") (class "Default")
      (node (ref "U85") (pin "CKO") (pinfunction "CO_CKO") (pintype "bidirectional"))
      (node (ref "U86") (pin "CKI") (pinfunction "CI_CKI") (pintype "bidirectional"))
    )
    (net (code "175") (name "Net-(U85-DO)") (class "Default")
      (node (ref "U85") (pin "SDO") (pinfunction "DO_SDO") (pintype "bidirectional"))
      (node (ref "U86") (pin "SDI") (pinfunction "DI_SDI") (pintype "bidirectional"))
    )
    (net (code "176") (name "Net-(U86-CO)") (class "Default")
      (node (ref "U86") (pin "CKO") (pinfunction "CO_CKO") (pintype "bidirectional"))
      (node (ref "U87") (pin "CKI") (pinfunction "CI_CKI") (pintype "bidirectional"))
    )
    (net (code "177") (name "Net-(U86-DO)") (class "Default")
      (node (ref "U86") (pin "SDO") (pinfunction "DO_SDO") (pintype "bidirectional"))
      (node (ref "U87") (pin "SDI") (pinfunction "DI_SDI") (pintype "bidirectional"))
    )
    (net (code "178") (name "Net-(U87-CO)") (class "Default")
      (node (ref "U87") (pin "CKO") (pinfunction "CO_CKO") (pintype "bidirectional"))
      (node (ref "U88") (pin "CKI") (pinfunction "CI_CKI") (pintype "bidirectional"))
    )
    (net (code "179") (name "Net-(U87-DO)") (class "Default")
      (node (ref "U87") (pin "SDO") (pinfunction "DO_SDO") (pintype "bidirectional"))
      (node (ref "U88") (pin "SDI") (pinfunction "DI_SDI") (pintype "bidirectional"))
    )
    (net (code "180") (name "Net-(U88-CO)") (class "Default")
      (node (ref "U88") (pin "CKO") (pinfunction "CO_CKO") (pintype "bidirectional"))
      (node (ref "U89") (pin "CKI") (pinfunction "CI_CKI") (pintype "bidirectional"))
    )
    (net (code "181") (name "Net-(U88-DO)") (class "Default")
      (node (ref "U88") (pin "SDO") (pinfunction "DO_SDO") (pintype "bidirectional"))
      (node (ref "U89") (pin "SDI") (pinfunction "DI_SDI") (pintype "bidirectional"))
    )
    (net (code "182") (name "Net-(U89-CO)") (class "Default")
      (node (ref "U89") (pin "CKO") (pinfunction "CO_CKO") (pintype "bidirectional"))
      (node (ref "U90") (pin "CKI") (pinfunction "CI_CKI") (pintype "bidirectional"))
    )
    (net (code "183") (name "Net-(U89-DO)") (class "Default")
      (node (ref "U89") (pin "SDO") (pinfunction "DO_SDO") (pintype "bidirectional"))
      (node (ref "U90") (pin "SDI") (pinfunction "DI_SDI") (pintype "bidirectional"))
    )
    (net (code "184") (name "Net-(U90-CO)") (class "Default")
      (node (ref "U90") (pin "CKO") (pinfunction "CO_CKO") (pintype "bidirectional"))
      (node (ref "U91") (pin "CKI") (pinfunction "CI_CKI") (pintype "bidirectional"))
    )
    (net (code "185") (name "Net-(U90-DO)") (class "Default")
      (node (ref "U90") (pin "SDO") (pinfunction "DO_SDO") (pintype "bidirectional"))
      (node (ref "U91") (pin "SDI") (pinfunction "DI_SDI") (pintype "bidirectional"))
    )
    (net (code "186") (name "Net-(U91-CO)") (class "Default")
      (node (ref "U91") (pin "CKO") (pinfunction "CO_CKO") (pintype "bidirectional"))
      (node (ref "U92") (pin "CKI") (pinfunction "CI_CKI") (pintype "bidirectional"))
    )
    (net (code "187") (name "Net-(U91-DO)") (class "Default")
      (node (ref "U91") (pin "SDO") (pinfunction "DO_SDO") (pintype "bidirectional"))
      (node (ref "U92") (pin "SDI") (pinfunction "DI_SDI") (pintype "bidirectional"))
    )
    (net (code "188") (name "Net-(U92-CO)") (class "Default")
      (node (ref "U92") (pin "CKO") (pinfunction "CO_CKO") (pintype "bidirectional"))
      (node (ref "U93") (pin "CKI") (pinfunction "CI_CKI") (pintype "bidirectional"))
    )
    (net (code "189") (name "Net-(U92-DO)") (class "Default")
      (node (ref "U92") (pin "SDO") (pinfunction "DO_SDO") (pintype "bidirectional"))
      (node (ref "U93") (pin "SDI") (pinfunction "DI_SDI") (pintype "bidirectional"))
    )
    (net (code "190") (name "Net-(U93-CO)") (class "Default")
      (node (ref "U93") (pin "CKO") (pinfunction "CO_CKO") (pintype "bidirectional"))
      (node (ref "U94") (pin "CKI") (pinfunction "CI_CKI") (pintype "bidirectional"))
    )
    (net (code "191") (name "Net-(U93-DO)") (class "Default")
      (node (ref "U93") (pin "SDO") (pinfunction "DO_SDO") (pintype "bidirectional"))
      (node (ref "U94") (pin "SDI") (pinfunction "DI_SDI") (pintype "bidirectional"))
    )
    (net (code "192") (name "Net-(U94-CO)") (class "Default")
      (node (ref "U94") (pin "CKO") (pinfunction "CO_CKO") (pintype "bidirectional"))
      (node (ref "U95") (pin "CKI") (pinfunction "CI_CKI") (pintype "bidirectional"))
    )
    (net (code "193") (name "Net-(U94-DO)") (class "Default")
      (node (ref "U94") (pin "SDO") (pinfunction "DO_SDO") (pintype "bidirectional"))
      (node (ref "U95") (pin "SDI") (pinfunction "DI_SDI") (pintype "bidirectional"))
    )
    (net (code "194") (name "Net-(U96-CO)") (class "Default")
      (node (ref "U96") (pin "CKO") (pinfunction "CO_CKO") (pintype "bidirectional"))
      (node (ref "U97") (pin "CKI") (pinfunction "CI_CKI") (pintype "bidirectional"))
    )
    (net (code "195") (name "Net-(U96-DO)") (class "Default")
      (node (ref "U96") (pin "SDO") (pinfunction "DO_SDO") (pintype "bidirectional"))
      (node (ref "U97") (pin "SDI") (pinfunction "DI_SDI") (pintype "bidirectional"))
    )
    (net (code "196") (name "Net-(U97-CO)") (class "Default")
      (node (ref "U97") (pin "CKO") (pinfunction "CO_CKO") (pintype "bidirectional"))
      (node (ref "U98") (pin "CKI") (pinfunction "CI_CKI") (pintype "bidirectional"))
    )
    (net (code "197") (name "Net-(U97-DO)") (class "Default")
      (node (ref "U97") (pin "SDO") (pinfunction "DO_SDO") (pintype "bidirectional"))
      (node (ref "U98") (pin "SDI") (pinfunction "DI_SDI") (pintype "bidirectional"))
    )
    (net (code "198") (name "Net-(U98-CO)") (class "Default")
      (node (ref "U98") (pin "CKO") (pinfunction "CO_CKO") (pintype "bidirectional"))
      (node (ref "U99") (pin "CKI") (pinfunction "CI_CKI") (pintype "bidirectional"))
    )
    (net (code "199") (name "Net-(U98-DO)") (class "Default")
      (node (ref "U98") (pin "SDO") (pinfunction "DO_SDO") (pintype "bidirectional"))
      (node (ref "U99") (pin "SDI") (pinfunction "DI_SDI") (pintype "bidirectional"))
    )
    (net (code "200") (name "Net-(U100-CI)") (class "Default")
      (node (ref "U100") (pin "CKI") (pinfunction "CI_CKI") (pintype "bidirectional"))
      (node (ref "U99") (pin "CKO") (pinfunction "CO_CKO") (pintype "bidirectional"))
    )
    (net (code "201") (name "Net-(U100-CO)") (class "Default")
      (node (ref "U100") (pin "CKO") (pinfunction "CO_CKO") (pintype "bidirectional"))
      (node (ref "U101") (pin "CKI") (pinfunction "CI_CKI") (pintype "bidirectional"))
    )
    (net (code "202") (name "Net-(U100-DI)") (class "Default")
      (node (ref "U100") (pin "SDI") (pinfunction "DI_SDI") (pintype "bidirectional"))
      (node (ref "U99") (pin "SDO") (pinfunction "DO_SDO") (pintype "bidirectional"))
    )
    (net (code "203") (name "Net-(U100-DO)") (class "Default")
      (node (ref "U100") (pin "SDO") (pinfunction "DO_SDO") (pintype "bidirectional"))
      (node (ref "U101") (pin "SDI") (pinfunction "DI_SDI") (pintype "bidirectional"))
    )
    (net (code "204") (name "Net-(U101-CO)") (class "Default")
      (node (ref "U101") (pin "CKO") (pinfunction "CO_CKO") (pintype "bidirectional"))
      (node (ref "U102") (pin "CKI") (pinfunction "CI_CKI") (pintype "bidirectional"))
    )
    (net (code "205") (name "Net-(U101-DO)") (class "Default")
      (node (ref "U101") (pin "SDO") (pinfunction "DO_SDO") (pintype "bidirectional"))
      (node (ref "U102") (pin "SDI") (pinfunction "DI_SDI") (pintype "bidirectional"))
    )
    (net (code "206") (name "Net-(U102-CO)") (class "Default")
      (node (ref "U102") (pin "CKO") (pinfunction "CO_CKO") (pintype "bidirectional"))
      (node (ref "U103") (pin "CKI") (pinfunction "CI_CKI") (pintype "bidirectional"))
    )
    (net (code "207") (name "Net-(U102-DO)") (class "Default")
      (node (ref "U102") (pin "SDO") (pinfunction "DO_SDO") (pintype "bidirectional"))
      (node (ref "U103") (pin "SDI") (pinfunction "DI_SDI") (pintype "bidirectional"))
    )
    (net (code "208") (name "Net-(U103-CO)") (class "Default")
      (node (ref "U103") (pin "CKO") (pinfunction "CO_CKO") (pintype "bidirectional"))
      (node (ref "U104") (pin "CKI") (pinfunction "CI_CKI") (pintype "bidirectional"))
    )
    (net (code "209") (name "Net-(U103-DO)") (class "Default")
      (node (ref "U103") (pin "SDO") (pinfunction "DO_SDO") (pintype "bidirectional"))
      (node (ref "U104") (pin "SDI") (pinfunction "DI_SDI") (pintype "bidirectional"))
    )
    (net (code "210") (name "Net-(U104-CO)") (class "Default")
      (node (ref "U104") (pin "CKO") (pinfunction "CO_CKO") (pintype "bidirectional"))
      (node (ref "U105") (pin "CKI") (pinfunction "CI_CKI") (pintype "bidirectional"))
    )
    (net (code "211") (name "Net-(U104-DO)") (class "Default")
      (node (ref "U104") (pin "SDO") (pinfunction "DO_SDO") (pintype "bidirectional"))
      (node (ref "U105") (pin "SDI") (pinfunction "DI_SDI") (pintype "bidirectional"))
    )
    (net (code "212") (name "Net-(U105-CO)") (class "Default")
      (node (ref "U105") (pin "CKO") (pinfunction "CO_CKO") (pintype "bidirectional"))
      (node (ref "U106") (pin "CKI") (pinfunction "CI_CKI") (pintype "bidirectional"))
    )
    (net (code "213") (name "Net-(U105-DO)") (class "Default")
      (node (ref "U105") (pin "SDO") (pinfunction "DO_SDO") (pintype "bidirectional"))
      (node (ref "U106") (pin "SDI") (pinfunction "DI_SDI") (pintype "bidirectional"))
    )
    (net (code "214") (name "Net-(U106-CO)") (class "Default")
      (node (ref "U106") (pin "CKO") (pinfunction "CO_CKO") (pintype "bidirectional"))
      (node (ref "U107") (pin "CKI") (pinfunction "CI_CKI") (pintype "bidirectional"))
    )
    (net (code "215") (name "Net-(U106-DO)") (class "Default")
      (node (ref "U106") (pin "SDO") (pinfunction "DO_SDO") (pintype "bidirectional"))
      (node (ref "U107") (pin "SDI") (pinfunction "DI_SDI") (pintype "bidirectional"))
    )
    (net (code "216") (name "Net-(U107-CO)") (class "Default")
      (node (ref "U107") (pin "CKO") (pinfunction "CO_CKO") (pintype "bidirectional"))
      (node (ref "U108") (pin "CKI") (pinfunction "CI_CKI") (pintype "bidirectional"))
    )
    (net (code "217") (name "Net-(U107-DO)") (class "Default")
      (node (ref "U107") (pin "SDO") (pinfunction "DO_SDO") (pintype "bidirectional"))
      (node (ref "U108") (pin "SDI") (pinfunction "DI_SDI") (pintype "bidirectional"))
    )
    (net (code "218") (name "Net-(U108-CO)") (class "Default")
      (node (ref "U108") (pin "CKO") (pinfunction "CO_CKO") (pintype "bidirectional"))
      (node (ref "U109") (pin "CKI") (pinfunction "CI_CKI") (pintype "bidirectional"))
    )
    (net (code "219") (name "Net-(U108-DO)") (class "Default")
      (node (ref "U108") (pin "SDO") (pinfunction "DO_SDO") (pintype "bidirectional"))
      (node (ref "U109") (pin "SDI") (pinfunction "DI_SDI") (pintype "bidirectional"))
    )
    (net (code "220") (name "Net-(U109-CO)") (class "Default")
      (node (ref "U109") (pin "CKO") (pinfunction "CO_CKO") (pintype "bidirectional"))
      (node (ref "U110") (pin "CKI") (pinfunction "CI_CKI") (pintype "bidirectional"))
    )
    (net (code "221") (name "Net-(U109-DO)") (class "Default")
      (node (ref "U109") (pin "SDO") (pinfunction "DO_SDO") (pintype "bidirectional"))
      (node (ref "U110") (pin "SDI") (pinfunction "DI_SDI") (pintype "bidirectional"))
    )
    (net (code "222") (name "Net-(U110-CO)") (class "Default")
      (node (ref "U110") (pin "CKO") (pinfunction "CO_CKO") (pintype "bidirectional"))
      (node (ref "U111") (pin "CKI") (pinfunction "CI_CKI") (pintype "bidirectional"))
    )
    (net (code "223") (name "Net-(U110-DO)") (class "Default")
      (node (ref "U110") (pin "SDO") (pinfunction "DO_SDO") (pintype "bidirectional"))
      (node (ref "U111") (pin "SDI") (pinfunction "DI_SDI") (pintype "bidirectional"))
    )
    (net (code "224") (name "Net-(U111-CO)") (class "Default")
      (node (ref "U111") (pin "CKO") (pinfunction "CO_CKO") (pintype "bidirectional"))
      (node (ref "U112") (pin "CKI") (pinfunction "CI_CKI") (pintype "bidirectional"))
    )
    (net (code "225") (name "Net-(U111-DO)") (class "Default")
      (node (ref "U111") (pin "SDO") (pinfunction "DO_SDO") (pintype "bidirectional"))
      (node (ref "U112") (pin "SDI") (pinfunction "DI_SDI") (pintype "bidirectional"))
    )
    (net (code "226") (name "Net-(U113-CO)") (class "Default")
      (node (ref "U113") (pin "CKO") (pinfunction "CO_CKO") (pintype "bidirectional"))
      (node (ref "U114") (pin "CKI") (pinfunction "CI_CKI") (pintype "bidirectional"))
    )
    (net (code "227") (name "Net-(U113-DO)") (class "Default")
      (node (ref "U113") (pin "SDO") (pinfunction "DO_SDO") (pintype "bidirectional"))
      (node (ref "U114") (pin "SDI") (pinfunction "DI_SDI") (pintype "bidirectional"))
    )
    (net (code "228") (name "Net-(U114-CO)") (class "Default")
      (node (ref "U114") (pin "CKO") (pinfunction "CO_CKO") (pintype "bidirectional"))
      (node (ref "U115") (pin "CKI") (pinfunction "CI_CKI") (pintype "bidirectional"))
    )
    (net (code "229") (name "Net-(U114-DO)") (class "Default")
      (node (ref "U114") (pin "SDO") (pinfunction "DO_SDO") (pintype "bidirectional"))
      (node (ref "U115") (pin "SDI") (pinfunction "DI_SDI") (pintype "bidirectional"))
    )
    (net (code "230") (name "Net-(U115-CO)") (class "Default")
      (node (ref "U115") (pin "CKO") (pinfunction "CO_CKO") (pintype "bidirectional"))
      (node (ref "U116") (pin "CKI") (pinfunction "CI_CKI") (pintype "bidirectional"))
    )
    (net (code "231") (name "Net-(U115-DO)") (class "Default")
      (node (ref "U115") (pin "SDO") (pinfunction "DO_SDO") (pintype "bidirectional"))
      (node (ref "U116") (pin "SDI") (pinfunction "DI_SDI") (pintype "bidirectional"))
    )
    (net (code "232") (name "Net-(U116-CO)") (class "Default")
      (node (ref "U116") (pin "CKO") (pinfunction "CO_CKO") (pintype "bidirectional"))
      (node (ref "U117") (pin "CKI") (pinfunction "CI_CKI") (pintype "bidirectional"))
    )
    (net (code "233") (name "Net-(U116-DO)") (class "Default")
      (node (ref "U116") (pin "SDO") (pinfunction "DO_SDO") (pintype "bidirectional"))
      (node (ref "U117") (pin "SDI") (pinfunction "DI_SDI") (pintype "bidirectional"))
    )
    (net (code "234") (name "Net-(U117-CO)") (class "Default")
      (node (ref "U117") (pin "CKO") (pinfunction "CO_CKO") (pintype "bidirectional"))
      (node (ref "U118") (pin "CKI") (pinfunction "CI_CKI") (pintype "bidirectional"))
    )
    (net (code "235") (name "Net-(U117-DO)") (class "Default")
      (node (ref "U117") (pin "SDO") (pinfunction "DO_SDO") (pintype "bidirectional"))
      (node (ref "U118") (pin "SDI") (pinfunction "DI_SDI") (pintype "bidirectional"))
    )
    (net (code "236") (name "Net-(U118-CO)") (class "Default")
      (node (ref "U118") (pin "CKO") (pinfunction "CO_CKO") (pintype "bidirectional"))
      (node (ref "U119") (pin "CKI") (pinfunction "CI_CKI") (pintype "bidirectional"))
    )
    (net (code "237") (name "Net-(U118-DO)") (class "Default")
      (node (ref "U118") (pin "SDO") (pinfunction "DO_SDO") (pintype "bidirectional"))
      (node (ref "U119") (pin "SDI") (pinfunction "DI_SDI") (pintype "bidirectional"))
    )
    (net (code "238") (name "Net-(U119-CO)") (class "Default")
      (node (ref "U119") (pin "CKO") (pinfunction "CO_CKO") (pintype "bidirectional"))
      (node (ref "U120") (pin "CKI") (pinfunction "CI_CKI") (pintype "bidirectional"))
    )
    (net (code "239") (name "Net-(U119-DO)") (class "Default")
      (node (ref "U119") (pin "SDO") (pinfunction "DO_SDO") (pintype "bidirectional"))
      (node (ref "U120") (pin "SDI") (pinfunction "DI_SDI") (pintype "bidirectional"))
    )
    (net (code "240") (name "Net-(U120-CO)") (class "Default")
      (node (ref "U120") (pin "CKO") (pinfunction "CO_CKO") (pintype "bidirectional"))
      (node (ref "U121") (pin "CKI") (pinfunction "CI_CKI") (pintype "bidirectional"))
    )
    (net (code "241") (name "Net-(U120-DO)") (class "Default")
      (node (ref "U120") (pin "SDO") (pinfunction "DO_SDO") (pintype "bidirectional"))
      (node (ref "U121") (pin "SDI") (pinfunction "DI_SDI") (pintype "bidirectional"))
    )
    (net (code "242") (name "Net-(U121-CO)") (class "Default")
      (node (ref "U121") (pin "CKO") (pinfunction "CO_CKO") (pintype "bidirectional"))
      (node (ref "U122") (pin "CKI") (pinfunction "CI_CKI") (pintype "bidirectional"))
    )
    (net (code "243") (name "Net-(U121-DO)") (class "Default")
      (node (ref "U121") (pin "SDO") (pinfunction "DO_SDO") (pintype "bidirectional"))
      (node (ref "U122") (pin "SDI") (pinfunction "DI_SDI") (pintype "bidirectional"))
    )
    (net (code "244") (name "Net-(U122-CO)") (class "Default")
      (node (ref "U122") (pin "CKO") (pinfunction "CO_CKO") (pintype "bidirectional"))
      (node (ref "U123") (pin "CKI") (pinfunction "CI_CKI") (pintype "bidirectional"))
    )
    (net (code "245") (name "Net-(U122-DO)") (class "Default")
      (node (ref "U122") (pin "SDO") (pinfunction "DO_SDO") (pintype "bidirectional"))
      (node (ref "U123") (pin "SDI") (pinfunction "DI_SDI") (pintype "bidirectional"))
    )
    (net (code "246") (name "Net-(U123-CO)") (class "Default")
      (node (ref "U123") (pin "CKO") (pinfunction "CO_CKO") (pintype "bidirectional"))
      (node (ref "U124") (pin "CKI") (pinfunction "CI_CKI") (pintype "bidirectional"))
    )
    (net (code "247") (name "Net-(U123-DO)") (class "Default")
      (node (ref "U123") (pin "SDO") (pinfunction "DO_SDO") (pintype "bidirectional"))
      (node (ref "U124") (pin "SDI") (pinfunction "DI_SDI") (pintype "bidirectional"))
    )
    (net (code "248") (name "Net-(U124-CO)") (class "Default")
      (node (ref "U124") (pin "CKO") (pinfunction "CO_CKO") (pintype "bidirectional"))
      (node (ref "U125") (pin "CKI") (pinfunction "CI_CKI") (pintype "bidirectional"))
    )
    (net (code "249") (name "Net-(U124-DO)") (class "Default")
      (node (ref "U124") (pin "SDO") (pinfunction "DO_SDO") (pintype "bidirectional"))
      (node (ref "U125") (pin "SDI") (pinfunction "DI_SDI") (pintype "bidirectional"))
    )
    (net (code "250") (name "Net-(U125-CO)") (class "Default")
      (node (ref "U125") (pin "CKO") (pinfunction "CO_CKO") (pintype "bidirectional"))
      (node (ref "U126") (pin "CKI") (pinfunction "CI_CKI") (pintype "bidirectional"))
    )
    (net (code "251") (name "Net-(U125-DO)") (class "Default")
      (node (ref "U125") (pin "SDO") (pinfunction "DO_SDO") (pintype "bidirectional"))
      (node (ref "U126") (pin "SDI") (pinfunction "DI_SDI") (pintype "bidirectional"))
    )
    (net (code "252") (name "Net-(U127-CI)") (class "Default")
      (node (ref "J1") (pin "4") (pinfunction "4_4") (pintype "passive"))
      (node (ref "U127") (pin "CKI") (pinfunction "CI_CKI") (pintype "bidirectional"))
    )
    (net (code "253") (name "Net-(U127-CO)") (class "Default")
      (node (ref "U127") (pin "CKO") (pinfunction "CO_CKO") (pintype "bidirectional"))
      (node (ref "U128") (pin "CKI") (pinfunction "CI_CKI") (pintype "bidirectional"))
    )
    (net (code "254") (name "Net-(U127-DI)") (class "Default")
      (node (ref "J1") (pin "3") (pinfunction "3_3") (pintype "passive"))
      (node (ref "U127") (pin "SDI") (pinfunction "DI_SDI") (pintype "bidirectional"))
    )
    (net (code "255") (name "Net-(U127-DO)") (class "Default")
      (node (ref "U127") (pin "SDO") (pinfunction "DO_SDO") (pintype "bidirectional"))
      (node (ref "U128") (pin "SDI") (pinfunction "DI_SDI") (pintype "bidirectional"))
    )
    (net (code "256") (name "Net-(U128-CO)") (class "Default")
      (node (ref "U128") (pin "CKO") (pinfunction "CO_CKO") (pintype "bidirectional"))
      (node (ref "U129") (pin "CKI") (pinfunction "CI_CKI") (pintype "bidirectional"))
    )
    (net (code "257") (name "Net-(U128-DO)") (class "Default")
      (node (ref "U128") (pin "SDO") (pinfunction "DO_SDO") (pintype "bidirectional"))
      (node (ref "U129") (pin "SDI") (pinfunction "DI_SDI") (pintype "bidirectional"))
    )
    (net (code "258") (name "Net-(U129-CO)") (class "Default")
      (node (ref "U129") (pin "CKO") (pinfunction "CO_CKO") (pintype "bidirectional"))
      (node (ref "U130") (pin "CKI") (pinfunction "CI_CKI") (pintype "bidirectional"))
    )
    (net (code "259") (name "Net-(U129-DO)") (class "Default")
      (node (ref "U129") (pin "SDO") (pinfunction "DO_SDO") (pintype "bidirectional"))
      (node (ref "U130") (pin "SDI") (pinfunction "DI_SDI") (pintype "bidirectional"))
    )
    (net (code "260") (name "Net-(U130-CO)") (class "Default")
      (node (ref "U130") (pin "CKO") (pinfunction "CO_CKO") (pintype "bidirectional"))
      (node (ref "U131") (pin "CKI") (pinfunction "CI_CKI") (pintype "bidirectional"))
    )
    (net (code "261") (name "Net-(U130-DO)") (class "Default")
      (node (ref "U130") (pin "SDO") (pinfunction "DO_SDO") (pintype "bidirectional"))
      (node (ref "U131") (pin "SDI") (pinfunction "DI_SDI") (pintype "bidirectional"))
    )
    (net (code "262") (name "Net-(U131-CO)") (class "Default")
      (node (ref "U131") (pin "CKO") (pinfunction "CO_CKO") (pintype "bidirectional"))
      (node (ref "U132") (pin "CKI") (pinfunction "CI_CKI") (pintype "bidirectional"))
    )
    (net (code "263") (name "Net-(U131-DO)") (class "Default")
      (node (ref "U131") (pin "SDO") (pinfunction "DO_SDO") (pintype "bidirectional"))
      (node (ref "U132") (pin "SDI") (pinfunction "DI_SDI") (pintype "bidirectional"))
    )
    (net (code "264") (name "Net-(U132-CO)") (class "Default")
      (node (ref "U132") (pin "CKO") (pinfunction "CO_CKO") (pintype "bidirectional"))
      (node (ref "U133") (pin "CKI") (pinfunction "CI_CKI") (pintype "bidirectional"))
    )
    (net (code "265") (name "Net-(U132-DO)") (class "Default")
      (node (ref "U132") (pin "SDO") (pinfunction "DO_SDO") (pintype "bidirectional"))
      (node (ref "U133") (pin "SDI") (pinfunction "DI_SDI") (pintype "bidirectional"))
    )
    (net (code "266") (name "Net-(U133-CO)") (class "Default")
      (node (ref "U133") (pin "CKO") (pinfunction "CO_CKO") (pintype "bidirectional"))
      (node (ref "U134") (pin "CKI") (pinfunction "CI_CKI") (pintype "bidirectional"))
    )
    (net (code "267") (name "Net-(U133-DO)") (class "Default")
      (node (ref "U133") (pin "SDO") (pinfunction "DO_SDO") (pintype "bidirectional"))
      (node (ref "U134") (pin "SDI") (pinfunction "DI_SDI") (pintype "bidirectional"))
    )
    (net (code "268") (name "Net-(U134-CO)") (class "Default")
      (node (ref "U134") (pin "CKO") (pinfunction "CO_CKO") (pintype "bidirectional"))
      (node (ref "U135") (pin "CKI") (pinfunction "CI_CKI") (pintype "bidirectional"))
    )
    (net (code "269") (name "Net-(U134-DO)") (class "Default")
      (node (ref "U134") (pin "SDO") (pinfunction "DO_SDO") (pintype "bidirectional"))
      (node (ref "U135") (pin "SDI") (pinfunction "DI_SDI") (pintype "bidirectional"))
    )
    (net (code "270") (name "Net-(U135-CO)") (class "Default")
      (node (ref "U135") (pin "CKO") (pinfunction "CO_CKO") (pintype "bidirectional"))
      (node (ref "U136") (pin "CKI") (pinfunction "CI_CKI") (pintype "bidirectional"))
    )
    (net (code "271") (name "Net-(U135-DO)") (class "Default")
      (node (ref "U135") (pin "SDO") (pinfunction "DO_SDO") (pintype "bidirectional"))
      (node (ref "U136") (pin "SDI") (pinfunction "DI_SDI") (pintype "bidirectional"))
    )
    (net (code "272") (name "Net-(U136-CO)") (class "Default")
      (node (ref "U136") (pin "CKO") (pinfunction "CO_CKO") (pintype "bidirectional"))
      (node (ref "U137") (pin "CKI") (pinfunction "CI_CKI") (pintype "bidirectional"))
    )
    (net (code "273") (name "Net-(U136-DO)") (class "Default")
      (node (ref "U136") (pin "SDO") (pinfunction "DO_SDO") (pintype "bidirectional"))
      (node (ref "U137") (pin "SDI") (pinfunction "DI_SDI") (pintype "bidirectional"))
    )
    (net (code "274") (name "Net-(U137-CO)") (class "Default")
      (node (ref "U137") (pin "CKO") (pinfunction "CO_CKO") (pintype "bidirectional"))
      (node (ref "U138") (pin "CKI") (pinfunction "CI_CKI") (pintype "bidirectional"))
    )
    (net (code "275") (name "Net-(U137-DO)") (class "Default")
      (node (ref "U137") (pin "SDO") (pinfunction "DO_SDO") (pintype "bidirectional"))
      (node (ref "U138") (pin "SDI") (pinfunction "DI_SDI") (pintype "bidirectional"))
    )
    (net (code "276") (name "Net-(U138-CO)") (class "Default")
      (node (ref "U138") (pin "CKO") (pinfunction "CO_CKO") (pintype "bidirectional"))
      (node (ref "U139") (pin "CKI") (pinfunction "CI_CKI") (pintype "bidirectional"))
    )
    (net (code "277") (name "Net-(U138-DO)") (class "Default")
      (node (ref "U138") (pin "SDO") (pinfunction "DO_SDO") (pintype "bidirectional"))
      (node (ref "U139") (pin "SDI") (pinfunction "DI_SDI") (pintype "bidirectional"))
    )
    (net (code "278") (name "Net-(U139-CO)") (class "Default")
      (node (ref "U139") (pin "CKO") (pinfunction "CO_CKO") (pintype "bidirectional"))
      (node (ref "U140") (pin "CKI") (pinfunction "CI_CKI") (pintype "bidirectional"))
    )
    (net (code "279") (name "Net-(U139-DO)") (class "Default")
      (node (ref "U139") (pin "SDO") (pinfunction "DO_SDO") (pintype "bidirectional"))
      (node (ref "U140") (pin "SDI") (pinfunction "DI_SDI") (pintype "bidirectional"))
    )
    (net (code "280") (name "Net-(U141-CO)") (class "Default")
      (node (ref "U141") (pin "CKO") (pinfunction "CO_CKO") (pintype "bidirectional"))
      (node (ref "U142") (pin "CKI") (pinfunction "CI_CKI") (pintype "bidirectional"))
    )
    (net (code "281") (name "Net-(U141-DO)") (class "Default")
      (node (ref "U141") (pin "SDO") (pinfunction "DO_SDO") (pintype "bidirectional"))
      (node (ref "U142") (pin "SDI") (pinfunction "DI_SDI") (pintype "bidirectional"))
    )
    (net (code "282") (name "Net-(U142-CO)") (class "Default")
      (node (ref "U142") (pin "CKO") (pinfunction "CO_CKO") (pintype "bidirectional"))
      (node (ref "U143") (pin "CKI") (pinfunction "CI_CKI") (pintype "bidirectional"))
    )
    (net (code "283") (name "Net-(U142-DO)") (class "Default")
      (node (ref "U142") (pin "SDO") (pinfunction "DO_SDO") (pintype "bidirectional"))
      (node (ref "U143") (pin "SDI") (pinfunction "DI_SDI") (pintype "bidirectional"))
    )
    (net (code "284") (name "Net-(U143-CO)") (class "Default")
      (node (ref "U143") (pin "CKO") (pinfunction "CO_CKO") (pintype "bidirectional"))
      (node (ref "U144") (pin "CKI") (pinfunction "CI_CKI") (pintype "bidirectional"))
    )
    (net (code "285") (name "Net-(U143-DO)") (class "Default")
      (node (ref "U143") (pin "SDO") (pinfunction "DO_SDO") (pintype "bidirectional"))
      (node (ref "U144") (pin "SDI") (pinfunction "DI_SDI") (pintype "bidirectional"))
    )
    (net (code "286") (name "Net-(U144-CO)") (class "Default")
      (node (ref "U144") (pin "CKO") (pinfunction "CO_CKO") (pintype "bidirectional"))
      (node (ref "U145") (pin "CKI") (pinfunction "CI_CKI") (pintype "bidirectional"))
    )
    (net (code "287") (name "Net-(U144-DO)") (class "Default")
      (node (ref "U144") (pin "SDO") (pinfunction "DO_SDO") (pintype "bidirectional"))
      (node (ref "U145") (pin "SDI") (pinfunction "DI_SDI") (pintype "bidirectional"))
    )
    (net (code "288") (name "Net-(U145-CO)") (class "Default")
      (node (ref "U145") (pin "CKO") (pinfunction "CO_CKO") (pintype "bidirectional"))
      (node (ref "U146") (pin "CKI") (pinfunction "CI_CKI") (pintype "bidirectional"))
    )
    (net (code "289") (name "Net-(U145-DO)") (class "Default")
      (node (ref "U145") (pin "SDO") (pinfunction "DO_SDO") (pintype "bidirectional"))
      (node (ref "U146") (pin "SDI") (pinfunction "DI_SDI") (pintype "bidirectional"))
    )
    (net (code "290") (name "Net-(U146-CO)") (class "Default")
      (node (ref "U146") (pin "CKO") (pinfunction "CO_CKO") (pintype "bidirectional"))
      (node (ref "U147") (pin "CKI") (pinfunction "CI_CKI") (pintype "bidirectional"))
    )
    (net (code "291") (name "Net-(U146-DO)") (class "Default")
      (node (ref "U146") (pin "SDO") (pinfunction "DO_SDO") (pintype "bidirectional"))
      (node (ref "U147") (pin "SDI") (pinfunction "DI_SDI") (pintype "bidirectional"))
    )
    (net (code "292") (name "Net-(U147-CO)") (class "Default")
      (node (ref "U147") (pin "CKO") (pinfunction "CO_CKO") (pintype "bidirectional"))
      (node (ref "U148") (pin "CKI") (pinfunction "CI_CKI") (pintype "bidirectional"))
    )
    (net (code "293") (name "Net-(U147-DO)") (class "Default")
      (node (ref "U147") (pin "SDO") (pinfunction "DO_SDO") (pintype "bidirectional"))
      (node (ref "U148") (pin "SDI") (pinfunction "DI_SDI") (pintype "bidirectional"))
    )
    (net (code "294") (name "Net-(U148-CO)") (class "Default")
      (node (ref "U148") (pin "CKO") (pinfunction "CO_CKO") (pintype "bidirectional"))
      (node (ref "U149") (pin "CKI") (pinfunction "CI_CKI") (pintype "bidirectional"))
    )
    (net (code "295") (name "Net-(U148-DO)") (class "Default")
      (node (ref "U148") (pin "SDO") (pinfunction "DO_SDO") (pintype "bidirectional"))
      (node (ref "U149") (pin "SDI") (pinfunction "DI_SDI") (pintype "bidirectional"))
    )
    (net (code "296") (name "Net-(U149-CO)") (class "Default")
      (node (ref "U149") (pin "CKO") (pinfunction "CO_CKO") (pintype "bidirectional"))
      (node (ref "U150") (pin "CKI") (pinfunction "CI_CKI") (pintype "bidirectional"))
    )
    (net (code "297") (name "Net-(U149-DO)") (class "Default")
      (node (ref "U149") (pin "SDO") (pinfunction "DO_SDO") (pintype "bidirectional"))
      (node (ref "U150") (pin "SDI") (pinfunction "DI_SDI") (pintype "bidirectional"))
    )
    (net (code "298") (name "Net-(U150-CO)") (class "Default")
      (node (ref "U150") (pin "CKO") (pinfunction "CO_CKO") (pintype "bidirectional"))
      (node (ref "U151") (pin "CKI") (pinfunction "CI_CKI") (pintype "bidirectional"))
    )
    (net (code "299") (name "Net-(U150-DO)") (class "Default")
      (node (ref "U150") (pin "SDO") (pinfunction "DO_SDO") (pintype "bidirectional"))
      (node (ref "U151") (pin "SDI") (pinfunction "DI_SDI") (pintype "bidirectional"))
    )
    (net (code "300") (name "Net-(U151-CO)") (class "Default")
      (node (ref "U151") (pin "CKO") (pinfunction "CO_CKO") (pintype "bidirectional"))
      (node (ref "U152") (pin "CKI") (pinfunction "CI_CKI") (pintype "bidirectional"))
    )
    (net (code "301") (name "Net-(U151-DO)") (class "Default")
      (node (ref "U151") (pin "SDO") (pinfunction "DO_SDO") (pintype "bidirectional"))
      (node (ref "U152") (pin "SDI") (pinfunction "DI_SDI") (pintype "bidirectional"))
    )
    (net (code "302") (name "Net-(U152-CO)") (class "Default")
      (node (ref "U152") (pin "CKO") (pinfunction "CO_CKO") (pintype "bidirectional"))
      (node (ref "U153") (pin "CKI") (pinfunction "CI_CKI") (pintype "bidirectional"))
    )
    (net (code "303") (name "Net-(U152-DO)") (class "Default")
      (node (ref "U152") (pin "SDO") (pinfunction "DO_SDO") (pintype "bidirectional"))
      (node (ref "U153") (pin "SDI") (pinfunction "DI_SDI") (pintype "bidirectional"))
    )
    (net (code "304") (name "Net-(U153-CO)") (class "Default")
      (node (ref "U153") (pin "CKO") (pinfunction "CO_CKO") (pintype "bidirectional"))
      (node (ref "U154") (pin "CKI") (pinfunction "CI_CKI") (pintype "bidirectional"))
    )
    (net (code "305") (name "Net-(U153-DO)") (class "Default")
      (node (ref "U153") (pin "SDO") (pinfunction "DO_SDO") (pintype "bidirectional"))
      (node (ref "U154") (pin "SDI") (pinfunction "DI_SDI") (pintype "bidirectional"))
    )
    (net (code "306") (name "Net-(U154-CO)") (class "Default")
      (node (ref "U154") (pin "CKO") (pinfunction "CO_CKO") (pintype "bidirectional"))
      (node (ref "U155") (pin "CKI") (pinfunction "CI_CKI") (pintype "bidirectional"))
    )
    (net (code "307") (name "Net-(U154-DO)") (class "Default")
      (node (ref "U154") (pin "SDO") (pinfunction "DO_SDO") (pintype "bidirectional"))
      (node (ref "U155") (pin "SDI") (pinfunction "DI_SDI") (pintype "bidirectional"))
    )
    (net (code "308") (name "Net-(U155-CO)") (class "Default")
      (node (ref "U155") (pin "CKO") (pinfunction "CO_CKO") (pintype "bidirectional"))
      (node (ref "U156") (pin "CKI") (pinfunction "CI_CKI") (pintype "bidirectional"))
    )
    (net (code "309") (name "Net-(U155-DO)") (class "Default")
      (node (ref "U155") (pin "SDO") (pinfunction "DO_SDO") (pintype "bidirectional"))
      (node (ref "U156") (pin "SDI") (pinfunction "DI_SDI") (pintype "bidirectional"))
    )
    (net (code "310") (name "Net-(U156-CO)") (class "Default")
      (node (ref "U156") (pin "CKO") (pinfunction "CO_CKO") (pintype "bidirectional"))
      (node (ref "U157") (pin "CKI") (pinfunction "CI_CKI") (pintype "bidirectional"))
    )
    (net (code "311") (name "Net-(U156-DO)") (class "Default")
      (node (ref "U156") (pin "SDO") (pinfunction "DO_SDO") (pintype "bidirectional"))
      (node (ref "U157") (pin "SDI") (pinfunction "DI_SDI") (pintype "bidirectional"))
    )
    (net (code "312") (name "Net-(U157-CO)") (class "Default")
      (node (ref "U157") (pin "CKO") (pinfunction "CO_CKO") (pintype "bidirectional"))
      (node (ref "U158") (pin "CKI") (pinfunction "CI_CKI") (pintype "bidirectional"))
    )
    (net (code "313") (name "Net-(U157-DO)") (class "Default")
      (node (ref "U157") (pin "SDO") (pinfunction "DO_SDO") (pintype "bidirectional"))
      (node (ref "U158") (pin "SDI") (pinfunction "DI_SDI") (pintype "bidirectional"))
    )
    (net (code "314") (name "Net-(U158-CO)") (class "Default")
      (node (ref "U158") (pin "CKO") (pinfunction "CO_CKO") (pintype "bidirectional"))
      (node (ref "U159") (pin "CKI") (pinfunction "CI_CKI") (pintype "bidirectional"))
    )
    (net (code "315") (name "Net-(U158-DO)") (class "Default")
      (node (ref "U158") (pin "SDO") (pinfunction "DO_SDO") (pintype "bidirectional"))
      (node (ref "U159") (pin "SDI") (pinfunction "DI_SDI") (pintype "bidirectional"))
    )
    (net (code "316") (name "Net-(U159-CO)") (class "Default")
      (node (ref "U159") (pin "CKO") (pinfunction "CO_CKO") (pintype "bidirectional"))
      (node (ref "U160") (pin "CKI") (pinfunction "CI_CKI") (pintype "bidirectional"))
    )
    (net (code "317") (name "Net-(U159-DO)") (class "Default")
      (node (ref "U159") (pin "SDO") (pinfunction "DO_SDO") (pintype "bidirectional"))
      (node (ref "U160") (pin "SDI") (pinfunction "DI_SDI") (pintype "bidirectional"))
    )
    (net (code "318") (name "Net-(U160-CO)") (class "Default")
      (node (ref "U160") (pin "CKO") (pinfunction "CO_CKO") (pintype "bidirectional"))
      (node (ref "U161") (pin "CKI") (pinfunction "CI_CKI") (pintype "bidirectional"))
    )
    (net (code "319") (name "Net-(U160-DO)") (class "Default")
      (node (ref "U160") (pin "SDO") (pinfunction "DO_SDO") (pintype "bidirectional"))
      (node (ref "U161") (pin "SDI") (pinfunction "DI_SDI") (pintype "bidirectional"))
    )
    (net (code "320") (name "Net-(U161-CO)") (class "Default")
      (node (ref "U161") (pin "CKO") (pinfunction "CO_CKO") (pintype "bidirectional"))
      (node (ref "U162") (pin "CKI") (pinfunction "CI_CKI") (pintype "bidirectional"))
    )
    (net (code "321") (name "Net-(U161-DO)") (class "Default")
      (node (ref "U161") (pin "SDO") (pinfunction "DO_SDO") (pintype "bidirectional"))
      (node (ref "U162") (pin "SDI") (pinfunction "DI_SDI") (pintype "bidirectional"))
    )
    (net (code "322") (name "Net-(U162-CO)") (class "Default")
      (node (ref "U162") (pin "CKO") (pinfunction "CO_CKO") (pintype "bidirectional"))
      (node (ref "U163") (pin "CKI") (pinfunction "CI_CKI") (pintype "bidirectional"))
    )
    (net (code "323") (name "Net-(U162-DO)") (class "Default")
      (node (ref "U162") (pin "SDO") (pinfunction "DO_SDO") (pintype "bidirectional"))
      (node (ref "U163") (pin "SDI") (pinfunction "DI_SDI") (pintype "bidirectional"))
    )
    (net (code "324") (name "Net-(U163-CO)") (class "Default")
      (node (ref "U163") (pin "CKO") (pinfunction "CO_CKO") (pintype "bidirectional"))
      (node (ref "U164") (pin "CKI") (pinfunction "CI_CKI") (pintype "bidirectional"))
    )
    (net (code "325") (name "Net-(U163-DO)") (class "Default")
      (node (ref "U163") (pin "SDO") (pinfunction "DO_SDO") (pintype "bidirectional"))
      (node (ref "U164") (pin "SDI") (pinfunction "DI_SDI") (pintype "bidirectional"))
    )
    (net (code "326") (name "Net-(U164-CO)") (class "Default")
      (node (ref "U164") (pin "CKO") (pinfunction "CO_CKO") (pintype "bidirectional"))
      (node (ref "U165") (pin "CKI") (pinfunction "CI_CKI") (pintype "bidirectional"))
    )
    (net (code "327") (name "Net-(U164-DO)") (class "Default")
      (node (ref "U164") (pin "SDO") (pinfunction "DO_SDO") (pintype "bidirectional"))
      (node (ref "U165") (pin "SDI") (pinfunction "DI_SDI") (pintype "bidirectional"))
    )
    (net (code "328") (name "Net-(U165-CO)") (class "Default")
      (node (ref "U165") (pin "CKO") (pinfunction "CO_CKO") (pintype "bidirectional"))
      (node (ref "U166") (pin "CKI") (pinfunction "CI_CKI") (pintype "bidirectional"))
    )
    (net (code "329") (name "Net-(U165-DO)") (class "Default")
      (node (ref "U165") (pin "SDO") (pinfunction "DO_SDO") (pintype "bidirectional"))
      (node (ref "U166") (pin "SDI") (pinfunction "DI_SDI") (pintype "bidirectional"))
    )
    (net (code "330") (name "Net-(U166-CO)") (class "Default")
      (node (ref "U166") (pin "CKO") (pinfunction "CO_CKO") (pintype "bidirectional"))
      (node (ref "U167") (pin "CKI") (pinfunction "CI_CKI") (pintype "bidirectional"))
    )
    (net (code "331") (name "Net-(U166-DO)") (class "Default")
      (node (ref "U166") (pin "SDO") (pinfunction "DO_SDO") (pintype "bidirectional"))
      (node (ref "U167") (pin "SDI") (pinfunction "DI_SDI") (pintype "bidirectional"))
    )
    (net (code "332") (name "Net-(U167-CO)") (class "Default")
      (node (ref "U167") (pin "CKO") (pinfunction "CO_CKO") (pintype "bidirectional"))
      (node (ref "U168") (pin "CKI") (pinfunction "CI_CKI") (pintype "bidirectional"))
    )
    (net (code "333") (name "Net-(U167-DO)") (class "Default")
      (node (ref "U167") (pin "SDO") (pinfunction "DO_SDO") (pintype "bidirectional"))
      (node (ref "U168") (pin "SDI") (pinfunction "DI_SDI") (pintype "bidirectional"))
    )
    (net (code "334") (name "Net-(U169-CO)") (class "Default")
      (node (ref "U169") (pin "CKO") (pinfunction "CO_CKO") (pintype "bidirectional"))
      (node (ref "U170") (pin "CKI") (pinfunction "CI_CKI") (pintype "bidirectional"))
    )
    (net (code "335") (name "Net-(U169-DO)") (class "Default")
      (node (ref "U169") (pin "SDO") (pinfunction "DO_SDO") (pintype "bidirectional"))
      (node (ref "U170") (pin "SDI") (pinfunction "DI_SDI") (pintype "bidirectional"))
    )
    (net (code "336") (name "Net-(U170-CO)") (class "Default")
      (node (ref "U170") (pin "CKO") (pinfunction "CO_CKO") (pintype "bidirectional"))
      (node (ref "U171") (pin "CKI") (pinfunction "CI_CKI") (pintype "bidirectional"))
    )
    (net (code "337") (name "Net-(U170-DO)") (class "Default")
      (node (ref "U170") (pin "SDO") (pinfunction "DO_SDO") (pintype "bidirectional"))
      (node (ref "U171") (pin "SDI") (pinfunction "DI_SDI") (pintype "bidirectional"))
    )
    (net (code "338") (name "Net-(U171-CO)") (class "Default")
      (node (ref "U171") (pin "CKO") (pinfunction "CO_CKO") (pintype "bidirectional"))
      (node (ref "U172") (pin "CKI") (pinfunction "CI_CKI") (pintype "bidirectional"))
    )
    (net (code "339") (name "Net-(U171-DO)") (class "Default")
      (node (ref "U171") (pin "SDO") (pinfunction "DO_SDO") (pintype "bidirectional"))
      (node (ref "U172") (pin "SDI") (pinfunction "DI_SDI") (pintype "bidirectional"))
    )
    (net (code "340") (name "Net-(U172-CO)") (class "Default")
      (node (ref "U172") (pin "CKO") (pinfunction "CO_CKO") (pintype "bidirectional"))
      (node (ref "U173") (pin "CKI") (pinfunction "CI_CKI") (pintype "bidirectional"))
    )
    (net (code "341") (name "Net-(U172-DO)") (class "Default")
      (node (ref "U172") (pin "SDO") (pinfunction "DO_SDO") (pintype "bidirectional"))
      (node (ref "U173") (pin "SDI") (pinfunction "DI_SDI") (pintype "bidirectional"))
    )
    (net (code "342") (name "Net-(U173-CO)") (class "Default")
      (node (ref "U173") (pin "CKO") (pinfunction "CO_CKO") (pintype "bidirectional"))
      (node (ref "U174") (pin "CKI") (pinfunction "CI_CKI") (pintype "bidirectional"))
    )
    (net (code "343") (name "Net-(U173-DO)") (class "Default")
      (node (ref "U173") (pin "SDO") (pinfunction "DO_SDO") (pintype "bidirectional"))
      (node (ref "U174") (pin "SDI") (pinfunction "DI_SDI") (pintype "bidirectional"))
    )
    (net (code "344") (name "Net-(U174-CO)") (class "Default")
      (node (ref "U174") (pin "CKO") (pinfunction "CO_CKO") (pintype "bidirectional"))
      (node (ref "U175") (pin "CKI") (pinfunction "CI_CKI") (pintype "bidirectional"))
    )
    (net (code "345") (name "Net-(U174-DO)") (class "Default")
      (node (ref "U174") (pin "SDO") (pinfunction "DO_SDO") (pintype "bidirectional"))
      (node (ref "U175") (pin "SDI") (pinfunction "DI_SDI") (pintype "bidirectional"))
    )
    (net (code "346") (name "Net-(U175-CO)") (class "Default")
      (node (ref "U175") (pin "CKO") (pinfunction "CO_CKO") (pintype "bidirectional"))
      (node (ref "U176") (pin "CKI") (pinfunction "CI_CKI") (pintype "bidirectional"))
    )
    (net (code "347") (name "Net-(U175-DO)") (class "Default")
      (node (ref "U175") (pin "SDO") (pinfunction "DO_SDO") (pintype "bidirectional"))
      (node (ref "U176") (pin "SDI") (pinfunction "DI_SDI") (pintype "bidirectional"))
    )
    (net (code "348") (name "Net-(U176-CO)") (class "Default")
      (node (ref "U176") (pin "CKO") (pinfunction "CO_CKO") (pintype "bidirectional"))
      (node (ref "U177") (pin "CKI") (pinfunction "CI_CKI") (pintype "bidirectional"))
    )
    (net (code "349") (name "Net-(U176-DO)") (class "Default")
      (node (ref "U176") (pin "SDO") (pinfunction "DO_SDO") (pintype "bidirectional"))
      (node (ref "U177") (pin "SDI") (pinfunction "DI_SDI") (pintype "bidirectional"))
    )
    (net (code "350") (name "Net-(U177-CO)") (class "Default")
      (node (ref "U177") (pin "CKO") (pinfunction "CO_CKO") (pintype "bidirectional"))
      (node (ref "U178") (pin "CKI") (pinfunction "CI_CKI") (pintype "bidirectional"))
    )
    (net (code "351") (name "Net-(U177-DO)") (class "Default")
      (node (ref "U177") (pin "SDO") (pinfunction "DO_SDO") (pintype "bidirectional"))
      (node (ref "U178") (pin "SDI") (pinfunction "DI_SDI") (pintype "bidirectional"))
    )
    (net (code "352") (name "Net-(U178-CO)") (class "Default")
      (node (ref "U178") (pin "CKO") (pinfunction "CO_CKO") (pintype "bidirectional"))
      (node (ref "U179") (pin "CKI") (pinfunction "CI_CKI") (pintype "bidirectional"))
    )
    (net (code "353") (name "Net-(U178-DO)") (class "Default")
      (node (ref "U178") (pin "SDO") (pinfunction "DO_SDO") (pintype "bidirectional"))
      (node (ref "U179") (pin "SDI") (pinfunction "DI_SDI") (pintype "bidirectional"))
    )
    (net (code "354") (name "Net-(U179-CO)") (class "Default")
      (node (ref "U179") (pin "CKO") (pinfunction "CO_CKO") (pintype "bidirectional"))
      (node (ref "U180") (pin "CKI") (pinfunction "CI_CKI") (pintype "bidirectional"))
    )
    (net (code "355") (name "Net-(U179-DO)") (class "Default")
      (node (ref "U179") (pin "SDO") (pinfunction "DO_SDO") (pintype "bidirectional"))
      (node (ref "U180") (pin "SDI") (pinfunction "DI_SDI") (pintype "bidirectional"))
    )
    (net (code "356") (name "Net-(U180-CO)") (class "Default")
      (node (ref "U180") (pin "CKO") (pinfunction "CO_CKO") (pintype "bidirectional"))
      (node (ref "U181") (pin "CKI") (pinfunction "CI_CKI") (pintype "bidirectional"))
    )
    (net (code "357") (name "Net-(U180-DO)") (class "Default")
      (node (ref "U180") (pin "SDO") (pinfunction "DO_SDO") (pintype "bidirectional"))
      (node (ref "U181") (pin "SDI") (pinfunction "DI_SDI") (pintype "bidirectional"))
    )
    (net (code "358") (name "Net-(U181-CO)") (class "Default")
      (node (ref "U181") (pin "CKO") (pinfunction "CO_CKO") (pintype "bidirectional"))
      (node (ref "U182") (pin "CKI") (pinfunction "CI_CKI") (pintype "bidirectional"))
    )
    (net (code "359") (name "Net-(U181-DO)") (class "Default")
      (node (ref "U181") (pin "SDO") (pinfunction "DO_SDO") (pintype "bidirectional"))
      (node (ref "U182") (pin "SDI") (pinfunction "DI_SDI") (pintype "bidirectional"))
    )
    (net (code "360") (name "Net-(U182-CO)") (class "Default")
      (node (ref "U182") (pin "CKO") (pinfunction "CO_CKO") (pintype "bidirectional"))
      (node (ref "U183") (pin "CKI") (pinfunction "CI_CKI") (pintype "bidirectional"))
    )
    (net (code "361") (name "Net-(U182-DO)") (class "Default")
      (node (ref "U182") (pin "SDO") (pinfunction "DO_SDO") (pintype "bidirectional"))
      (node (ref "U183") (pin "SDI") (pinfunction "DI_SDI") (pintype "bidirectional"))
    )
    (net (code "362") (name "Net-(U183-CO)") (class "Default")
      (node (ref "U183") (pin "CKO") (pinfunction "CO_CKO") (pintype "bidirectional"))
      (node (ref "U184") (pin "CKI") (pinfunction "CI_CKI") (pintype "bidirectional"))
    )
    (net (code "363") (name "Net-(U183-DO)") (class "Default")
      (node (ref "U183") (pin "SDO") (pinfunction "DO_SDO") (pintype "bidirectional"))
      (node (ref "U184") (pin "SDI") (pinfunction "DI_SDI") (pintype "bidirectional"))
    )
    (net (code "364") (name "Net-(U184-CO)") (class "Default")
      (node (ref "U184") (pin "CKO") (pinfunction "CO_CKO") (pintype "bidirectional"))
      (node (ref "U185") (pin "CKI") (pinfunction "CI_CKI") (pintype "bidirectional"))
    )
    (net (code "365") (name "Net-(U184-DO)") (class "Default")
      (node (ref "U184") (pin "SDO") (pinfunction "DO_SDO") (pintype "bidirectional"))
      (node (ref "U185") (pin "SDI") (pinfunction "DI_SDI") (pintype "bidirectional"))
    )
    (net (code "366") (name "Net-(U185-CO)") (class "Default")
      (node (ref "U185") (pin "CKO") (pinfunction "CO_CKO") (pintype "bidirectional"))
      (node (ref "U186") (pin "CKI") (pinfunction "CI_CKI") (pintype "bidirectional"))
    )
    (net (code "367") (name "Net-(U185-DO)") (class "Default")
      (node (ref "U185") (pin "SDO") (pinfunction "DO_SDO") (pintype "bidirectional"))
      (node (ref "U186") (pin "SDI") (pinfunction "DI_SDI") (pintype "bidirectional"))
    )
    (net (code "368") (name "Net-(U186-CO)") (class "Default")
      (node (ref "U186") (pin "CKO") (pinfunction "CO_CKO") (pintype "bidirectional"))
      (node (ref "U187") (pin "CKI") (pinfunction "CI_CKI") (pintype "bidirectional"))
    )
    (net (code "369") (name "Net-(U186-DO)") (class "Default")
      (node (ref "U186") (pin "SDO") (pinfunction "DO_SDO") (pintype "bidirectional"))
      (node (ref "U187") (pin "SDI") (pinfunction "DI_SDI") (pintype "bidirectional"))
    )
    (net (code "370") (name "Net-(U187-CO)") (class "Default")
      (node (ref "U187") (pin "CKO") (pinfunction "CO_CKO") (pintype "bidirectional"))
      (node (ref "U188") (pin "CKI") (pinfunction "CI_CKI") (pintype "bidirectional"))
    )
    (net (code "371") (name "Net-(U187-DO)") (class "Default")
      (node (ref "U187") (pin "SDO") (pinfunction "DO_SDO") (pintype "bidirectional"))
      (node (ref "U188") (pin "SDI") (pinfunction "DI_SDI") (pintype "bidirectional"))
    )
    (net (code "372") (name "Net-(U188-CO)") (class "Default")
      (node (ref "U188") (pin "CKO") (pinfunction "CO_CKO") (pintype "bidirectional"))
      (node (ref "U189") (pin "CKI") (pinfunction "CI_CKI") (pintype "bidirectional"))
    )
    (net (code "373") (name "Net-(U188-DO)") (class "Default")
      (node (ref "U188") (pin "SDO") (pinfunction "DO_SDO") (pintype "bidirectional"))
      (node (ref "U189") (pin "SDI") (pinfunction "DI_SDI") (pintype "bidirectional"))
    )
    (net (code "374") (name "Net-(U189-CO)") (class "Default")
      (node (ref "U189") (pin "CKO") (pinfunction "CO_CKO") (pintype "bidirectional"))
      (node (ref "U190") (pin "CKI") (pinfunction "CI_CKI") (pintype "bidirectional"))
    )
    (net (code "375") (name "Net-(U189-DO)") (class "Default")
      (node (ref "U189") (pin "SDO") (pinfunction "DO_SDO") (pintype "bidirectional"))
      (node (ref "U190") (pin "SDI") (pinfunction "DI_SDI") (pintype "bidirectional"))
    )
    (net (code "376") (name "Net-(U190-CO)") (class "Default")
      (node (ref "U190") (pin "CKO") (pinfunction "CO_CKO") (pintype "bidirectional"))
      (node (ref "U191") (pin "CKI") (pinfunction "CI_CKI") (pintype "bidirectional"))
    )
    (net (code "377") (name "Net-(U190-DO)") (class "Default")
      (node (ref "U190") (pin "SDO") (pinfunction "DO_SDO") (pintype "bidirectional"))
      (node (ref "U191") (pin "SDI") (pinfunction "DI_SDI") (pintype "bidirectional"))
    )
    (net (code "378") (name "Net-(U191-CO)") (class "Default")
      (node (ref "U191") (pin "CKO") (pinfunction "CO_CKO") (pintype "bidirectional"))
      (node (ref "U192") (pin "CKI") (pinfunction "CI_CKI") (pintype "bidirectional"))
    )
    (net (code "379") (name "Net-(U191-DO)") (class "Default")
      (node (ref "U191") (pin "SDO") (pinfunction "DO_SDO") (pintype "bidirectional"))
      (node (ref "U192") (pin "SDI") (pinfunction "DI_SDI") (pintype "bidirectional"))
    )
    (net (code "380") (name "Net-(U192-CO)") (class "Default")
      (node (ref "U192") (pin "CKO") (pinfunction "CO_CKO") (pintype "bidirectional"))
      (node (ref "U193") (pin "CKI") (pinfunction "CI_CKI") (pintype "bidirectional"))
    )
    (net (code "381") (name "Net-(U192-DO)") (class "Default")
      (node (ref "U192") (pin "SDO") (pinfunction "DO_SDO") (pintype "bidirectional"))
      (node (ref "U193") (pin "SDI") (pinfunction "DI_SDI") (pintype "bidirectional"))
    )
    (net (code "382") (name "Net-(U193-CO)") (class "Default")
      (node (ref "U193") (pin "CKO") (pinfunction "CO_CKO") (pintype "bidirectional"))
      (node (ref "U194") (pin "CKI") (pinfunction "CI_CKI") (pintype "bidirectional"))
    )
    (net (code "383") (name "Net-(U193-DO)") (class "Default")
      (node (ref "U193") (pin "SDO") (pinfunction "DO_SDO") (pintype "bidirectional"))
      (node (ref "U194") (pin "SDI") (pinfunction "DI_SDI") (pintype "bidirectional"))
    )
    (net (code "384") (name "Net-(U194-CO)") (class "Default")
      (node (ref "U194") (pin "CKO") (pinfunction "CO_CKO") (pintype "bidirectional"))
      (node (ref "U195") (pin "CKI") (pinfunction "CI_CKI") (pintype "bidirectional"))
    )
    (net (code "385") (name "Net-(U194-DO)") (class "Default")
      (node (ref "U194") (pin "SDO") (pinfunction "DO_SDO") (pintype "bidirectional"))
      (node (ref "U195") (pin "SDI") (pinfunction "DI_SDI") (pintype "bidirectional"))
    )
    (net (code "386") (name "Net-(U195-CO)") (class "Default")
      (node (ref "U195") (pin "CKO") (pinfunction "CO_CKO") (pintype "bidirectional"))
      (node (ref "U196") (pin "CKI") (pinfunction "CI_CKI") (pintype "bidirectional"))
    )
    (net (code "387") (name "Net-(U195-DO)") (class "Default")
      (node (ref "U195") (pin "SDO") (pinfunction "DO_SDO") (pintype "bidirectional"))
      (node (ref "U196") (pin "SDI") (pinfunction "DI_SDI") (pintype "bidirectional"))
    )
    (net (code "388") (name "Net-(U197-CO)") (class "Default")
      (node (ref "U197") (pin "CKO") (pinfunction "CO_CKO") (pintype "bidirectional"))
      (node (ref "U198") (pin "CKI") (pinfunction "CI_CKI") (pintype "bidirectional"))
    )
    (net (code "389") (name "Net-(U197-DO)") (class "Default")
      (node (ref "U197") (pin "SDO") (pinfunction "DO_SDO") (pintype "bidirectional"))
      (node (ref "U198") (pin "SDI") (pinfunction "DI_SDI") (pintype "bidirectional"))
    )
    (net (code "390") (name "Net-(U198-CO)") (class "Default")
      (node (ref "U198") (pin "CKO") (pinfunction "CO_CKO") (pintype "bidirectional"))
      (node (ref "U199") (pin "CKI") (pinfunction "CI_CKI") (pintype "bidirectional"))
    )
    (net (code "391") (name "Net-(U198-DO)") (class "Default")
      (node (ref "U198") (pin "SDO") (pinfunction "DO_SDO") (pintype "bidirectional"))
      (node (ref "U199") (pin "SDI") (pinfunction "DI_SDI") (pintype "bidirectional"))
    )
    (net (code "392") (name "Net-(U199-CO)") (class "Default")
      (node (ref "U199") (pin "CKO") (pinfunction "CO_CKO") (pintype "bidirectional"))
      (node (ref "U200") (pin "CKI") (pinfunction "CI_CKI") (pintype "bidirectional"))
    )
    (net (code "393") (name "Net-(U199-DO)") (class "Default")
      (node (ref "U199") (pin "SDO") (pinfunction "DO_SDO") (pintype "bidirectional"))
      (node (ref "U200") (pin "SDI") (pinfunction "DI_SDI") (pintype "bidirectional"))
    )
    (net (code "394") (name "Net-(U200-CO)") (class "Default")
      (node (ref "U200") (pin "CKO") (pinfunction "CO_CKO") (pintype "bidirectional"))
      (node (ref "U201") (pin "CKI") (pinfunction "CI_CKI") (pintype "bidirectional"))
    )
    (net (code "395") (name "Net-(U200-DO)") (class "Default")
      (node (ref "U200") (pin "SDO") (pinfunction "DO_SDO") (pintype "bidirectional"))
      (node (ref "U201") (pin "SDI") (pinfunction "DI_SDI") (pintype "bidirectional"))
    )
    (net (code "396") (name "Net-(U201-CO)") (class "Default")
      (node (ref "U201") (pin "CKO") (pinfunction "CO_CKO") (pintype "bidirectional"))
      (node (ref "U202") (pin "CKI") (pinfunction "CI_CKI") (pintype "bidirectional"))
    )
    (net (code "397") (name "Net-(U201-DO)") (class "Default")
      (node (ref "U201") (pin "SDO") (pinfunction "DO_SDO") (pintype "bidirectional"))
      (node (ref "U202") (pin "SDI") (pinfunction "DI_SDI") (pintype "bidirectional"))
    )
    (net (code "398") (name "Net-(U202-CO)") (class "Default")
      (node (ref "U202") (pin "CKO") (pinfunction "CO_CKO") (pintype "bidirectional"))
      (node (ref "U203") (pin "CKI") (pinfunction "CI_CKI") (pintype "bidirectional"))
    )
    (net (code "399") (name "Net-(U202-DO)") (class "Default")
      (node (ref "U202") (pin "SDO") (pinfunction "DO_SDO") (pintype "bidirectional"))
      (node (ref "U203") (pin "SDI") (pinfunction "DI_SDI") (pintype "bidirectional"))
    )
    (net (code "400") (name "Net-(U203-CO)") (class "Default")
      (node (ref "U203") (pin "CKO") (pinfunction "CO_CKO") (pintype "bidirectional"))
      (node (ref "U204") (pin "CKI") (pinfunction "CI_CKI") (pintype "bidirectional"))
    )
    (net (code "401") (name "Net-(U203-DO)") (class "Default")
      (node (ref "U203") (pin "SDO") (pinfunction "DO_SDO") (pintype "bidirectional"))
      (node (ref "U204") (pin "SDI") (pinfunction "DI_SDI") (pintype "bidirectional"))
    )
    (net (code "402") (name "Net-(U204-CO)") (class "Default")
      (node (ref "U204") (pin "CKO") (pinfunction "CO_CKO") (pintype "bidirectional"))
      (node (ref "U205") (pin "CKI") (pinfunction "CI_CKI") (pintype "bidirectional"))
    )
    (net (code "403") (name "Net-(U204-DO)") (class "Default")
      (node (ref "U204") (pin "SDO") (pinfunction "DO_SDO") (pintype "bidirectional"))
      (node (ref "U205") (pin "SDI") (pinfunction "DI_SDI") (pintype "bidirectional"))
    )
    (net (code "404") (name "Net-(U205-CO)") (class "Default")
      (node (ref "U205") (pin "CKO") (pinfunction "CO_CKO") (pintype "bidirectional"))
      (node (ref "U206") (pin "CKI") (pinfunction "CI_CKI") (pintype "bidirectional"))
    )
    (net (code "405") (name "Net-(U205-DO)") (class "Default")
      (node (ref "U205") (pin "SDO") (pinfunction "DO_SDO") (pintype "bidirectional"))
      (node (ref "U206") (pin "SDI") (pinfunction "DI_SDI") (pintype "bidirectional"))
    )
    (net (code "406") (name "Net-(U206-CO)") (class "Default")
      (node (ref "U206") (pin "CKO") (pinfunction "CO_CKO") (pintype "bidirectional"))
      (node (ref "U207") (pin "CKI") (pinfunction "CI_CKI") (pintype "bidirectional"))
    )
    (net (code "407") (name "Net-(U206-DO)") (class "Default")
      (node (ref "U206") (pin "SDO") (pinfunction "DO_SDO") (pintype "bidirectional"))
      (node (ref "U207") (pin "SDI") (pinfunction "DI_SDI") (pintype "bidirectional"))
    )
    (net (code "408") (name "Net-(U207-CO)") (class "Default")
      (node (ref "U207") (pin "CKO") (pinfunction "CO_CKO") (pintype "bidirectional"))
      (node (ref "U208") (pin "CKI") (pinfunction "CI_CKI") (pintype "bidirectional"))
    )
    (net (code "409") (name "Net-(U207-DO)") (class "Default")
      (node (ref "U207") (pin "SDO") (pinfunction "DO_SDO") (pintype "bidirectional"))
      (node (ref "U208") (pin "SDI") (pinfunction "DI_SDI") (pintype "bidirectional"))
    )
    (net (code "410") (name "Net-(U208-CO)") (class "Default")
      (node (ref "U208") (pin "CKO") (pinfunction "CO_CKO") (pintype "bidirectional"))
      (node (ref "U209") (pin "CKI") (pinfunction "CI_CKI") (pintype "bidirectional"))
    )
    (net (code "411") (name "Net-(U208-DO)") (class "Default")
      (node (ref "U208") (pin "SDO") (pinfunction "DO_SDO") (pintype "bidirectional"))
      (node (ref "U209") (pin "SDI") (pinfunction "DI_SDI") (pintype "bidirectional"))
    )
    (net (code "412") (name "Net-(U209-CO)") (class "Default")
      (node (ref "U209") (pin "CKO") (pinfunction "CO_CKO") (pintype "bidirectional"))
      (node (ref "U210") (pin "CKI") (pinfunction "CI_CKI") (pintype "bidirectional"))
    )
    (net (code "413") (name "Net-(U209-DO)") (class "Default")
      (node (ref "U209") (pin "SDO") (pinfunction "DO_SDO") (pintype "bidirectional"))
      (node (ref "U210") (pin "SDI") (pinfunction "DI_SDI") (pintype "bidirectional"))
    )
    (net (code "414") (name "Net-(U210-CO)") (class "Default")
      (node (ref "U210") (pin "CKO") (pinfunction "CO_CKO") (pintype "bidirectional"))
      (node (ref "U211") (pin "CKI") (pinfunction "CI_CKI") (pintype "bidirectional"))
    )
    (net (code "415") (name "Net-(U210-DO)") (class "Default")
      (node (ref "U210") (pin "SDO") (pinfunction "DO_SDO") (pintype "bidirectional"))
      (node (ref "U211") (pin "SDI") (pinfunction "DI_SDI") (pintype "bidirectional"))
    )
    (net (code "416") (name "Net-(U211-CO)") (class "Default")
      (node (ref "U211") (pin "CKO") (pinfunction "CO_CKO") (pintype "bidirectional"))
      (node (ref "U212") (pin "CKI") (pinfunction "CI_CKI") (pintype "bidirectional"))
    )
    (net (code "417") (name "Net-(U211-DO)") (class "Default")
      (node (ref "U211") (pin "SDO") (pinfunction "DO_SDO") (pintype "bidirectional"))
      (node (ref "U212") (pin "SDI") (pinfunction "DI_SDI") (pintype "bidirectional"))
    )
    (net (code "418") (name "Net-(U212-CO)") (class "Default")
      (node (ref "U212") (pin "CKO") (pinfunction "CO_CKO") (pintype "bidirectional"))
      (node (ref "U213") (pin "CKI") (pinfunction "CI_CKI") (pintype "bidirectional"))
    )
    (net (code "419") (name "Net-(U212-DO)") (class "Default")
      (node (ref "U212") (pin "SDO") (pinfunction "DO_SDO") (pintype "bidirectional"))
      (node (ref "U213") (pin "SDI") (pinfunction "DI_SDI") (pintype "bidirectional"))
    )
    (net (code "420") (name "Net-(U213-CO)") (class "Default")
      (node (ref "U213") (pin "CKO") (pinfunction "CO_CKO") (pintype "bidirectional"))
      (node (ref "U214") (pin "CKI") (pinfunction "CI_CKI") (pintype "bidirectional"))
    )
    (net (code "421") (name "Net-(U213-DO)") (class "Default")
      (node (ref "U213") (pin "SDO") (pinfunction "DO_SDO") (pintype "bidirectional"))
      (node (ref "U214") (pin "SDI") (pinfunction "DI_SDI") (pintype "bidirectional"))
    )
    (net (code "422") (name "Net-(U214-CO)") (class "Default")
      (node (ref "U214") (pin "CKO") (pinfunction "CO_CKO") (pintype "bidirectional"))
      (node (ref "U215") (pin "CKI") (pinfunction "CI_CKI") (pintype "bidirectional"))
    )
    (net (code "423") (name "Net-(U214-DO)") (class "Default")
      (node (ref "U214") (pin "SDO") (pinfunction "DO_SDO") (pintype "bidirectional"))
      (node (ref "U215") (pin "SDI") (pinfunction "DI_SDI") (pintype "bidirectional"))
    )
    (net (code "424") (name "Net-(U215-CO)") (class "Default")
      (node (ref "U215") (pin "CKO") (pinfunction "CO_CKO") (pintype "bidirectional"))
      (node (ref "U216") (pin "CKI") (pinfunction "CI_CKI") (pintype "bidirectional"))
    )
    (net (code "425") (name "Net-(U215-DO)") (class "Default")
      (node (ref "U215") (pin "SDO") (pinfunction "DO_SDO") (pintype "bidirectional"))
      (node (ref "U216") (pin "SDI") (pinfunction "DI_SDI") (pintype "bidirectional"))
    )
    (net (code "426") (name "Net-(U216-CO)") (class "Default")
      (node (ref "U216") (pin "CKO") (pinfunction "CO_CKO") (pintype "bidirectional"))
      (node (ref "U217") (pin "CKI") (pinfunction "CI_CKI") (pintype "bidirectional"))
    )
    (net (code "427") (name "Net-(U216-DO)") (class "Default")
      (node (ref "U216") (pin "SDO") (pinfunction "DO_SDO") (pintype "bidirectional"))
      (node (ref "U217") (pin "SDI") (pinfunction "DI_SDI") (pintype "bidirectional"))
    )
    (net (code "428") (name "Net-(U217-CO)") (class "Default")
      (node (ref "U217") (pin "CKO") (pinfunction "CO_CKO") (pintype "bidirectional"))
      (node (ref "U218") (pin "CKI") (pinfunction "CI_CKI") (pintype "bidirectional"))
    )
    (net (code "429") (name "Net-(U217-DO)") (class "Default")
      (node (ref "U217") (pin "SDO") (pinfunction "DO_SDO") (pintype "bidirectional"))
      (node (ref "U218") (pin "SDI") (pinfunction "DI_SDI") (pintype "bidirectional"))
    )
    (net (code "430") (name "Net-(U218-CO)") (class "Default")
      (node (ref "U218") (pin "CKO") (pinfunction "CO_CKO") (pintype "bidirectional"))
      (node (ref "U219") (pin "CKI") (pinfunction "CI_CKI") (pintype "bidirectional"))
    )
    (net (code "431") (name "Net-(U218-DO)") (class "Default")
      (node (ref "U218") (pin "SDO") (pinfunction "DO_SDO") (pintype "bidirectional"))
      (node (ref "U219") (pin "SDI") (pinfunction "DI_SDI") (pintype "bidirectional"))
    )
    (net (code "432") (name "Net-(U219-CO)") (class "Default")
      (node (ref "U219") (pin "CKO") (pinfunction "CO_CKO") (pintype "bidirectional"))
      (node (ref "U220") (pin "CKI") (pinfunction "CI_CKI") (pintype "bidirectional"))
    )
    (net (code "433") (name "Net-(U219-DO)") (class "Default")
      (node (ref "U219") (pin "SDO") (pinfunction "DO_SDO") (pintype "bidirectional"))
      (node (ref "U220") (pin "SDI") (pinfunction "DI_SDI") (pintype "bidirectional"))
    )
    (net (code "434") (name "Net-(U220-CO)") (class "Default")
      (node (ref "U220") (pin "CKO") (pinfunction "CO_CKO") (pintype "bidirectional"))
      (node (ref "U221") (pin "CKI") (pinfunction "CI_CKI") (pintype "bidirectional"))
    )
    (net (code "435") (name "Net-(U220-DO)") (class "Default")
      (node (ref "U220") (pin "SDO") (pinfunction "DO_SDO") (pintype "bidirectional"))
      (node (ref "U221") (pin "SDI") (pinfunction "DI_SDI") (pintype "bidirectional"))
    )
    (net (code "436") (name "Net-(U221-CO)") (class "Default")
      (node (ref "U221") (pin "CKO") (pinfunction "CO_CKO") (pintype "bidirectional"))
      (node (ref "U222") (pin "CKI") (pinfunction "CI_CKI") (pintype "bidirectional"))
    )
    (net (code "437") (name "Net-(U221-DO)") (class "Default")
      (node (ref "U221") (pin "SDO") (pinfunction "DO_SDO") (pintype "bidirectional"))
      (node (ref "U222") (pin "SDI") (pinfunction "DI_SDI") (pintype "bidirectional"))
    )
    (net (code "438") (name "Net-(U222-CO)") (class "Default")
      (node (ref "U222") (pin "CKO") (pinfunction "CO_CKO") (pintype "bidirectional"))
      (node (ref "U223") (pin "CKI") (pinfunction "CI_CKI") (pintype "bidirectional"))
    )
    (net (code "439") (name "Net-(U222-DO)") (class "Default")
      (node (ref "U222") (pin "SDO") (pinfunction "DO_SDO") (pintype "bidirectional"))
      (node (ref "U223") (pin "SDI") (pinfunction "DI_SDI") (pintype "bidirectional"))
    )
    (net (code "440") (name "Net-(U223-CO)") (class "Default")
      (node (ref "U223") (pin "CKO") (pinfunction "CO_CKO") (pintype "bidirectional"))
      (node (ref "U224") (pin "CKI") (pinfunction "CI_CKI") (pintype "bidirectional"))
    )
    (net (code "441") (name "Net-(U223-DO)") (class "Default")
      (node (ref "U223") (pin "SDO") (pinfunction "DO_SDO") (pintype "bidirectional"))
      (node (ref "U224") (pin "SDI") (pinfunction "DI_SDI") (pintype "bidirectional"))
    )
    (net (code "442") (name "Net-(U225-CO)") (class "Default")
      (node (ref "U225") (pin "CKO") (pinfunction "CO_CKO") (pintype "bidirectional"))
      (node (ref "U226") (pin "CKI") (pinfunction "CI_CKI") (pintype "bidirectional"))
    )
    (net (code "443") (name "Net-(U225-DO)") (class "Default")
      (node (ref "U225") (pin "SDO") (pinfunction "DO_SDO") (pintype "bidirectional"))
      (node (ref "U226") (pin "SDI") (pinfunction "DI_SDI") (pintype "bidirectional"))
    )
    (net (code "444") (name "Net-(U226-CO)") (class "Default")
      (node (ref "U226") (pin "CKO") (pinfunction "CO_CKO") (pintype "bidirectional"))
      (node (ref "U227") (pin "CKI") (pinfunction "CI_CKI") (pintype "bidirectional"))
    )
    (net (code "445") (name "Net-(U226-DO)") (class "Default")
      (node (ref "U226") (pin "SDO") (pinfunction "DO_SDO") (pintype "bidirectional"))
      (node (ref "U227") (pin "SDI") (pinfunction "DI_SDI") (pintype "bidirectional"))
    )
    (net (code "446") (name "Net-(U227-CO)") (class "Default")
      (node (ref "U227") (pin "CKO") (pinfunction "CO_CKO") (pintype "bidirectional"))
      (node (ref "U228") (pin "CKI") (pinfunction "CI_CKI") (pintype "bidirectional"))
    )
    (net (code "447") (name "Net-(U227-DO)") (class "Default")
      (node (ref "U227") (pin "SDO") (pinfunction "DO_SDO") (pintype "bidirectional"))
      (node (ref "U228") (pin "SDI") (pinfunction "DI_SDI") (pintype "bidirectional"))
    )
    (net (code "448") (name "Net-(U228-CO)") (class "Default")
      (node (ref "U228") (pin "CKO") (pinfunction "CO_CKO") (pintype "bidirectional"))
      (node (ref "U229") (pin "CKI") (pinfunction "CI_CKI") (pintype "bidirectional"))
    )
    (net (code "449") (name "Net-(U228-DO)") (class "Default")
      (node (ref "U228") (pin "SDO") (pinfunction "DO_SDO") (pintype "bidirectional"))
      (node (ref "U229") (pin "SDI") (pinfunction "DI_SDI") (pintype "bidirectional"))
    )
    (net (code "450") (name "Net-(U229-CO)") (class "Default")
      (node (ref "U229") (pin "CKO") (pinfunction "CO_CKO") (pintype "bidirectional"))
      (node (ref "U230") (pin "CKI") (pinfunction "CI_CKI") (pintype "bidirectional"))
    )
    (net (code "451") (name "Net-(U229-DO)") (class "Default")
      (node (ref "U229") (pin "SDO") (pinfunction "DO_SDO") (pintype "bidirectional"))
      (node (ref "U230") (pin "SDI") (pinfunction "DI_SDI") (pintype "bidirectional"))
    )
    (net (code "452") (name "Net-(U230-CO)") (class "Default")
      (node (ref "U230") (pin "CKO") (pinfunction "CO_CKO") (pintype "bidirectional"))
      (node (ref "U231") (pin "CKI") (pinfunction "CI_CKI") (pintype "bidirectional"))
    )
    (net (code "453") (name "Net-(U230-DO)") (class "Default")
      (node (ref "U230") (pin "SDO") (pinfunction "DO_SDO") (pintype "bidirectional"))
      (node (ref "U231") (pin "SDI") (pinfunction "DI_SDI") (pintype "bidirectional"))
    )
    (net (code "454") (name "Net-(U231-CO)") (class "Default")
      (node (ref "U231") (pin "CKO") (pinfunction "CO_CKO") (pintype "bidirectional"))
      (node (ref "U232") (pin "CKI") (pinfunction "CI_CKI") (pintype "bidirectional"))
    )
    (net (code "455") (name "Net-(U231-DO)") (class "Default")
      (node (ref "U231") (pin "SDO") (pinfunction "DO_SDO") (pintype "bidirectional"))
      (node (ref "U232") (pin "SDI") (pinfunction "DI_SDI") (pintype "bidirectional"))
    )
    (net (code "456") (name "Net-(U232-CO)") (class "Default")
      (node (ref "U232") (pin "CKO") (pinfunction "CO_CKO") (pintype "bidirectional"))
      (node (ref "U233") (pin "CKI") (pinfunction "CI_CKI") (pintype "bidirectional"))
    )
    (net (code "457") (name "Net-(U232-DO)") (class "Default")
      (node (ref "U232") (pin "SDO") (pinfunction "DO_SDO") (pintype "bidirectional"))
      (node (ref "U233") (pin "SDI") (pinfunction "DI_SDI") (pintype "bidirectional"))
    )
    (net (code "458") (name "Net-(U233-CO)") (class "Default")
      (node (ref "U233") (pin "CKO") (pinfunction "CO_CKO") (pintype "bidirectional"))
      (node (ref "U234") (pin "CKI") (pinfunction "CI_CKI") (pintype "bidirectional"))
    )
    (net (code "459") (name "Net-(U233-DO)") (class "Default")
      (node (ref "U233") (pin "SDO") (pinfunction "DO_SDO") (pintype "bidirectional"))
      (node (ref "U234") (pin "SDI") (pinfunction "DI_SDI") (pintype "bidirectional"))
    )
    (net (code "460") (name "Net-(U234-CO)") (class "Default")
      (node (ref "U234") (pin "CKO") (pinfunction "CO_CKO") (pintype "bidirectional"))
      (node (ref "U235") (pin "CKI") (pinfunction "CI_CKI") (pintype "bidirectional"))
    )
    (net (code "461") (name "Net-(U234-DO)") (class "Default")
      (node (ref "U234") (pin "SDO") (pinfunction "DO_SDO") (pintype "bidirectional"))
      (node (ref "U235") (pin "SDI") (pinfunction "DI_SDI") (pintype "bidirectional"))
    )
    (net (code "462") (name "Net-(U235-CO)") (class "Default")
      (node (ref "U235") (pin "CKO") (pinfunction "CO_CKO") (pintype "bidirectional"))
      (node (ref "U236") (pin "CKI") (pinfunction "CI_CKI") (pintype "bidirectional"))
    )
    (net (code "463") (name "Net-(U235-DO)") (class "Default")
      (node (ref "U235") (pin "SDO") (pinfunction "DO_SDO") (pintype "bidirectional"))
      (node (ref "U236") (pin "SDI") (pinfunction "DI_SDI") (pintype "bidirectional"))
    )
    (net (code "464") (name "Net-(U236-CO)") (class "Default")
      (node (ref "U236") (pin "CKO") (pinfunction "CO_CKO") (pintype "bidirectional"))
      (node (ref "U237") (pin "CKI") (pinfunction "CI_CKI") (pintype "bidirectional"))
    )
    (net (code "465") (name "Net-(U236-DO)") (class "Default")
      (node (ref "U236") (pin "SDO") (pinfunction "DO_SDO") (pintype "bidirectional"))
      (node (ref "U237") (pin "SDI") (pinfunction "DI_SDI") (pintype "bidirectional"))
    )
    (net (code "466") (name "Net-(U237-CO)") (class "Default")
      (node (ref "U237") (pin "CKO") (pinfunction "CO_CKO") (pintype "bidirectional"))
      (node (ref "U238") (pin "CKI") (pinfunction "CI_CKI") (pintype "bidirectional"))
    )
    (net (code "467") (name "Net-(U237-DO)") (class "Default")
      (node (ref "U237") (pin "SDO") (pinfunction "DO_SDO") (pintype "bidirectional"))
      (node (ref "U238") (pin "SDI") (pinfunction "DI_SDI") (pintype "bidirectional"))
    )
    (net (code "468") (name "Net-(U238-CO)") (class "Default")
      (node (ref "U238") (pin "CKO") (pinfunction "CO_CKO") (pintype "bidirectional"))
      (node (ref "U239") (pin "CKI") (pinfunction "CI_CKI") (pintype "bidirectional"))
    )
    (net (code "469") (name "Net-(U238-DO)") (class "Default")
      (node (ref "U238") (pin "SDO") (pinfunction "DO_SDO") (pintype "bidirectional"))
      (node (ref "U239") (pin "SDI") (pinfunction "DI_SDI") (pintype "bidirectional"))
    )
    (net (code "470") (name "Net-(U239-CO)") (class "Default")
      (node (ref "U239") (pin "CKO") (pinfunction "CO_CKO") (pintype "bidirectional"))
      (node (ref "U240") (pin "CKI") (pinfunction "CI_CKI") (pintype "bidirectional"))
    )
    (net (code "471") (name "Net-(U239-DO)") (class "Default")
      (node (ref "U239") (pin "SDO") (pinfunction "DO_SDO") (pintype "bidirectional"))
      (node (ref "U240") (pin "SDI") (pinfunction "DI_SDI") (pintype "bidirectional"))
    )
    (net (code "472") (name "Net-(U240-CO)") (class "Default")
      (node (ref "U240") (pin "CKO") (pinfunction "CO_CKO") (pintype "bidirectional"))
      (node (ref "U241") (pin "CKI") (pinfunction "CI_CKI") (pintype "bidirectional"))
    )
    (net (code "473") (name "Net-(U240-DO)") (class "Default")
      (node (ref "U240") (pin "SDO") (pinfunction "DO_SDO") (pintype "bidirectional"))
      (node (ref "U241") (pin "SDI") (pinfunction "DI_SDI") (pintype "bidirectional"))
    )
    (net (code "474") (name "Net-(U241-CO)") (class "Default")
      (node (ref "U241") (pin "CKO") (pinfunction "CO_CKO") (pintype "bidirectional"))
      (node (ref "U242") (pin "CKI") (pinfunction "CI_CKI") (pintype "bidirectional"))
    )
    (net (code "475") (name "Net-(U241-DO)") (class "Default")
      (node (ref "U241") (pin "SDO") (pinfunction "DO_SDO") (pintype "bidirectional"))
      (node (ref "U242") (pin "SDI") (pinfunction "DI_SDI") (pintype "bidirectional"))
    )
    (net (code "476") (name "Net-(U242-CO)") (class "Default")
      (node (ref "U242") (pin "CKO") (pinfunction "CO_CKO") (pintype "bidirectional"))
      (node (ref "U243") (pin "CKI") (pinfunction "CI_CKI") (pintype "bidirectional"))
    )
    (net (code "477") (name "Net-(U242-DO)") (class "Default")
      (node (ref "U242") (pin "SDO") (pinfunction "DO_SDO") (pintype "bidirectional"))
      (node (ref "U243") (pin "SDI") (pinfunction "DI_SDI") (pintype "bidirectional"))
    )
    (net (code "478") (name "Net-(U243-CO)") (class "Default")
      (node (ref "U243") (pin "CKO") (pinfunction "CO_CKO") (pintype "bidirectional"))
      (node (ref "U244") (pin "CKI") (pinfunction "CI_CKI") (pintype "bidirectional"))
    )
    (net (code "479") (name "Net-(U243-DO)") (class "Default")
      (node (ref "U243") (pin "SDO") (pinfunction "DO_SDO") (pintype "bidirectional"))
      (node (ref "U244") (pin "SDI") (pinfunction "DI_SDI") (pintype "bidirectional"))
    )
    (net (code "480") (name "Net-(U244-CO)") (class "Default")
      (node (ref "U244") (pin "CKO") (pinfunction "CO_CKO") (pintype "bidirectional"))
      (node (ref "U245") (pin "CKI") (pinfunction "CI_CKI") (pintype "bidirectional"))
    )
    (net (code "481") (name "Net-(U244-DO)") (class "Default")
      (node (ref "U244") (pin "SDO") (pinfunction "DO_SDO") (pintype "bidirectional"))
      (node (ref "U245") (pin "SDI") (pinfunction "DI_SDI") (pintype "bidirectional"))
    )
    (net (code "482") (name "Net-(U245-CO)") (class "Default")
      (node (ref "U245") (pin "CKO") (pinfunction "CO_CKO") (pintype "bidirectional"))
      (node (ref "U246") (pin "CKI") (pinfunction "CI_CKI") (pintype "bidirectional"))
    )
    (net (code "483") (name "Net-(U245-DO)") (class "Default")
      (node (ref "U245") (pin "SDO") (pinfunction "DO_SDO") (pintype "bidirectional"))
      (node (ref "U246") (pin "SDI") (pinfunction "DI_SDI") (pintype "bidirectional"))
    )
    (net (code "484") (name "Net-(U246-CO)") (class "Default")
      (node (ref "U246") (pin "CKO") (pinfunction "CO_CKO") (pintype "bidirectional"))
      (node (ref "U247") (pin "CKI") (pinfunction "CI_CKI") (pintype "bidirectional"))
    )
    (net (code "485") (name "Net-(U246-DO)") (class "Default")
      (node (ref "U246") (pin "SDO") (pinfunction "DO_SDO") (pintype "bidirectional"))
      (node (ref "U247") (pin "SDI") (pinfunction "DI_SDI") (pintype "bidirectional"))
    )
    (net (code "486") (name "Net-(U247-CO)") (class "Default")
      (node (ref "U247") (pin "CKO") (pinfunction "CO_CKO") (pintype "bidirectional"))
      (node (ref "U248") (pin "CKI") (pinfunction "CI_CKI") (pintype "bidirectional"))
    )
    (net (code "487") (name "Net-(U247-DO)") (class "Default")
      (node (ref "U247") (pin "SDO") (pinfunction "DO_SDO") (pintype "bidirectional"))
      (node (ref "U248") (pin "SDI") (pinfunction "DI_SDI") (pintype "bidirectional"))
    )
    (net (code "488") (name "Net-(U248-CO)") (class "Default")
      (node (ref "U248") (pin "CKO") (pinfunction "CO_CKO") (pintype "bidirectional"))
      (node (ref "U249") (pin "CKI") (pinfunction "CI_CKI") (pintype "bidirectional"))
    )
    (net (code "489") (name "Net-(U248-DO)") (class "Default")
      (node (ref "U248") (pin "SDO") (pinfunction "DO_SDO") (pintype "bidirectional"))
      (node (ref "U249") (pin "SDI") (pinfunction "DI_SDI") (pintype "bidirectional"))
    )
    (net (code "490") (name "Net-(U249-CO)") (class "Default")
      (node (ref "U249") (pin "CKO") (pinfunction "CO_CKO") (pintype "bidirectional"))
      (node (ref "U250") (pin "CKI") (pinfunction "CI_CKI") (pintype "bidirectional"))
    )
    (net (code "491") (name "Net-(U249-DO)") (class "Default")
      (node (ref "U249") (pin "SDO") (pinfunction "DO_SDO") (pintype "bidirectional"))
      (node (ref "U250") (pin "SDI") (pinfunction "DI_SDI") (pintype "bidirectional"))
    )
    (net (code "492") (name "Net-(U250-CO)") (class "Default")
      (node (ref "U250") (pin "CKO") (pinfunction "CO_CKO") (pintype "bidirectional"))
      (node (ref "U251") (pin "CKI") (pinfunction "CI_CKI") (pintype "bidirectional"))
    )
    (net (code "493") (name "Net-(U250-DO)") (class "Default")
      (node (ref "U250") (pin "SDO") (pinfunction "DO_SDO") (pintype "bidirectional"))
      (node (ref "U251") (pin "SDI") (pinfunction "DI_SDI") (pintype "bidirectional"))
    )
    (net (code "494") (name "Net-(U251-CO)") (class "Default")
      (node (ref "U251") (pin "CKO") (pinfunction "CO_CKO") (pintype "bidirectional"))
      (node (ref "U252") (pin "CKI") (pinfunction "CI_CKI") (pintype "bidirectional"))
    )
    (net (code "495") (name "Net-(U251-DO)") (class "Default")
      (node (ref "U251") (pin "SDO") (pinfunction "DO_SDO") (pintype "bidirectional"))
      (node (ref "U252") (pin "SDI") (pinfunction "DI_SDI") (pintype "bidirectional"))
    )
    (net (code "496") (name "SD1") (class "Default")
      (node (ref "U28") (pin "SDO") (pinfunction "DO_SDO") (pintype "bidirectional"))
      (node (ref "U29") (pin "SDI") (pinfunction "DI_SDI") (pintype "bidirectional"))
    )
    (net (code "497") (name "SD2") (class "Default")
      (node (ref "U56") (pin "SDO") (pinfunction "DO_SDO") (pintype "bidirectional"))
      (node (ref "U57") (pin "SDI") (pinfunction "DI_SDI") (pintype "bidirectional"))
    )
    (net (code "498") (name "SD3") (class "Default")
      (node (ref "U84") (pin "SDO") (pinfunction "DO_SDO") (pintype "bidirectional"))
      (node (ref "U85") (pin "SDI") (pinfunction "DI_SDI") (pintype "bidirectional"))
    )
    (net (code "499") (name "SD4") (class "Default")
      (node (ref "U112") (pin "SDO") (pinfunction "DO_SDO") (pintype "bidirectional"))
      (node (ref "U113") (pin "SDI") (pinfunction "DI_SDI") (pintype "bidirectional"))
    )
    (net (code "500") (name "SD5") (class "Default")
      (node (ref "U140") (pin "SDO") (pinfunction "DO_SDO") (pintype "bidirectional"))
      (node (ref "U141") (pin "SDI") (pinfunction "DI_SDI") (pintype "bidirectional"))
    )
    (net (code "501") (name "SD6") (class "Default")
      (node (ref "U168") (pin "SDO") (pinfunction "DO_SDO") (pintype "bidirectional"))
      (node (ref "U169") (pin "SDI") (pinfunction "DI_SDI") (pintype "bidirectional"))
    )
    (net (code "502") (name "SD7") (class "Default")
      (node (ref "U196") (pin "SDO") (pinfunction "DO_SDO") (pintype "bidirectional"))
      (node (ref "U197") (pin "SDI") (pinfunction "DI_SDI") (pintype "bidirectional"))
    )
    (net (code "503") (name "SD8") (class "Default")
      (node (ref "U224") (pin "SDO") (pinfunction "DO_SDO") (pintype "bidirectional"))
      (node (ref "U225") (pin "SDI") (pinfunction "DI_SDI") (pintype "bidirectional"))
    )
    (net (code "504") (name "VCC") (class "Default")
      (node (ref "J1") (pin "2") (pinfunction "2_2") (pintype "power_in"))
      (node (ref "J2") (pin "2") (pinfunction "2_2") (pintype "power_in"))
      (node (ref "U1") (pin "VDD") (pinfunction "VCC_VDD") (pintype "bidirectional"))
      (node (ref "U1") (pin "VDDPAD") (pinfunction "VCC_VDDPAD") (pintype "bidirectional"))
      (node (ref "U10") (pin "VDD") (pinfunction "VCC_VDD") (pintype "bidirectional"))
      (node (ref "U10") (pin "VDDPAD") (pinfunction "VCC_VDDPAD") (pintype "bidirectional"))
      (node (ref "U100") (pin "VDD") (pinfunction "VCC_VDD") (pintype "bidirectional"))
      (node (ref "U100") (pin "VDDPAD") (pinfunction "VCC_VDDPAD") (pintype "bidirectional"))
      (node (ref "U101") (pin "VDD") (pinfunction "VCC_VDD") (pintype "bidirectional"))
      (node (ref "U101") (pin "VDDPAD") (pinfunction "VCC_VDDPAD") (pintype "bidirectional"))
      (node (ref "U102") (pin "VDD") (pinfunction "VCC_VDD") (pintype "bidirectional"))
      (node (ref "U102") (pin "VDDPAD") (pinfunction "VCC_VDDPAD") (pintype "bidirectional"))
      (node (ref "U103") (pin "VDD") (pinfunction "VCC_VDD") (pintype "bidirectional"))
      (node (ref "U103") (pin "VDDPAD") (pinfunction "VCC_VDDPAD") (pintype "bidirectional"))
      (node (ref "U104") (pin "VDD") (pinfunction "VCC_VDD") (pintype "bidirectional"))
      (node (ref "U104") (pin "VDDPAD") (pinfunction "VCC_VDDPAD") (pintype "bidirectional"))
      (node (ref "U105") (pin "VDD") (pinfunction "VCC_VDD") (pintype "bidirectional"))
      (node (ref "U105") (pin "VDDPAD") (pinfunction "VCC_VDDPAD") (pintype "bidirectional"))
      (node (ref "U106") (pin "VDD") (pinfunction "VCC_VDD") (pintype "bidirectional"))
      (node (ref "U106") (pin "VDDPAD") (pinfunction "VCC_VDDPAD") (pintype "bidirectional"))
      (node (ref "U107") (pin "VDD") (pinfunction "VCC_VDD") (pintype "bidirectional"))
      (node (ref "U107") (pin "VDDPAD") (pinfunction "VCC_VDDPAD") (pintype "bidirectional"))
      (node (ref "U108") (pin "VDD") (pinfunction "VCC_VDD") (pintype "bidirectional"))
      (node (ref "U108") (pin "VDDPAD") (pinfunction "VCC_VDDPAD") (pintype "bidirectional"))
      (node (ref "U109") (pin "VDD") (pinfunction "VCC_VDD") (pintype "bidirectional"))
      (node (ref "U109") (pin "VDDPAD") (pinfunction "VCC_VDDPAD") (pintype "bidirectional"))
      (node (ref "U11") (pin "VDD") (pinfunction "VCC_VDD") (pintype "bidirectional"))
      (node (ref "U11") (pin "VDDPAD") (pinfunction "VCC_VDDPAD") (pintype "bidirectional"))
      (node (ref "U110") (pin "VDD") (pinfunction "VCC_VDD") (pintype "bidirectional"))
      (node (ref "U110") (pin "VDDPAD") (pinfunction "VCC_VDDPAD") (pintype "bidirectional"))
      (node (ref "U111") (pin "VDD") (pinfunction "VCC_VDD") (pintype "bidirectional"))
      (node (ref "U111") (pin "VDDPAD") (pinfunction "VCC_VDDPAD") (pintype "bidirectional"))
      (node (ref "U112") (pin "VDD") (pinfunction "VCC_VDD") (pintype "bidirectional"))
      (node (ref "U112") (pin "VDDPAD") (pinfunction "VCC_VDDPAD") (pintype "bidirectional"))
      (node (ref "U113") (pin "VDD") (pinfunction "VCC_VDD") (pintype "bidirectional"))
      (node (ref "U113") (pin "VDDPAD") (pinfunction "VCC_VDDPAD") (pintype "bidirectional"))
      (node (ref "U114") (pin "VDD") (pinfunction "VCC_VDD") (pintype "bidirectional"))
      (node (ref "U114") (pin "VDDPAD") (pinfunction "VCC_VDDPAD") (pintype "bidirectional"))
      (node (ref "U115") (pin "VDD") (pinfunction "VCC_VDD") (pintype "bidirectional"))
      (node (ref "U115") (pin "VDDPAD") (pinfunction "VCC_VDDPAD") (pintype "bidirectional"))
      (node (ref "U116") (pin "VDD") (pinfunction "VCC_VDD") (pintype "bidirectional"))
      (node (ref "U116") (pin "VDDPAD") (pinfunction "VCC_VDDPAD") (pintype "bidirectional"))
      (node (ref "U117") (pin "VDD") (pinfunction "VCC_VDD") (pintype "bidirectional"))
      (node (ref "U117") (pin "VDDPAD") (pinfunction "VCC_VDDPAD") (pintype "bidirectional"))
      (node (ref "U118") (pin "VDD") (pinfunction "VCC_VDD") (pintype "bidirectional"))
      (node (ref "U118") (pin "VDDPAD") (pinfunction "VCC_VDDPAD") (pintype "bidirectional"))
      (node (ref "U119") (pin "VDD") (pinfunction "VCC_VDD") (pintype "bidirectional"))
      (node (ref "U119") (pin "VDDPAD") (pinfunction "VCC_VDDPAD") (pintype "bidirectional"))
      (node (ref "U12") (pin "VDD") (pinfunction "VCC_VDD") (pintype "bidirectional"))
      (node (ref "U12") (pin "VDDPAD") (pinfunction "VCC_VDDPAD") (pintype "bidirectional"))
      (node (ref "U120") (pin "VDD") (pinfunction "VCC_VDD") (pintype "bidirectional"))
      (node (ref "U120") (pin "VDDPAD") (pinfunction "VCC_VDDPAD") (pintype "bidirectional"))
      (node (ref "U121") (pin "VDD") (pinfunction "VCC_VDD") (pintype "bidirectional"))
      (node (ref "U121") (pin "VDDPAD") (pinfunction "VCC_VDDPAD") (pintype "bidirectional"))
      (node (ref "U122") (pin "VDD") (pinfunction "VCC_VDD") (pintype "bidirectional"))
      (node (ref "U122") (pin "VDDPAD") (pinfunction "VCC_VDDPAD") (pintype "bidirectional"))
      (node (ref "U123") (pin "VDD") (pinfunction "VCC_VDD") (pintype "bidirectional"))
      (node (ref "U123") (pin "VDDPAD") (pinfunction "VCC_VDDPAD") (pintype "bidirectional"))
      (node (ref "U124") (pin "VDD") (pinfunction "VCC_VDD") (pintype "bidirectional"))
      (node (ref "U124") (pin "VDDPAD") (pinfunction "VCC_VDDPAD") (pintype "bidirectional"))
      (node (ref "U125") (pin "VDD") (pinfunction "VCC_VDD") (pintype "bidirectional"))
      (node (ref "U125") (pin "VDDPAD") (pinfunction "VCC_VDDPAD") (pintype "bidirectional"))
      (node (ref "U126") (pin "VDD") (pinfunction "VCC_VDD") (pintype "bidirectional"))
      (node (ref "U126") (pin "VDDPAD") (pinfunction "VCC_VDDPAD") (pintype "bidirectional"))
      (node (ref "U127") (pin "VDD") (pinfunction "VCC_VDD") (pintype "bidirectional"))
      (node (ref "U127") (pin "VDDPAD") (pinfunction "VCC_VDDPAD") (pintype "bidirectional"))
      (node (ref "U128") (pin "VDD") (pinfunction "VCC_VDD") (pintype "bidirectional"))
      (node (ref "U128") (pin "VDDPAD") (pinfunction "VCC_VDDPAD") (pintype "bidirectional"))
      (node (ref "U129") (pin "VDD") (pinfunction "VCC_VDD") (pintype "bidirectional"))
      (node (ref "U129") (pin "VDDPAD") (pinfunction "VCC_VDDPAD") (pintype "bidirectional"))
      (node (ref "U13") (pin "VDD") (pinfunction "VCC_VDD") (pintype "bidirectional"))
      (node (ref "U13") (pin "VDDPAD") (pinfunction "VCC_VDDPAD") (pintype "bidirectional"))
      (node (ref "U130") (pin "VDD") (pinfunction "VCC_VDD") (pintype "bidirectional"))
      (node (ref "U130") (pin "VDDPAD") (pinfunction "VCC_VDDPAD") (pintype "bidirectional"))
      (node (ref "U131") (pin "VDD") (pinfunction "VCC_VDD") (pintype "bidirectional"))
      (node (ref "U131") (pin "VDDPAD") (pinfunction "VCC_VDDPAD") (pintype "bidirectional"))
      (node (ref "U132") (pin "VDD") (pinfunction "VCC_VDD") (pintype "bidirectional"))
      (node (ref "U132") (pin "VDDPAD") (pinfunction "VCC_VDDPAD") (pintype "bidirectional"))
      (node (ref "U133") (pin "VDD") (pinfunction "VCC_VDD") (pintype "bidirectional"))
      (node (ref "U133") (pin "VDDPAD") (pinfunction "VCC_VDDPAD") (pintype "bidirectional"))
      (node (ref "U134") (pin "VDD") (pinfunction "VCC_VDD") (pintype "bidirectional"))
      (node (ref "U134") (pin "VDDPAD") (pinfunction "VCC_VDDPAD") (pintype "bidirectional"))
      (node (ref "U135") (pin "VDD") (pinfunction "VCC_VDD") (pintype "bidirectional"))
      (node (ref "U135") (pin "VDDPAD") (pinfunction "VCC_VDDPAD") (pintype "bidirectional"))
      (node (ref "U136") (pin "VDD") (pinfunction "VCC_VDD") (pintype "bidirectional"))
      (node (ref "U136") (pin "VDDPAD") (pinfunction "VCC_VDDPAD") (pintype "bidirectional"))
      (node (ref "U137") (pin "VDD") (pinfunction "VCC_VDD") (pintype "bidirectional"))
      (node (ref "U137") (pin "VDDPAD") (pinfunction "VCC_VDDPAD") (pintype "bidirectional"))
      (node (ref "U138") (pin "VDD") (pinfunction "VCC_VDD") (pintype "bidirectional"))
      (node (ref "U138") (pin "VDDPAD") (pinfunction "VCC_VDDPAD") (pintype "bidirectional"))
      (node (ref "U139") (pin "VDD") (pinfunction "VCC_VDD") (pintype "bidirectional"))
      (node (ref "U139") (pin "VDDPAD") (pinfunction "VCC_VDDPAD") (pintype "bidirectional"))
      (node (ref "U14") (pin "VDD") (pinfunction "VCC_VDD") (pintype "bidirectional"))
      (node (ref "U14") (pin "VDDPAD") (pinfunction "VCC_VDDPAD") (pintype "bidirectional"))
      (node (ref "U140") (pin "VDD") (pinfunction "VCC_VDD") (pintype "bidirectional"))
      (node (ref "U140") (pin "VDDPAD") (pinfunction "VCC_VDDPAD") (pintype "bidirectional"))
      (node (ref "U141") (pin "VDD") (pinfunction "VCC_VDD") (pintype "bidirectional"))
      (node (ref "U141") (pin "VDDPAD") (pinfunction "VCC_VDDPAD") (pintype "bidirectional"))
      (node (ref "U142") (pin "VDD") (pinfunction "VCC_VDD") (pintype "bidirectional"))
      (node (ref "U142") (pin "VDDPAD") (pinfunction "VCC_VDDPAD") (pintype "bidirectional"))
      (node (ref "U143") (pin "VDD") (pinfunction "VCC_VDD") (pintype "bidirectional"))
      (node (ref "U143") (pin "VDDPAD") (pinfunction "VCC_VDDPAD") (pintype "bidirectional"))
      (node (ref "U144") (pin "VDD") (pinfunction "VCC_VDD") (pintype "bidirectional"))
      (node (ref "U144") (pin "VDDPAD") (pinfunction "VCC_VDDPAD") (pintype "bidirectional"))
      (node (ref "U145") (pin "VDD") (pinfunction "VCC_VDD") (pintype "bidirectional"))
      (node (ref "U145") (pin "VDDPAD") (pinfunction "VCC_VDDPAD") (pintype "bidirectional"))
      (node (ref "U146") (pin "VDD") (pinfunction "VCC_VDD") (pintype "bidirectional"))
      (node (ref "U146") (pin "VDDPAD") (pinfunction "VCC_VDDPAD") (pintype "bidirectional"))
      (node (ref "U147") (pin "VDD") (pinfunction "VCC_VDD") (pintype "bidirectional"))
      (node (ref "U147") (pin "VDDPAD") (pinfunction "VCC_VDDPAD") (pintype "bidirectional"))
      (node (ref "U148") (pin "VDD") (pinfunction "VCC_VDD") (pintype "bidirectional"))
      (node (ref "U148") (pin "VDDPAD") (pinfunction "VCC_VDDPAD") (pintype "bidirectional"))
      (node (ref "U149") (pin "VDD") (pinfunction "VCC_VDD") (pintype "bidirectional"))
      (node (ref "U149") (pin "VDDPAD") (pinfunction "VCC_VDDPAD") (pintype "bidirectional"))
      (node (ref "U15") (pin "VDD") (pinfunction "VCC_VDD") (pintype "bidirectional"))
      (node (ref "U15") (pin "VDDPAD") (pinfunction "VCC_VDDPAD") (pintype "bidirectional"))
      (node (ref "U150") (pin "VDD") (pinfunction "VCC_VDD") (pintype "bidirectional"))
      (node (ref "U150") (pin "VDDPAD") (pinfunction "VCC_VDDPAD") (pintype "bidirectional"))
      (node (ref "U151") (pin "VDD") (pinfunction "VCC_VDD") (pintype "bidirectional"))
      (node (ref "U151") (pin "VDDPAD") (pinfunction "VCC_VDDPAD") (pintype "bidirectional"))
      (node (ref "U152") (pin "VDD") (pinfunction "VCC_VDD") (pintype "bidirectional"))
      (node (ref "U152") (pin "VDDPAD") (pinfunction "VCC_VDDPAD") (pintype "bidirectional"))
      (node (ref "U153") (pin "VDD") (pinfunction "VCC_VDD") (pintype "bidirectional"))
      (node (ref "U153") (pin "VDDPAD") (pinfunction "VCC_VDDPAD") (pintype "bidirectional"))
      (node (ref "U154") (pin "VDD") (pinfunction "VCC_VDD") (pintype "bidirectional"))
      (node (ref "U154") (pin "VDDPAD") (pinfunction "VCC_VDDPAD") (pintype "bidirectional"))
      (node (ref "U155") (pin "VDD") (pinfunction "VCC_VDD") (pintype "bidirectional"))
      (node (ref "U155") (pin "VDDPAD") (pinfunction "VCC_VDDPAD") (pintype "bidirectional"))
      (node (ref "U156") (pin "VDD") (pinfunction "VCC_VDD") (pintype "bidirectional"))
      (node (ref "U156") (pin "VDDPAD") (pinfunction "VCC_VDDPAD") (pintype "bidirectional"))
      (node (ref "U157") (pin "VDD") (pinfunction "VCC_VDD") (pintype "bidirectional"))
      (node (ref "U157") (pin "VDDPAD") (pinfunction "VCC_VDDPAD") (pintype "bidirectional"))
      (node (ref "U158") (pin "VDD") (pinfunction "VCC_VDD") (pintype "bidirectional"))
      (node (ref "U158") (pin "VDDPAD") (pinfunction "VCC_VDDPAD") (pintype "bidirectional"))
      (node (ref "U159") (pin "VDD") (pinfunction "VCC_VDD") (pintype "bidirectional"))
      (node (ref "U159") (pin "VDDPAD") (pinfunction "VCC_VDDPAD") (pintype "bidirectional"))
      (node (ref "U16") (pin "VDD") (pinfunction "VCC_VDD") (pintype "bidirectional"))
      (node (ref "U16") (pin "VDDPAD") (pinfunction "VCC_VDDPAD") (pintype "bidirectional"))
      (node (ref "U160") (pin "VDD") (pinfunction "VCC_VDD") (pintype "bidirectional"))
      (node (ref "U160") (pin "VDDPAD") (pinfunction "VCC_VDDPAD") (pintype "bidirectional"))
      (node (ref "U161") (pin "VDD") (pinfunction "VCC_VDD") (pintype "bidirectional"))
      (node (ref "U161") (pin "VDDPAD") (pinfunction "VCC_VDDPAD") (pintype "bidirectional"))
      (node (ref "U162") (pin "VDD") (pinfunction "VCC_VDD") (pintype "bidirectional"))
      (node (ref "U162") (pin "VDDPAD") (pinfunction "VCC_VDDPAD") (pintype "bidirectional"))
      (node (ref "U163") (pin "VDD") (pinfunction "VCC_VDD") (pintype "bidirectional"))
      (node (ref "U163") (pin "VDDPAD") (pinfunction "VCC_VDDPAD") (pintype "bidirectional"))
      (node (ref "U164") (pin "VDD") (pinfunction "VCC_VDD") (pintype "bidirectional"))
      (node (ref "U164") (pin "VDDPAD") (pinfunction "VCC_VDDPAD") (pintype "bidirectional"))
      (node (ref "U165") (pin "VDD") (pinfunction "VCC_VDD") (pintype "bidirectional"))
      (node (ref "U165") (pin "VDDPAD") (pinfunction "VCC_VDDPAD") (pintype "bidirectional"))
      (node (ref "U166") (pin "VDD") (pinfunction "VCC_VDD") (pintype "bidirectional"))
      (node (ref "U166") (pin "VDDPAD") (pinfunction "VCC_VDDPAD") (pintype "bidirectional"))
      (node (ref "U167") (pin "VDD") (pinfunction "VCC_VDD") (pintype "bidirectional"))
      (node (ref "U167") (pin "VDDPAD") (pinfunction "VCC_VDDPAD") (pintype "bidirectional"))
      (node (ref "U168") (pin "VDD") (pinfunction "VCC_VDD") (pintype "bidirectional"))
      (node (ref "U168") (pin "VDDPAD") (pinfunction "VCC_VDDPAD") (pintype "bidirectional"))
      (node (ref "U169") (pin "VDD") (pinfunction "VCC_VDD") (pintype "bidirectional"))
      (node (ref "U169") (pin "VDDPAD") (pinfunction "VCC_VDDPAD") (pintype "bidirectional"))
      (node (ref "U17") (pin "VDD") (pinfunction "VCC_VDD") (pintype "bidirectional"))
      (node (ref "U17") (pin "VDDPAD") (pinfunction "VCC_VDDPAD") (pintype "bidirectional"))
      (node (ref "U170") (pin "VDD") (pinfunction "VCC_VDD") (pintype "bidirectional"))
      (node (ref "U170") (pin "VDDPAD") (pinfunction "VCC_VDDPAD") (pintype "bidirectional"))
      (node (ref "U171") (pin "VDD") (pinfunction "VCC_VDD") (pintype "bidirectional"))
      (node (ref "U171") (pin "VDDPAD") (pinfunction "VCC_VDDPAD") (pintype "bidirectional"))
      (node (ref "U172") (pin "VDD") (pinfunction "VCC_VDD") (pintype "bidirectional"))
      (node (ref "U172") (pin "VDDPAD") (pinfunction "VCC_VDDPAD") (pintype "bidirectional"))
      (node (ref "U173") (pin "VDD") (pinfunction "VCC_VDD") (pintype "bidirectional"))
      (node (ref "U173") (pin "VDDPAD") (pinfunction "VCC_VDDPAD") (pintype "bidirectional"))
      (node (ref "U174") (pin "VDD") (pinfunction "VCC_VDD") (pintype "bidirectional"))
      (node (ref "U174") (pin "VDDPAD") (pinfunction "VCC_VDDPAD") (pintype "bidirectional"))
      (node (ref "U175") (pin "VDD") (pinfunction "VCC_VDD") (pintype "bidirectional"))
      (node (ref "U175") (pin "VDDPAD") (pinfunction "VCC_VDDPAD") (pintype "bidirectional"))
      (node (ref "U176") (pin "VDD") (pinfunction "VCC_VDD") (pintype "bidirectional"))
      (node (ref "U176") (pin "VDDPAD") (pinfunction "VCC_VDDPAD") (pintype "bidirectional"))
      (node (ref "U177") (pin "VDD") (pinfunction "VCC_VDD") (pintype "bidirectional"))
      (node (ref "U177") (pin "VDDPAD") (pinfunction "VCC_VDDPAD") (pintype "bidirectional"))
      (node (ref "U178") (pin "VDD") (pinfunction "VCC_VDD") (pintype "bidirectional"))
      (node (ref "U178") (pin "VDDPAD") (pinfunction "VCC_VDDPAD") (pintype "bidirectional"))
      (node (ref "U179") (pin "VDD") (pinfunction "VCC_VDD") (pintype "bidirectional"))
      (node (ref "U179") (pin "VDDPAD") (pinfunction "VCC_VDDPAD") (pintype "bidirectional"))
      (node (ref "U18") (pin "VDD") (pinfunction "VCC_VDD") (pintype "bidirectional"))
      (node (ref "U18") (pin "VDDPAD") (pinfunction "VCC_VDDPAD") (pintype "bidirectional"))
      (node (ref "U180") (pin "VDD") (pinfunction "VCC_VDD") (pintype "bidirectional"))
      (node (ref "U180") (pin "VDDPAD") (pinfunction "VCC_VDDPAD") (pintype "bidirectional"))
      (node (ref "U181") (pin "VDD") (pinfunction "VCC_VDD") (pintype "bidirectional"))
      (node (ref "U181") (pin "VDDPAD") (pinfunction "VCC_VDDPAD") (pintype "bidirectional"))
      (node (ref "U182") (pin "VDD") (pinfunction "VCC_VDD") (pintype "bidirectional"))
      (node (ref "U182") (pin "VDDPAD") (pinfunction "VCC_VDDPAD") (pintype "bidirectional"))
      (node (ref "U183") (pin "VDD") (pinfunction "VCC_VDD") (pintype "bidirectional"))
      (node (ref "U183") (pin "VDDPAD") (pinfunction "VCC_VDDPAD") (pintype "bidirectional"))
      (node (ref "U184") (pin "VDD") (pinfunction "VCC_VDD") (pintype "bidirectional"))
      (node (ref "U184") (pin "VDDPAD") (pinfunction "VCC_VDDPAD") (pintype "bidirectional"))
      (node (ref "U185") (pin "VDD") (pinfunction "VCC_VDD") (pintype "bidirectional"))
      (node (ref "U185") (pin "VDDPAD") (pinfunction "VCC_VDDPAD") (pintype "bidirectional"))
      (node (ref "U186") (pin "VDD") (pinfunction "VCC_VDD") (pintype "bidirectional"))
      (node (ref "U186") (pin "VDDPAD") (pinfunction "VCC_VDDPAD") (pintype "bidirectional"))
      (node (ref "U187") (pin "VDD") (pinfunction "VCC_VDD") (pintype "bidirectional"))
      (node (ref "U187") (pin "VDDPAD") (pinfunction "VCC_VDDPAD") (pintype "bidirectional"))
      (node (ref "U188") (pin "VDD") (pinfunction "VCC_VDD") (pintype "bidirectional"))
      (node (ref "U188") (pin "VDDPAD") (pinfunction "VCC_VDDPAD") (pintype "bidirectional"))
      (node (ref "U189") (pin "VDD") (pinfunction "VCC_VDD") (pintype "bidirectional"))
      (node (ref "U189") (pin "VDDPAD") (pinfunction "VCC_VDDPAD") (pintype "bidirectional"))
      (node (ref "U19") (pin "VDD") (pinfunction "VCC_VDD") (pintype "bidirectional"))
      (node (ref "U19") (pin "VDDPAD") (pinfunction "VCC_VDDPAD") (pintype "bidirectional"))
      (node (ref "U190") (pin "VDD") (pinfunction "VCC_VDD") (pintype "bidirectional"))
      (node (ref "U190") (pin "VDDPAD") (pinfunction "VCC_VDDPAD") (pintype "bidirectional"))
      (node (ref "U191") (pin "VDD") (pinfunction "VCC_VDD") (pintype "bidirectional"))
      (node (ref "U191") (pin "VDDPAD") (pinfunction "VCC_VDDPAD") (pintype "bidirectional"))
      (node (ref "U192") (pin "VDD") (pinfunction "VCC_VDD") (pintype "bidirectional"))
      (node (ref "U192") (pin "VDDPAD") (pinfunction "VCC_VDDPAD") (pintype "bidirectional"))
      (node (ref "U193") (pin "VDD") (pinfunction "VCC_VDD") (pintype "bidirectional"))
      (node (ref "U193") (pin "VDDPAD") (pinfunction "VCC_VDDPAD") (pintype "bidirectional"))
      (node (ref "U194") (pin "VDD") (pinfunction "VCC_VDD") (pintype "bidirectional"))
      (node (ref "U194") (pin "VDDPAD") (pinfunction "VCC_VDDPAD") (pintype "bidirectional"))
      (node (ref "U195") (pin "VDD") (pinfunction "VCC_VDD") (pintype "bidirectional"))
      (node (ref "U195") (pin "VDDPAD") (pinfunction "VCC_VDDPAD") (pintype "bidirectional"))
      (node (ref "U196") (pin "VDD") (pinfunction "VCC_VDD") (pintype "bidirectional"))
      (node (ref "U196") (pin "VDDPAD") (pinfunction "VCC_VDDPAD") (pintype "bidirectional"))
      (node (ref "U197") (pin "VDD") (pinfunction "VCC_VDD") (pintype "bidirectional"))
      (node (ref "U197") (pin "VDDPAD") (pinfunction "VCC_VDDPAD") (pintype "bidirectional"))
      (node (ref "U198") (pin "VDD") (pinfunction "VCC_VDD") (pintype "bidirectional"))
      (node (ref "U198") (pin "VDDPAD") (pinfunction "VCC_VDDPAD") (pintype "bidirectional"))
      (node (ref "U199") (pin "VDD") (pinfunction "VCC_VDD") (pintype "bidirectional"))
      (node (ref "U199") (pin "VDDPAD") (pinfunction "VCC_VDDPAD") (pintype "bidirectional"))
      (node (ref "U2") (pin "VDD") (pinfunction "VCC_VDD") (pintype "bidirectional"))
      (node (ref "U2") (pin "VDDPAD") (pinfunction "VCC_VDDPAD") (pintype "bidirectional"))
      (node (ref "U20") (pin "VDD") (pinfunction "VCC_VDD") (pintype "bidirectional"))
      (node (ref "U20") (pin "VDDPAD") (pinfunction "VCC_VDDPAD") (pintype "bidirectional"))
      (node (ref "U200") (pin "VDD") (pinfunction "VCC_VDD") (pintype "bidirectional"))
      (node (ref "U200") (pin "VDDPAD") (pinfunction "VCC_VDDPAD") (pintype "bidirectional"))
      (node (ref "U201") (pin "VDD") (pinfunction "VCC_VDD") (pintype "bidirectional"))
      (node (ref "U201") (pin "VDDPAD") (pinfunction "VCC_VDDPAD") (pintype "bidirectional"))
      (node (ref "U202") (pin "VDD") (pinfunction "VCC_VDD") (pintype "bidirectional"))
      (node (ref "U202") (pin "VDDPAD") (pinfunction "VCC_VDDPAD") (pintype "bidirectional"))
      (node (ref "U203") (pin "VDD") (pinfunction "VCC_VDD") (pintype "bidirectional"))
      (node (ref "U203") (pin "VDDPAD") (pinfunction "VCC_VDDPAD") (pintype "bidirectional"))
      (node (ref "U204") (pin "VDD") (pinfunction "VCC_VDD") (pintype "bidirectional"))
      (node (ref "U204") (pin "VDDPAD") (pinfunction "VCC_VDDPAD") (pintype "bidirectional"))
      (node (ref "U205") (pin "VDD") (pinfunction "VCC_VDD") (pintype "bidirectional"))
      (node (ref "U205") (pin "VDDPAD") (pinfunction "VCC_VDDPAD") (pintype "bidirectional"))
      (node (ref "U206") (pin "VDD") (pinfunction "VCC_VDD") (pintype "bidirectional"))
      (node (ref "U206") (pin "VDDPAD") (pinfunction "VCC_VDDPAD") (pintype "bidirectional"))
      (node (ref "U207") (pin "VDD") (pinfunction "VCC_VDD") (pintype "bidirectional"))
      (node (ref "U207") (pin "VDDPAD") (pinfunction "VCC_VDDPAD") (pintype "bidirectional"))
      (node (ref "U208") (pin "VDD") (pinfunction "VCC_VDD") (pintype "bidirectional"))
      (node (ref "U208") (pin "VDDPAD") (pinfunction "VCC_VDDPAD") (pintype "bidirectional"))
      (node (ref "U209") (pin "VDD") (pinfunction "VCC_VDD") (pintype "bidirectional"))
      (node (ref "U209") (pin "VDDPAD") (pinfunction "VCC_VDDPAD") (pintype "bidirectional"))
      (node (ref "U21") (pin "VDD") (pinfunction "VCC_VDD") (pintype "bidirectional"))
      (node (ref "U21") (pin "VDDPAD") (pinfunction "VCC_VDDPAD") (pintype "bidirectional"))
      (node (ref "U210") (pin "VDD") (pinfunction "VCC_VDD") (pintype "bidirectional"))
      (node (ref "U210") (pin "VDDPAD") (pinfunction "VCC_VDDPAD") (pintype "bidirectional"))
      (node (ref "U211") (pin "VDD") (pinfunction "VCC_VDD") (pintype "bidirectional"))
      (node (ref "U211") (pin "VDDPAD") (pinfunction "VCC_VDDPAD") (pintype "bidirectional"))
      (node (ref "U212") (pin "VDD") (pinfunction "VCC_VDD") (pintype "bidirectional"))
      (node (ref "U212") (pin "VDDPAD") (pinfunction "VCC_VDDPAD") (pintype "bidirectional"))
      (node (ref "U213") (pin "VDD") (pinfunction "VCC_VDD") (pintype "bidirectional"))
      (node (ref "U213") (pin "VDDPAD") (pinfunction "VCC_VDDPAD") (pintype "bidirectional"))
      (node (ref "U214") (pin "VDD") (pinfunction "VCC_VDD") (pintype "bidirectional"))
      (node (ref "U214") (pin "VDDPAD") (pinfunction "VCC_VDDPAD") (pintype "bidirectional"))
      (node (ref "U215") (pin "VDD") (pinfunction "VCC_VDD") (pintype "bidirectional"))
      (node (ref "U215") (pin "VDDPAD") (pinfunction "VCC_VDDPAD") (pintype "bidirectional"))
      (node (ref "U216") (pin "VDD") (pinfunction "VCC_VDD") (pintype "bidirectional"))
      (node (ref "U216") (pin "VDDPAD") (pinfunction "VCC_VDDPAD") (pintype "bidirectional"))
      (node (ref "U217") (pin "VDD") (pinfunction "VCC_VDD") (pintype "bidirectional"))
      (node (ref "U217") (pin "VDDPAD") (pinfunction "VCC_VDDPAD") (pintype "bidirectional"))
      (node (ref "U218") (pin "VDD") (pinfunction "VCC_VDD") (pintype "bidirectional"))
      (node (ref "U218") (pin "VDDPAD") (pinfunction "VCC_VDDPAD") (pintype "bidirectional"))
      (node (ref "U219") (pin "VDD") (pinfunction "VCC_VDD") (pintype "bidirectional"))
      (node (ref "U219") (pin "VDDPAD") (pinfunction "VCC_VDDPAD") (pintype "bidirectional"))
      (node (ref "U22") (pin "VDD") (pinfunction "VCC_VDD") (pintype "bidirectional"))
      (node (ref "U22") (pin "VDDPAD") (pinfunction "VCC_VDDPAD") (pintype "bidirectional"))
      (node (ref "U220") (pin "VDD") (pinfunction "VCC_VDD") (pintype "bidirectional"))
      (node (ref "U220") (pin "VDDPAD") (pinfunction "VCC_VDDPAD") (pintype "bidirectional"))
      (node (ref "U221") (pin "VDD") (pinfunction "VCC_VDD") (pintype "bidirectional"))
      (node (ref "U221") (pin "VDDPAD") (pinfunction "VCC_VDDPAD") (pintype "bidirectional"))
      (node (ref "U222") (pin "VDD") (pinfunction "VCC_VDD") (pintype "bidirectional"))
      (node (ref "U222") (pin "VDDPAD") (pinfunction "VCC_VDDPAD") (pintype "bidirectional"))
      (node (ref "U223") (pin "VDD") (pinfunction "VCC_VDD") (pintype "bidirectional"))
      (node (ref "U223") (pin "VDDPAD") (pinfunction "VCC_VDDPAD") (pintype "bidirectional"))
      (node (ref "U224") (pin "VDD") (pinfunction "VCC_VDD") (pintype "bidirectional"))
      (node (ref "U224") (pin "VDDPAD") (pinfunction "VCC_VDDPAD") (pintype "bidirectional"))
      (node (ref "U225") (pin "VDD") (pinfunction "VCC_VDD") (pintype "bidirectional"))
      (node (ref "U225") (pin "VDDPAD") (pinfunction "VCC_VDDPAD") (pintype "bidirectional"))
      (node (ref "U226") (pin "VDD") (pinfunction "VCC_VDD") (pintype "bidirectional"))
      (node (ref "U226") (pin "VDDPAD") (pinfunction "VCC_VDDPAD") (pintype "bidirectional"))
      (node (ref "U227") (pin "VDD") (pinfunction "VCC_VDD") (pintype "bidirectional"))
      (node (ref "U227") (pin "VDDPAD") (pinfunction "VCC_VDDPAD") (pintype "bidirectional"))
      (node (ref "U228") (pin "VDD") (pinfunction "VCC_VDD") (pintype "bidirectional"))
      (node (ref "U228") (pin "VDDPAD") (pinfunction "VCC_VDDPAD") (pintype "bidirectional"))
      (node (ref "U229") (pin "VDD") (pinfunction "VCC_VDD") (pintype "bidirectional"))
      (node (ref "U229") (pin "VDDPAD") (pinfunction "VCC_VDDPAD") (pintype "bidirectional"))
      (node (ref "U23") (pin "VDD") (pinfunction "VCC_VDD") (pintype "bidirectional"))
      (node (ref "U23") (pin "VDDPAD") (pinfunction "VCC_VDDPAD") (pintype "bidirectional"))
      (node (ref "U230") (pin "VDD") (pinfunction "VCC_VDD") (pintype "bidirectional"))
      (node (ref "U230") (pin "VDDPAD") (pinfunction "VCC_VDDPAD") (pintype "bidirectional"))
      (node (ref "U231") (pin "VDD") (pinfunction "VCC_VDD") (pintype "bidirectional"))
      (node (ref "U231") (pin "VDDPAD") (pinfunction "VCC_VDDPAD") (pintype "bidirectional"))
      (node (ref "U232") (pin "VDD") (pinfunction "VCC_VDD") (pintype "bidirectional"))
      (node (ref "U232") (pin "VDDPAD") (pinfunction "VCC_VDDPAD") (pintype "bidirectional"))
      (node (ref "U233") (pin "VDD") (pinfunction "VCC_VDD") (pintype "bidirectional"))
      (node (ref "U233") (pin "VDDPAD") (pinfunction "VCC_VDDPAD") (pintype "bidirectional"))
      (node (ref "U234") (pin "VDD") (pinfunction "VCC_VDD") (pintype "bidirectional"))
      (node (ref "U234") (pin "VDDPAD") (pinfunction "VCC_VDDPAD") (pintype "bidirectional"))
      (node (ref "U235") (pin "VDD") (pinfunction "VCC_VDD") (pintype "bidirectional"))
      (node (ref "U235") (pin "VDDPAD") (pinfunction "VCC_VDDPAD") (pintype "bidirectional"))
      (node (ref "U236") (pin "VDD") (pinfunction "VCC_VDD") (pintype "bidirectional"))
      (node (ref "U236") (pin "VDDPAD") (pinfunction "VCC_VDDPAD") (pintype "bidirectional"))
      (node (ref "U237") (pin "VDD") (pinfunction "VCC_VDD") (pintype "bidirectional"))
      (node (ref "U237") (pin "VDDPAD") (pinfunction "VCC_VDDPAD") (pintype "bidirectional"))
      (node (ref "U238") (pin "VDD") (pinfunction "VCC_VDD") (pintype "bidirectional"))
      (node (ref "U238") (pin "VDDPAD") (pinfunction "VCC_VDDPAD") (pintype "bidirectional"))
      (node (ref "U239") (pin "VDD") (pinfunction "VCC_VDD") (pintype "bidirectional"))
      (node (ref "U239") (pin "VDDPAD") (pinfunction "VCC_VDDPAD") (pintype "bidirectional"))
      (node (ref "U24") (pin "VDD") (pinfunction "VCC_VDD") (pintype "bidirectional"))
      (node (ref "U24") (pin "VDDPAD") (pinfunction "VCC_VDDPAD") (pintype "bidirectional"))
      (node (ref "U240") (pin "VDD") (pinfunction "VCC_VDD") (pintype "bidirectional"))
      (node (ref "U240") (pin "VDDPAD") (pinfunction "VCC_VDDPAD") (pintype "bidirectional"))
      (node (ref "U241") (pin "VDD") (pinfunction "VCC_VDD") (pintype "bidirectional"))
      (node (ref "U241") (pin "VDDPAD") (pinfunction "VCC_VDDPAD") (pintype "bidirectional"))
      (node (ref "U242") (pin "VDD") (pinfunction "VCC_VDD") (pintype "bidirectional"))
      (node (ref "U242") (pin "VDDPAD") (pinfunction "VCC_VDDPAD") (pintype "bidirectional"))
      (node (ref "U243") (pin "VDD") (pinfunction "VCC_VDD") (pintype "bidirectional"))
      (node (ref "U243") (pin "VDDPAD") (pinfunction "VCC_VDDPAD") (pintype "bidirectional"))
      (node (ref "U244") (pin "VDD") (pinfunction "VCC_VDD") (pintype "bidirectional"))
      (node (ref "U244") (pin "VDDPAD") (pinfunction "VCC_VDDPAD") (pintype "bidirectional"))
      (node (ref "U245") (pin "VDD") (pinfunction "VCC_VDD") (pintype "bidirectional"))
      (node (ref "U245") (pin "VDDPAD") (pinfunction "VCC_VDDPAD") (pintype "bidirectional"))
      (node (ref "U246") (pin "VDD") (pinfunction "VCC_VDD") (pintype "bidirectional"))
      (node (ref "U246") (pin "VDDPAD") (pinfunction "VCC_VDDPAD") (pintype "bidirectional"))
      (node (ref "U247") (pin "VDD") (pinfunction "VCC_VDD") (pintype "bidirectional"))
      (node (ref "U247") (pin "VDDPAD") (pinfunction "VCC_VDDPAD") (pintype "bidirectional"))
      (node (ref "U248") (pin "VDD") (pinfunction "VCC_VDD") (pintype "bidirectional"))
      (node (ref "U248") (pin "VDDPAD") (pinfunction "VCC_VDDPAD") (pintype "bidirectional"))
      (node (ref "U249") (pin "VDD") (pinfunction "VCC_VDD") (pintype "bidirectional"))
      (node (ref "U249") (pin "VDDPAD") (pinfunction "VCC_VDDPAD") (pintype "bidirectional"))
      (node (ref "U25") (pin "VDD") (pinfunction "VCC_VDD") (pintype "bidirectional"))
      (node (ref "U25") (pin "VDDPAD") (pinfunction "VCC_VDDPAD") (pintype "bidirectional"))
      (node (ref "U250") (pin "VDD") (pinfunction "VCC_VDD") (pintype "bidirectional"))
      (node (ref "U250") (pin "VDDPAD") (pinfunction "VCC_VDDPAD") (pintype "bidirectional"))
      (node (ref "U251") (pin "VDD") (pinfunction "VCC_VDD") (pintype "bidirectional"))
      (node (ref "U251") (pin "VDDPAD") (pinfunction "VCC_VDDPAD") (pintype "bidirectional"))
      (node (ref "U252") (pin "VDD") (pinfunction "VCC_VDD") (pintype "bidirectional"))
      (node (ref "U252") (pin "VDDPAD") (pinfunction "VCC_VDDPAD") (pintype "bidirectional"))
      (node (ref "U26") (pin "VDD") (pinfunction "VCC_VDD") (pintype "bidirectional"))
      (node (ref "U26") (pin "VDDPAD") (pinfunction "VCC_VDDPAD") (pintype "bidirectional"))
      (node (ref "U27") (pin "VDD") (pinfunction "VCC_VDD") (pintype "bidirectional"))
      (node (ref "U27") (pin "VDDPAD") (pinfunction "VCC_VDDPAD") (pintype "bidirectional"))
      (node (ref "U28") (pin "VDD") (pinfunction "VCC_VDD") (pintype "bidirectional"))
      (node (ref "U28") (pin "VDDPAD") (pinfunction "VCC_VDDPAD") (pintype "bidirectional"))
      (node (ref "U29") (pin "VDD") (pinfunction "VCC_VDD") (pintype "bidirectional"))
      (node (ref "U29") (pin "VDDPAD") (pinfunction "VCC_VDDPAD") (pintype "bidirectional"))
      (node (ref "U3") (pin "VDD") (pinfunction "VCC_VDD") (pintype "bidirectional"))
      (node (ref "U3") (pin "VDDPAD") (pinfunction "VCC_VDDPAD") (pintype "bidirectional"))
      (node (ref "U30") (pin "VDD") (pinfunction "VCC_VDD") (pintype "bidirectional"))
      (node (ref "U30") (pin "VDDPAD") (pinfunction "VCC_VDDPAD") (pintype "bidirectional"))
      (node (ref "U31") (pin "VDD") (pinfunction "VCC_VDD") (pintype "bidirectional"))
      (node (ref "U31") (pin "VDDPAD") (pinfunction "VCC_VDDPAD") (pintype "bidirectional"))
      (node (ref "U32") (pin "VDD") (pinfunction "VCC_VDD") (pintype "bidirectional"))
      (node (ref "U32") (pin "VDDPAD") (pinfunction "VCC_VDDPAD") (pintype "bidirectional"))
      (node (ref "U33") (pin "VDD") (pinfunction "VCC_VDD") (pintype "bidirectional"))
      (node (ref "U33") (pin "VDDPAD") (pinfunction "VCC_VDDPAD") (pintype "bidirectional"))
      (node (ref "U34") (pin "VDD") (pinfunction "VCC_VDD") (pintype "bidirectional"))
      (node (ref "U34") (pin "VDDPAD") (pinfunction "VCC_VDDPAD") (pintype "bidirectional"))
      (node (ref "U35") (pin "VDD") (pinfunction "VCC_VDD") (pintype "bidirectional"))
      (node (ref "U35") (pin "VDDPAD") (pinfunction "VCC_VDDPAD") (pintype "bidirectional"))
      (node (ref "U36") (pin "VDD") (pinfunction "VCC_VDD") (pintype "bidirectional"))
      (node (ref "U36") (pin "VDDPAD") (pinfunction "VCC_VDDPAD") (pintype "bidirectional"))
      (node (ref "U37") (pin "VDD") (pinfunction "VCC_VDD") (pintype "bidirectional"))
      (node (ref "U37") (pin "VDDPAD") (pinfunction "VCC_VDDPAD") (pintype "bidirectional"))
      (node (ref "U38") (pin "VDD") (pinfunction "VCC_VDD") (pintype "bidirectional"))
      (node (ref "U38") (pin "VDDPAD") (pinfunction "VCC_VDDPAD") (pintype "bidirectional"))
      (node (ref "U39") (pin "VDD") (pinfunction "VCC_VDD") (pintype "bidirectional"))
      (node (ref "U39") (pin "VDDPAD") (pinfunction "VCC_VDDPAD") (pintype "bidirectional"))
      (node (ref "U4") (pin "VDD") (pinfunction "VCC_VDD") (pintype "bidirectional"))
      (node (ref "U4") (pin "VDDPAD") (pinfunction "VCC_VDDPAD") (pintype "bidirectional"))
      (node (ref "U40") (pin "VDD") (pinfunction "VCC_VDD") (pintype "bidirectional"))
      (node (ref "U40") (pin "VDDPAD") (pinfunction "VCC_VDDPAD") (pintype "bidirectional"))
      (node (ref "U41") (pin "VDD") (pinfunction "VCC_VDD") (pintype "bidirectional"))
      (node (ref "U41") (pin "VDDPAD") (pinfunction "VCC_VDDPAD") (pintype "bidirectional"))
      (node (ref "U42") (pin "VDD") (pinfunction "VCC_VDD") (pintype "bidirectional"))
      (node (ref "U42") (pin "VDDPAD") (pinfunction "VCC_VDDPAD") (pintype "bidirectional"))
      (node (ref "U43") (pin "VDD") (pinfunction "VCC_VDD") (pintype "bidirectional"))
      (node (ref "U43") (pin "VDDPAD") (pinfunction "VCC_VDDPAD") (pintype "bidirectional"))
      (node (ref "U44") (pin "VDD") (pinfunction "VCC_VDD") (pintype "bidirectional"))
      (node (ref "U44") (pin "VDDPAD") (pinfunction "VCC_VDDPAD") (pintype "bidirectional"))
      (node (ref "U45") (pin "VDD") (pinfunction "VCC_VDD") (pintype "bidirectional"))
      (node (ref "U45") (pin "VDDPAD") (pinfunction "VCC_VDDPAD") (pintype "bidirectional"))
      (node (ref "U46") (pin "VDD") (pinfunction "VCC_VDD") (pintype "bidirectional"))
      (node (ref "U46") (pin "VDDPAD") (pinfunction "VCC_VDDPAD") (pintype "bidirectional"))
      (node (ref "U47") (pin "VDD") (pinfunction "VCC_VDD") (pintype "bidirectional"))
      (node (ref "U47") (pin "VDDPAD") (pinfunction "VCC_VDDPAD") (pintype "bidirectional"))
      (node (ref "U48") (pin "VDD") (pinfunction "VCC_VDD") (pintype "bidirectional"))
      (node (ref "U48") (pin "VDDPAD") (pinfunction "VCC_VDDPAD") (pintype "bidirectional"))
      (node (ref "U49") (pin "VDD") (pinfunction "VCC_VDD") (pintype "bidirectional"))
      (node (ref "U49") (pin "VDDPAD") (pinfunction "VCC_VDDPAD") (pintype "bidirectional"))
      (node (ref "U5") (pin "VDD") (pinfunction "VCC_VDD") (pintype "bidirectional"))
      (node (ref "U5") (pin "VDDPAD") (pinfunction "VCC_VDDPAD") (pintype "bidirectional"))
      (node (ref "U50") (pin "VDD") (pinfunction "VCC_VDD") (pintype "bidirectional"))
      (node (ref "U50") (pin "VDDPAD") (pinfunction "VCC_VDDPAD") (pintype "bidirectional"))
      (node (ref "U51") (pin "VDD") (pinfunction "VCC_VDD") (pintype "bidirectional"))
      (node (ref "U51") (pin "VDDPAD") (pinfunction "VCC_VDDPAD") (pintype "bidirectional"))
      (node (ref "U52") (pin "VDD") (pinfunction "VCC_VDD") (pintype "bidirectional"))
      (node (ref "U52") (pin "VDDPAD") (pinfunction "VCC_VDDPAD") (pintype "bidirectional"))
      (node (ref "U53") (pin "VDD") (pinfunction "VCC_VDD") (pintype "bidirectional"))
      (node (ref "U53") (pin "VDDPAD") (pinfunction "VCC_VDDPAD") (pintype "bidirectional"))
      (node (ref "U54") (pin "VDD") (pinfunction "VCC_VDD") (pintype "bidirectional"))
      (node (ref "U54") (pin "VDDPAD") (pinfunction "VCC_VDDPAD") (pintype "bidirectional"))
      (node (ref "U55") (pin "VDD") (pinfunction "VCC_VDD") (pintype "bidirectional"))
      (node (ref "U55") (pin "VDDPAD") (pinfunction "VCC_VDDPAD") (pintype "bidirectional"))
      (node (ref "U56") (pin "VDD") (pinfunction "VCC_VDD") (pintype "bidirectional"))
      (node (ref "U56") (pin "VDDPAD") (pinfunction "VCC_VDDPAD") (pintype "bidirectional"))
      (node (ref "U57") (pin "VDD") (pinfunction "VCC_VDD") (pintype "bidirectional"))
      (node (ref "U57") (pin "VDDPAD") (pinfunction "VCC_VDDPAD") (pintype "bidirectional"))
      (node (ref "U58") (pin "VDD") (pinfunction "VCC_VDD") (pintype "bidirectional"))
      (node (ref "U58") (pin "VDDPAD") (pinfunction "VCC_VDDPAD") (pintype "bidirectional"))
      (node (ref "U59") (pin "VDD") (pinfunction "VCC_VDD") (pintype "bidirectional"))
      (node (ref "U59") (pin "VDDPAD") (pinfunction "VCC_VDDPAD") (pintype "bidirectional"))
      (node (ref "U6") (pin "VDD") (pinfunction "VCC_VDD") (pintype "bidirectional"))
      (node (ref "U6") (pin "VDDPAD") (pinfunction "VCC_VDDPAD") (pintype "bidirectional"))
      (node (ref "U60") (pin "VDD") (pinfunction "VCC_VDD") (pintype "bidirectional"))
      (node (ref "U60") (pin "VDDPAD") (pinfunction "VCC_VDDPAD") (pintype "bidirectional"))
      (node (ref "U61") (pin "VDD") (pinfunction "VCC_VDD") (pintype "bidirectional"))
      (node (ref "U61") (pin "VDDPAD") (pinfunction "VCC_VDDPAD") (pintype "bidirectional"))
      (node (ref "U62") (pin "VDD") (pinfunction "VCC_VDD") (pintype "bidirectional"))
      (node (ref "U62") (pin "VDDPAD") (pinfunction "VCC_VDDPAD") (pintype "bidirectional"))
      (node (ref "U63") (pin "VDD") (pinfunction "VCC_VDD") (pintype "bidirectional"))
      (node (ref "U63") (pin "VDDPAD") (pinfunction "VCC_VDDPAD") (pintype "bidirectional"))
      (node (ref "U64") (pin "VDD") (pinfunction "VCC_VDD") (pintype "bidirectional"))
      (node (ref "U64") (pin "VDDPAD") (pinfunction "VCC_VDDPAD") (pintype "bidirectional"))
      (node (ref "U65") (pin "VDD") (pinfunction "VCC_VDD") (pintype "bidirectional"))
      (node (ref "U65") (pin "VDDPAD") (pinfunction "VCC_VDDPAD") (pintype "bidirectional"))
      (node (ref "U66") (pin "VDD") (pinfunction "VCC_VDD") (pintype "bidirectional"))
      (node (ref "U66") (pin "VDDPAD") (pinfunction "VCC_VDDPAD") (pintype "bidirectional"))
      (node (ref "U67") (pin "VDD") (pinfunction "VCC_VDD") (pintype "bidirectional"))
      (node (ref "U67") (pin "VDDPAD") (pinfunction "VCC_VDDPAD") (pintype "bidirectional"))
      (node (ref "U68") (pin "VDD") (pinfunction "VCC_VDD") (pintype "bidirectional"))
      (node (ref "U68") (pin "VDDPAD") (pinfunction "VCC_VDDPAD") (pintype "bidirectional"))
      (node (ref "U69") (pin "VDD") (pinfunction "VCC_VDD") (pintype "bidirectional"))
      (node (ref "U69") (pin "VDDPAD") (pinfunction "VCC_VDDPAD") (pintype "bidirectional"))
      (node (ref "U7") (pin "VDD") (pinfunction "VCC_VDD") (pintype "bidirectional"))
      (node (ref "U7") (pin "VDDPAD") (pinfunction "VCC_VDDPAD") (pintype "bidirectional"))
      (node (ref "U70") (pin "VDD") (pinfunction "VCC_VDD") (pintype "bidirectional"))
      (node (ref "U70") (pin "VDDPAD") (pinfunction "VCC_VDDPAD") (pintype "bidirectional"))
      (node (ref "U71") (pin "VDD") (pinfunction "VCC_VDD") (pintype "bidirectional"))
      (node (ref "U71") (pin "VDDPAD") (pinfunction "VCC_VDDPAD") (pintype "bidirectional"))
      (node (ref "U72") (pin "VDD") (pinfunction "VCC_VDD") (pintype "bidirectional"))
      (node (ref "U72") (pin "VDDPAD") (pinfunction "VCC_VDDPAD") (pintype "bidirectional"))
      (node (ref "U73") (pin "VDD") (pinfunction "VCC_VDD") (pintype "bidirectional"))
      (node (ref "U73") (pin "VDDPAD") (pinfunction "VCC_VDDPAD") (pintype "bidirectional"))
      (node (ref "U74") (pin "VDD") (pinfunction "VCC_VDD") (pintype "bidirectional"))
      (node (ref "U74") (pin "VDDPAD") (pinfunction "VCC_VDDPAD") (pintype "bidirectional"))
      (node (ref "U75") (pin "VDD") (pinfunction "VCC_VDD") (pintype "bidirectional"))
      (node (ref "U75") (pin "VDDPAD") (pinfunction "VCC_VDDPAD") (pintype "bidirectional"))
      (node (ref "U76") (pin "VDD") (pinfunction "VCC_VDD") (pintype "bidirectional"))
      (node (ref "U76") (pin "VDDPAD") (pinfunction "VCC_VDDPAD") (pintype "bidirectional"))
      (node (ref "U77") (pin "VDD") (pinfunction "VCC_VDD") (pintype "bidirectional"))
      (node (ref "U77") (pin "VDDPAD") (pinfunction "VCC_VDDPAD") (pintype "bidirectional"))
      (node (ref "U78") (pin "VDD") (pinfunction "VCC_VDD") (pintype "bidirectional"))
      (node (ref "U78") (pin "VDDPAD") (pinfunction "VCC_VDDPAD") (pintype "bidirectional"))
      (node (ref "U79") (pin "VDD") (pinfunction "VCC_VDD") (pintype "bidirectional"))
      (node (ref "U79") (pin "VDDPAD") (pinfunction "VCC_VDDPAD") (pintype "bidirectional"))
      (node (ref "U8") (pin "VDD") (pinfunction "VCC_VDD") (pintype "bidirectional"))
      (node (ref "U8") (pin "VDDPAD") (pinfunction "VCC_VDDPAD") (pintype "bidirectional"))
      (node (ref "U80") (pin "VDD") (pinfunction "VCC_VDD") (pintype "bidirectional"))
      (node (ref "U80") (pin "VDDPAD") (pinfunction "VCC_VDDPAD") (pintype "bidirectional"))
      (node (ref "U81") (pin "VDD") (pinfunction "VCC_VDD") (pintype "bidirectional"))
      (node (ref "U81") (pin "VDDPAD") (pinfunction "VCC_VDDPAD") (pintype "bidirectional"))
      (node (ref "U82") (pin "VDD") (pinfunction "VCC_VDD") (pintype "bidirectional"))
      (node (ref "U82") (pin "VDDPAD") (pinfunction "VCC_VDDPAD") (pintype "bidirectional"))
      (node (ref "U83") (pin "VDD") (pinfunction "VCC_VDD") (pintype "bidirectional"))
      (node (ref "U83") (pin "VDDPAD") (pinfunction "VCC_VDDPAD") (pintype "bidirectional"))
      (node (ref "U84") (pin "VDD") (pinfunction "VCC_VDD") (pintype "bidirectional"))
      (node (ref "U84") (pin "VDDPAD") (pinfunction "VCC_VDDPAD") (pintype "bidirectional"))
      (node (ref "U85") (pin "VDD") (pinfunction "VCC_VDD") (pintype "bidirectional"))
      (node (ref "U85") (pin "VDDPAD") (pinfunction "VCC_VDDPAD") (pintype "bidirectional"))
      (node (ref "U86") (pin "VDD") (pinfunction "VCC_VDD") (pintype "bidirectional"))
      (node (ref "U86") (pin "VDDPAD") (pinfunction "VCC_VDDPAD") (pintype "bidirectional"))
      (node (ref "U87") (pin "VDD") (pinfunction "VCC_VDD") (pintype "bidirectional"))
      (node (ref "U87") (pin "VDDPAD") (pinfunction "VCC_VDDPAD") (pintype "bidirectional"))
      (node (ref "U88") (pin "VDD") (pinfunction "VCC_VDD") (pintype "bidirectional"))
      (node (ref "U88") (pin "VDDPAD") (pinfunction "VCC_VDDPAD") (pintype "bidirectional"))
      (node (ref "U89") (pin "VDD") (pinfunction "VCC_VDD") (pintype "bidirectional"))
      (node (ref "U89") (pin "VDDPAD") (pinfunction "VCC_VDDPAD") (pintype "bidirectional"))
      (node (ref "U9") (pin "VDD") (pinfunction "VCC_VDD") (pintype "bidirectional"))
      (node (ref "U9") (pin "VDDPAD") (pinfunction "VCC_VDDPAD") (pintype "bidirectional"))
      (node (ref "U90") (pin "VDD") (pinfunction "VCC_VDD") (pintype "bidirectional"))
      (node (ref "U90") (pin "VDDPAD") (pinfunction "VCC_VDDPAD") (pintype "bidirectional"))
      (node (ref "U91") (pin "VDD") (pinfunction "VCC_VDD") (pintype "bidirectional"))
      (node (ref "U91") (pin "VDDPAD") (pinfunction "VCC_VDDPAD") (pintype "bidirectional"))
      (node (ref "U92") (pin "VDD") (pinfunction "VCC_VDD") (pintype "bidirectional"))
      (node (ref "U92") (pin "VDDPAD") (pinfunction "VCC_VDDPAD") (pintype "bidirectional"))
      (node (ref "U93") (pin "VDD") (pinfunction "VCC_VDD") (pintype "bidirectional"))
      (node (ref "U93") (pin "VDDPAD") (pinfunction "VCC_VDDPAD") (pintype "bidirectional"))
      (node (ref "U94") (pin "VDD") (pinfunction "VCC_VDD") (pintype "bidirectional"))
      (node (ref "U94") (pin "VDDPAD") (pinfunction "VCC_VDDPAD") (pintype "bidirectional"))
      (node (ref "U95") (pin "VDD") (pinfunction "VCC_VDD") (pintype "bidirectional"))
      (node (ref "U95") (pin "VDDPAD") (pinfunction "VCC_VDDPAD") (pintype "bidirectional"))
      (node (ref "U96") (pin "VDD") (pinfunction "VCC_VDD") (pintype "bidirectional"))
      (node (ref "U96") (pin "VDDPAD") (pinfunction "VCC_VDDPAD") (pintype "bidirectional"))
      (node (ref "U97") (pin "VDD") (pinfunction "VCC_VDD") (pintype "bidirectional"))
      (node (ref "U97") (pin "VDDPAD") (pinfunction "VCC_VDDPAD") (pintype "bidirectional"))
      (node (ref "U98") (pin "VDD") (pinfunction "VCC_VDD") (pintype "bidirectional"))
      (node (ref "U98") (pin "VDDPAD") (pinfunction "VCC_VDDPAD") (pintype "bidirectional"))
      (node (ref "U99") (pin "VDD") (pinfunction "VCC_VDD") (pintype "bidirectional"))
      (node (ref "U99") (pin "VDDPAD") (pinfunction "VCC_VDDPAD") (pintype "bidirectional"))
    )
    (net (code "505") (name "unconnected-(U95-CO-PadCKO)") (class "Default")
      (node (ref "U95") (pin "CKO") (pinfunction "CO_CKO") (pintype "bidirectional"))
    )
    (net (code "506") (name "unconnected-(U95-DO-PadSDO)") (class "Default")
      (node (ref "U95") (pin "SDO") (pinfunction "DO_SDO") (pintype "bidirectional"))
    )
    (net (code "507") (name "unconnected-(U96-CI-PadCKI)") (class "Default")
      (node (ref "U96") (pin "CKI") (pinfunction "CI_CKI") (pintype "bidirectional"))
    )
    (net (code "508") (name "unconnected-(U96-DI-PadSDI)") (class "Default")
      (node (ref "U96") (pin "SDI") (pinfunction "DI_SDI") (pintype "bidirectional"))
    )
    (net (code "509") (name "unconnected-(U126-CO-PadCKO)") (class "Default")
      (node (ref "U126") (pin "CKO") (pinfunction "CO_CKO") (pintype "bidirectional"))
    )
    (net (code "510") (name "unconnected-(U126-DO-PadSDO)") (class "Default")
      (node (ref "U126") (pin "SDO") (pinfunction "DO_SDO") (pintype "bidirectional"))
    )
    (net (code "511") (name "unconnected-(U252-CO-PadCKO)") (class "Default")
      (node (ref "U252") (pin "CKO") (pinfunction "CO_CKO") (pintype "bidirectional"))
    )
    (net (code "512") (name "unconnected-(U252-DO-PadSDO)") (class "Default")
      (node (ref "U252") (pin "SDO") (pinfunction "DO_SDO") (pintype "bidirectional"))
    )
  )
)
